# tc08-8-07.net
KiCad netlist of a schematic drawn in EAGLE
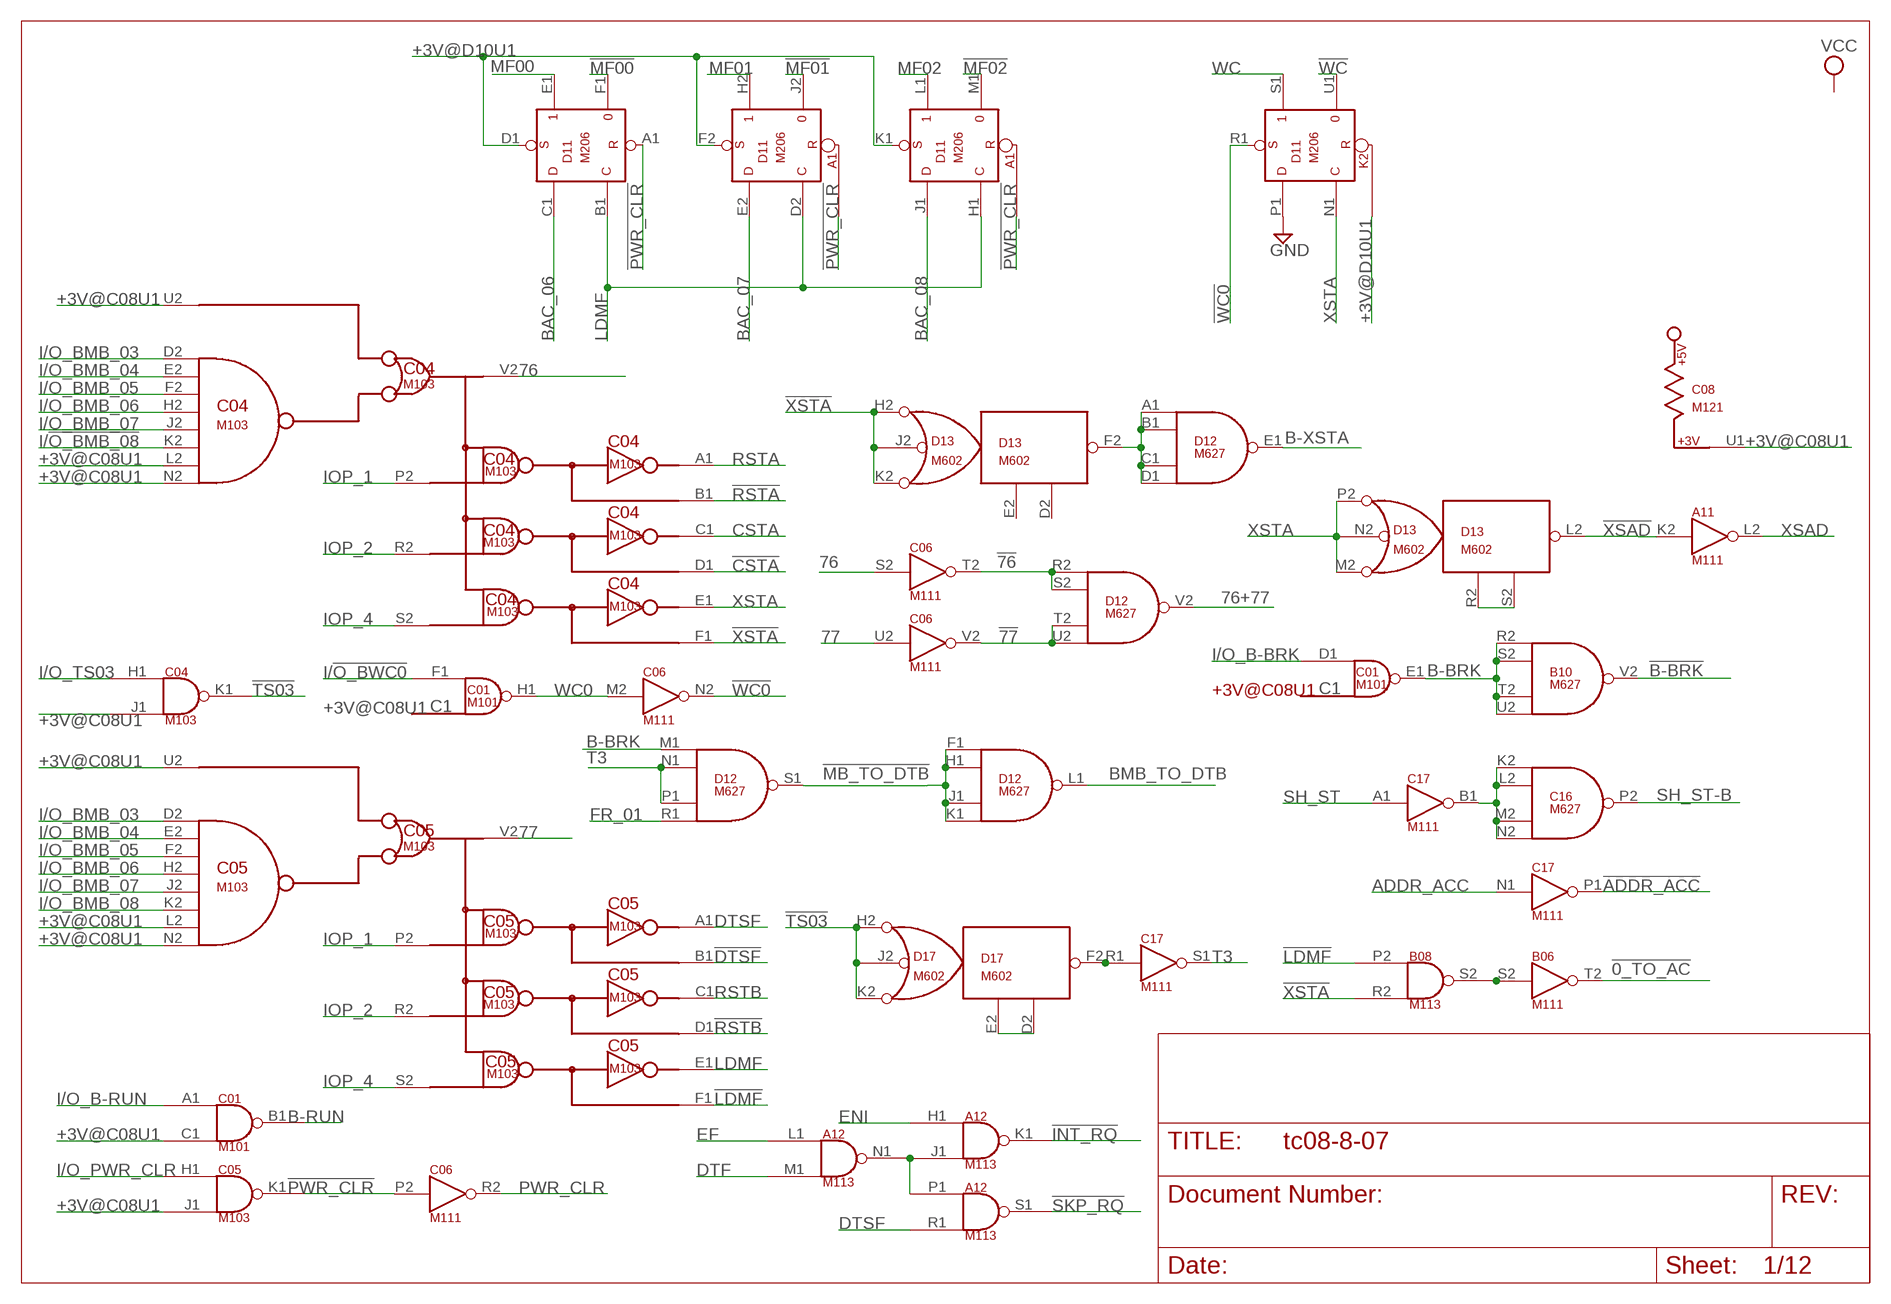
[diagram p0: schematic, sheet 1]
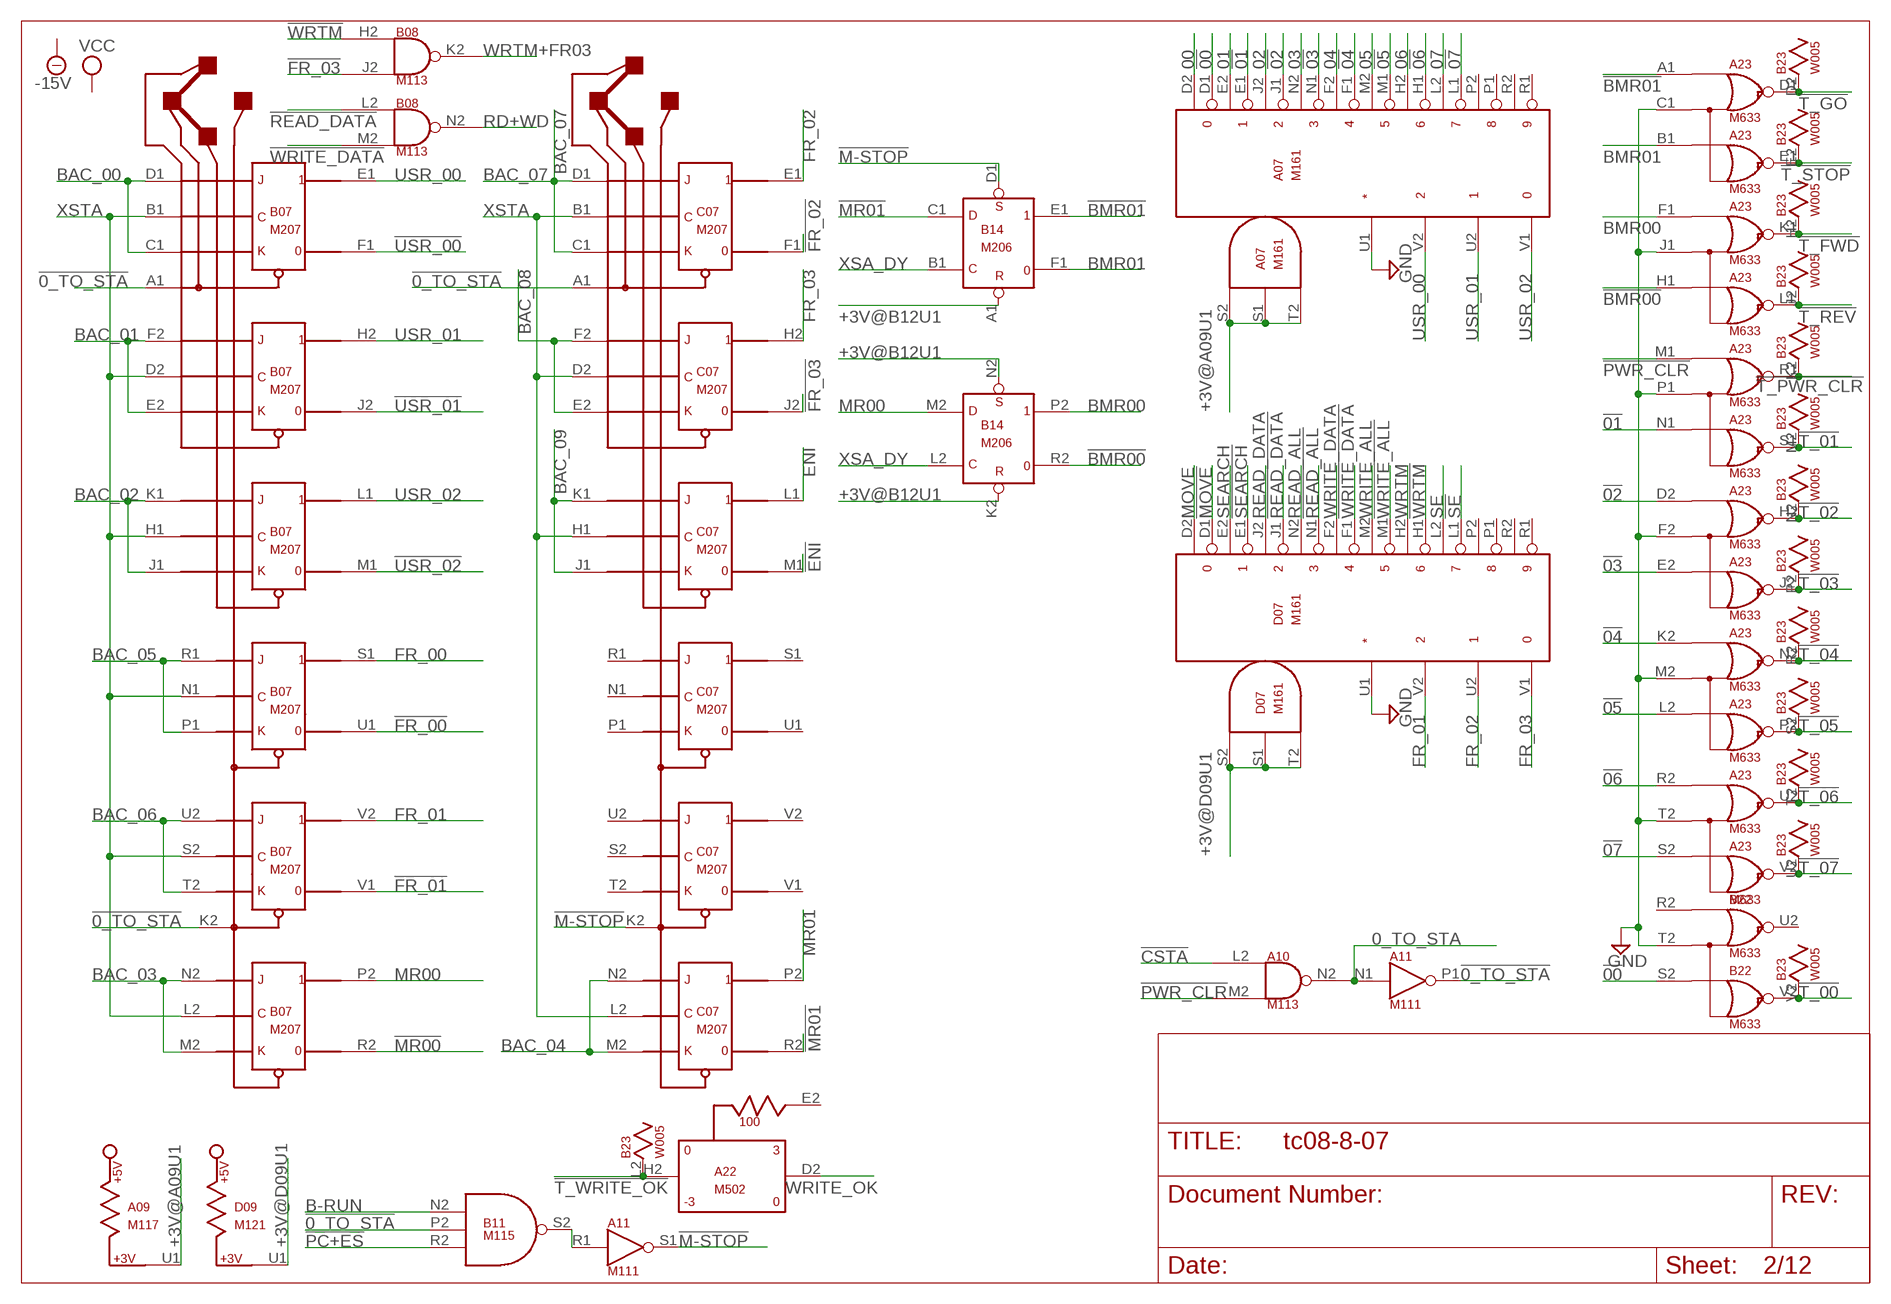
[diagram p1: schematic, sheet 2]
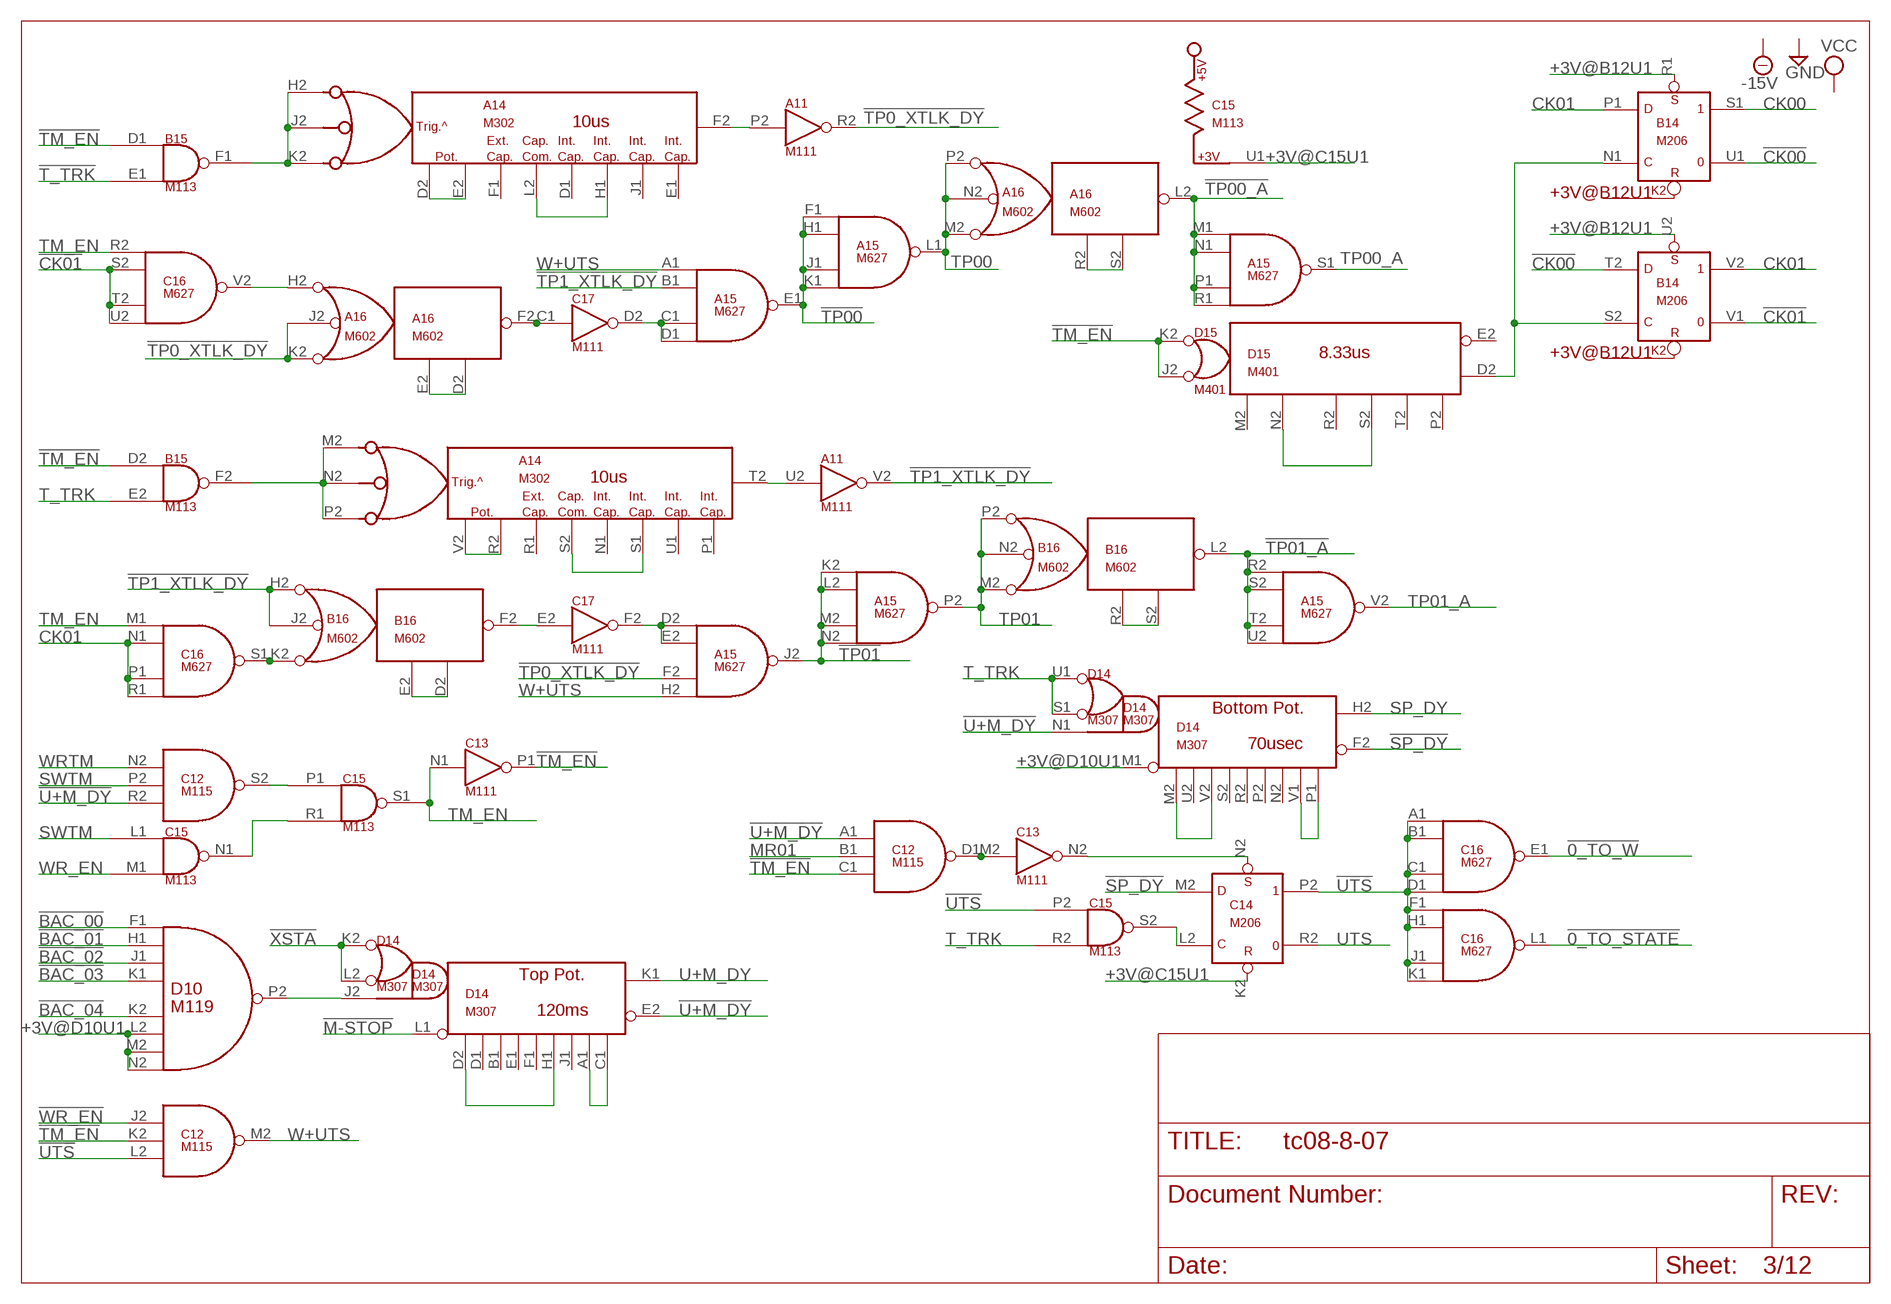
[diagram p2: schematic, sheet 3]
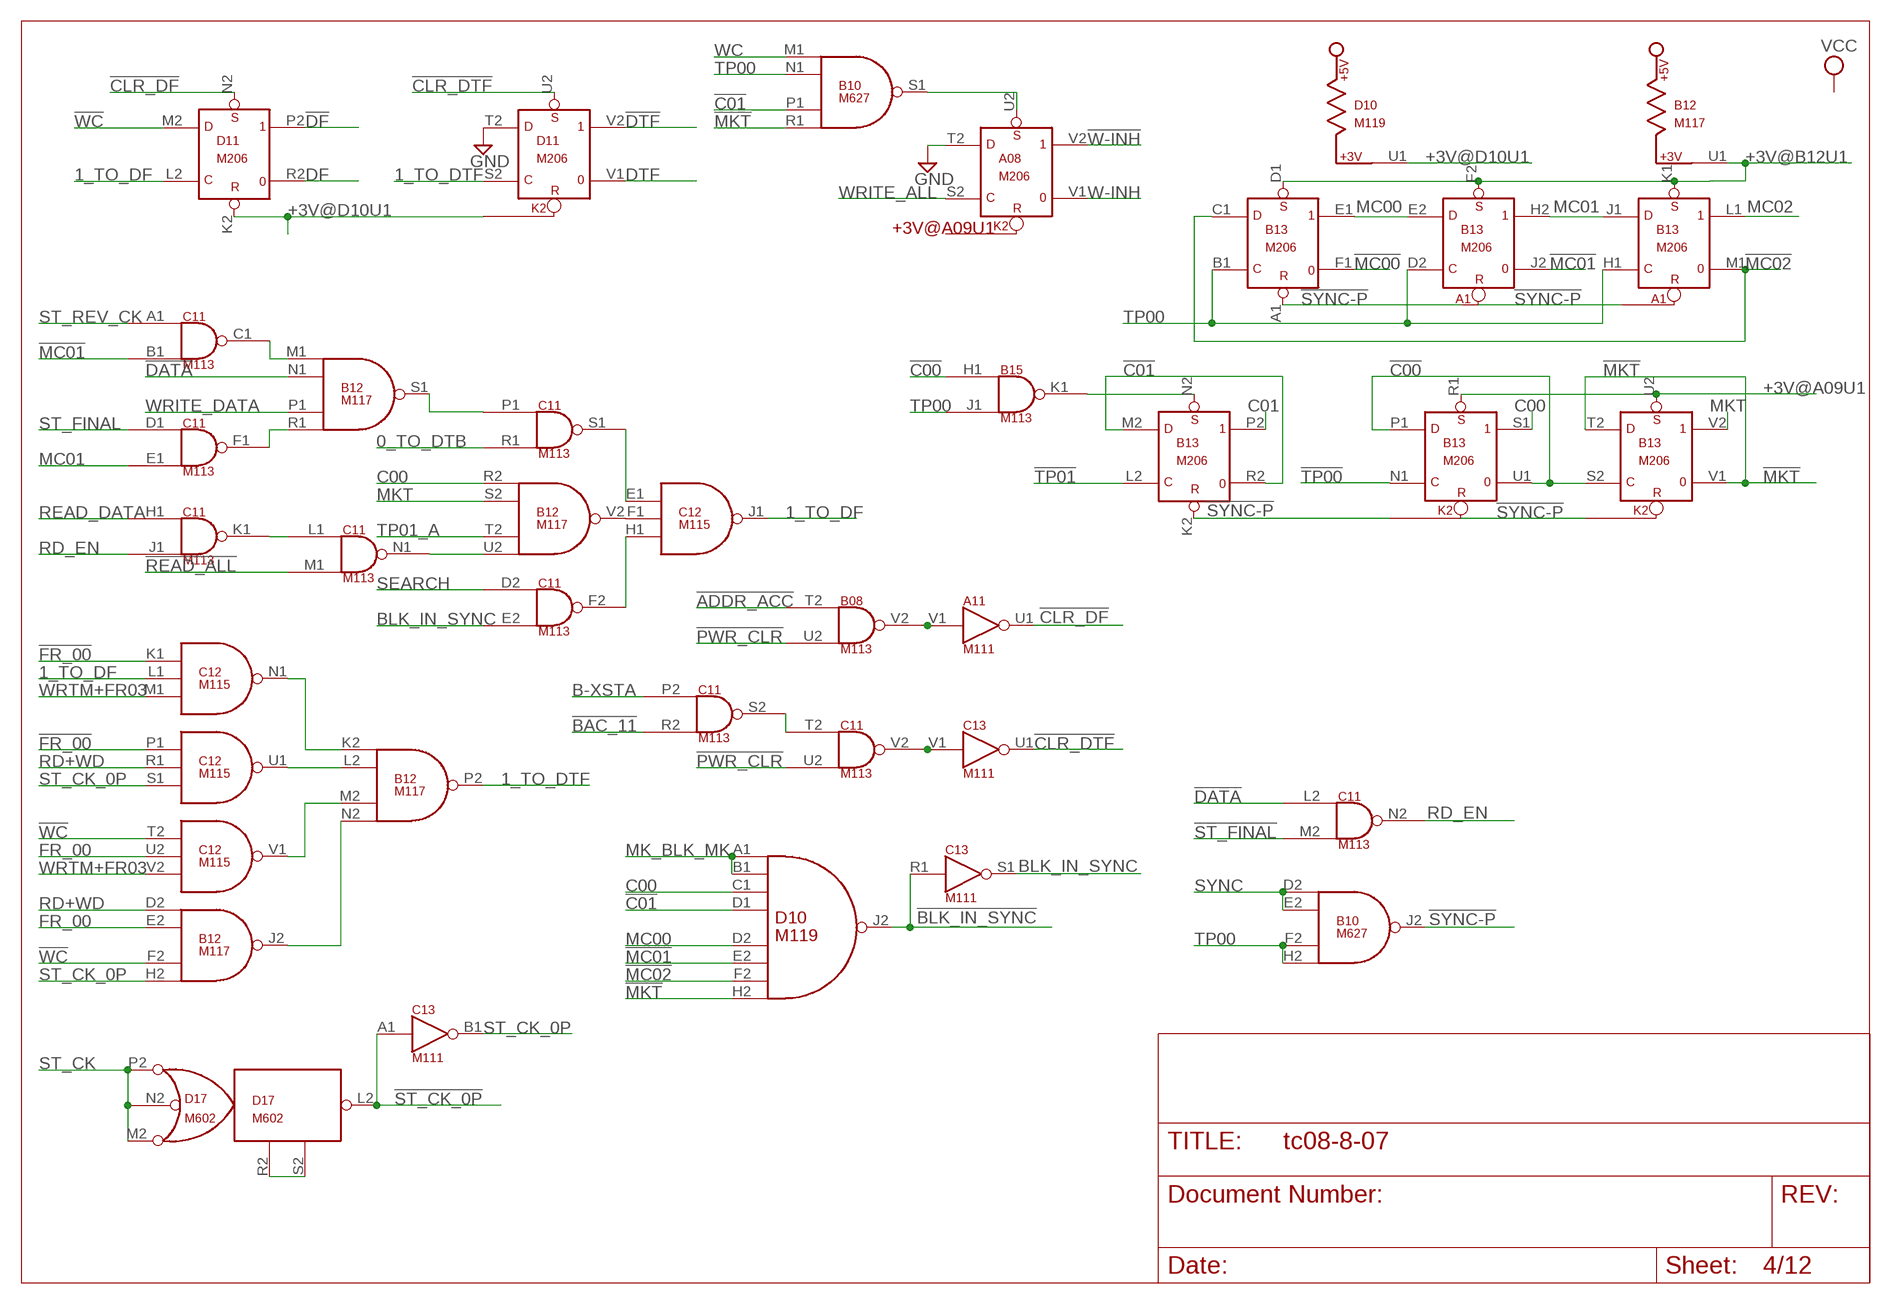
[diagram p3: schematic, sheet 4]
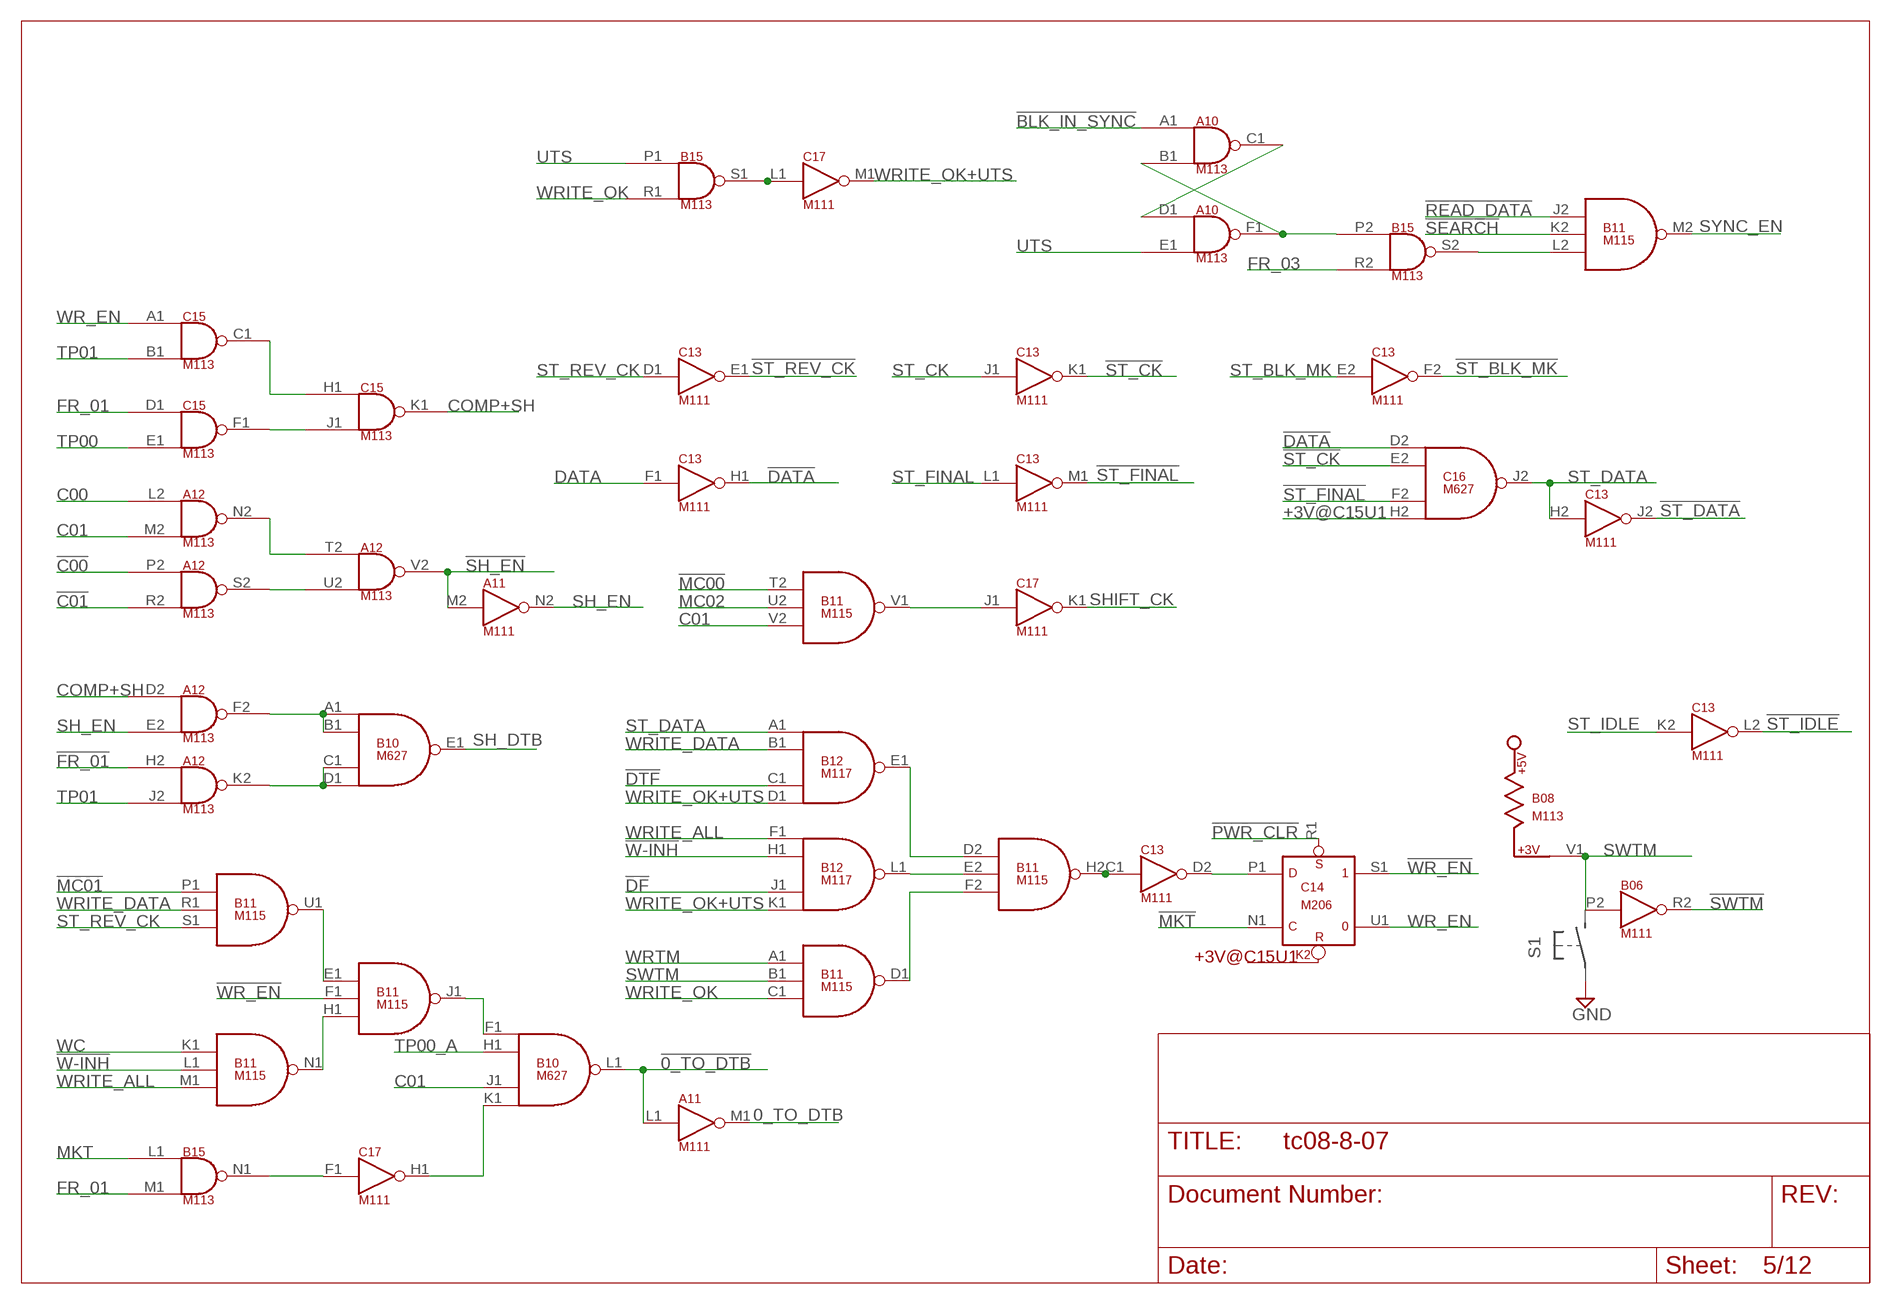
[diagram p4: schematic, sheet 5]
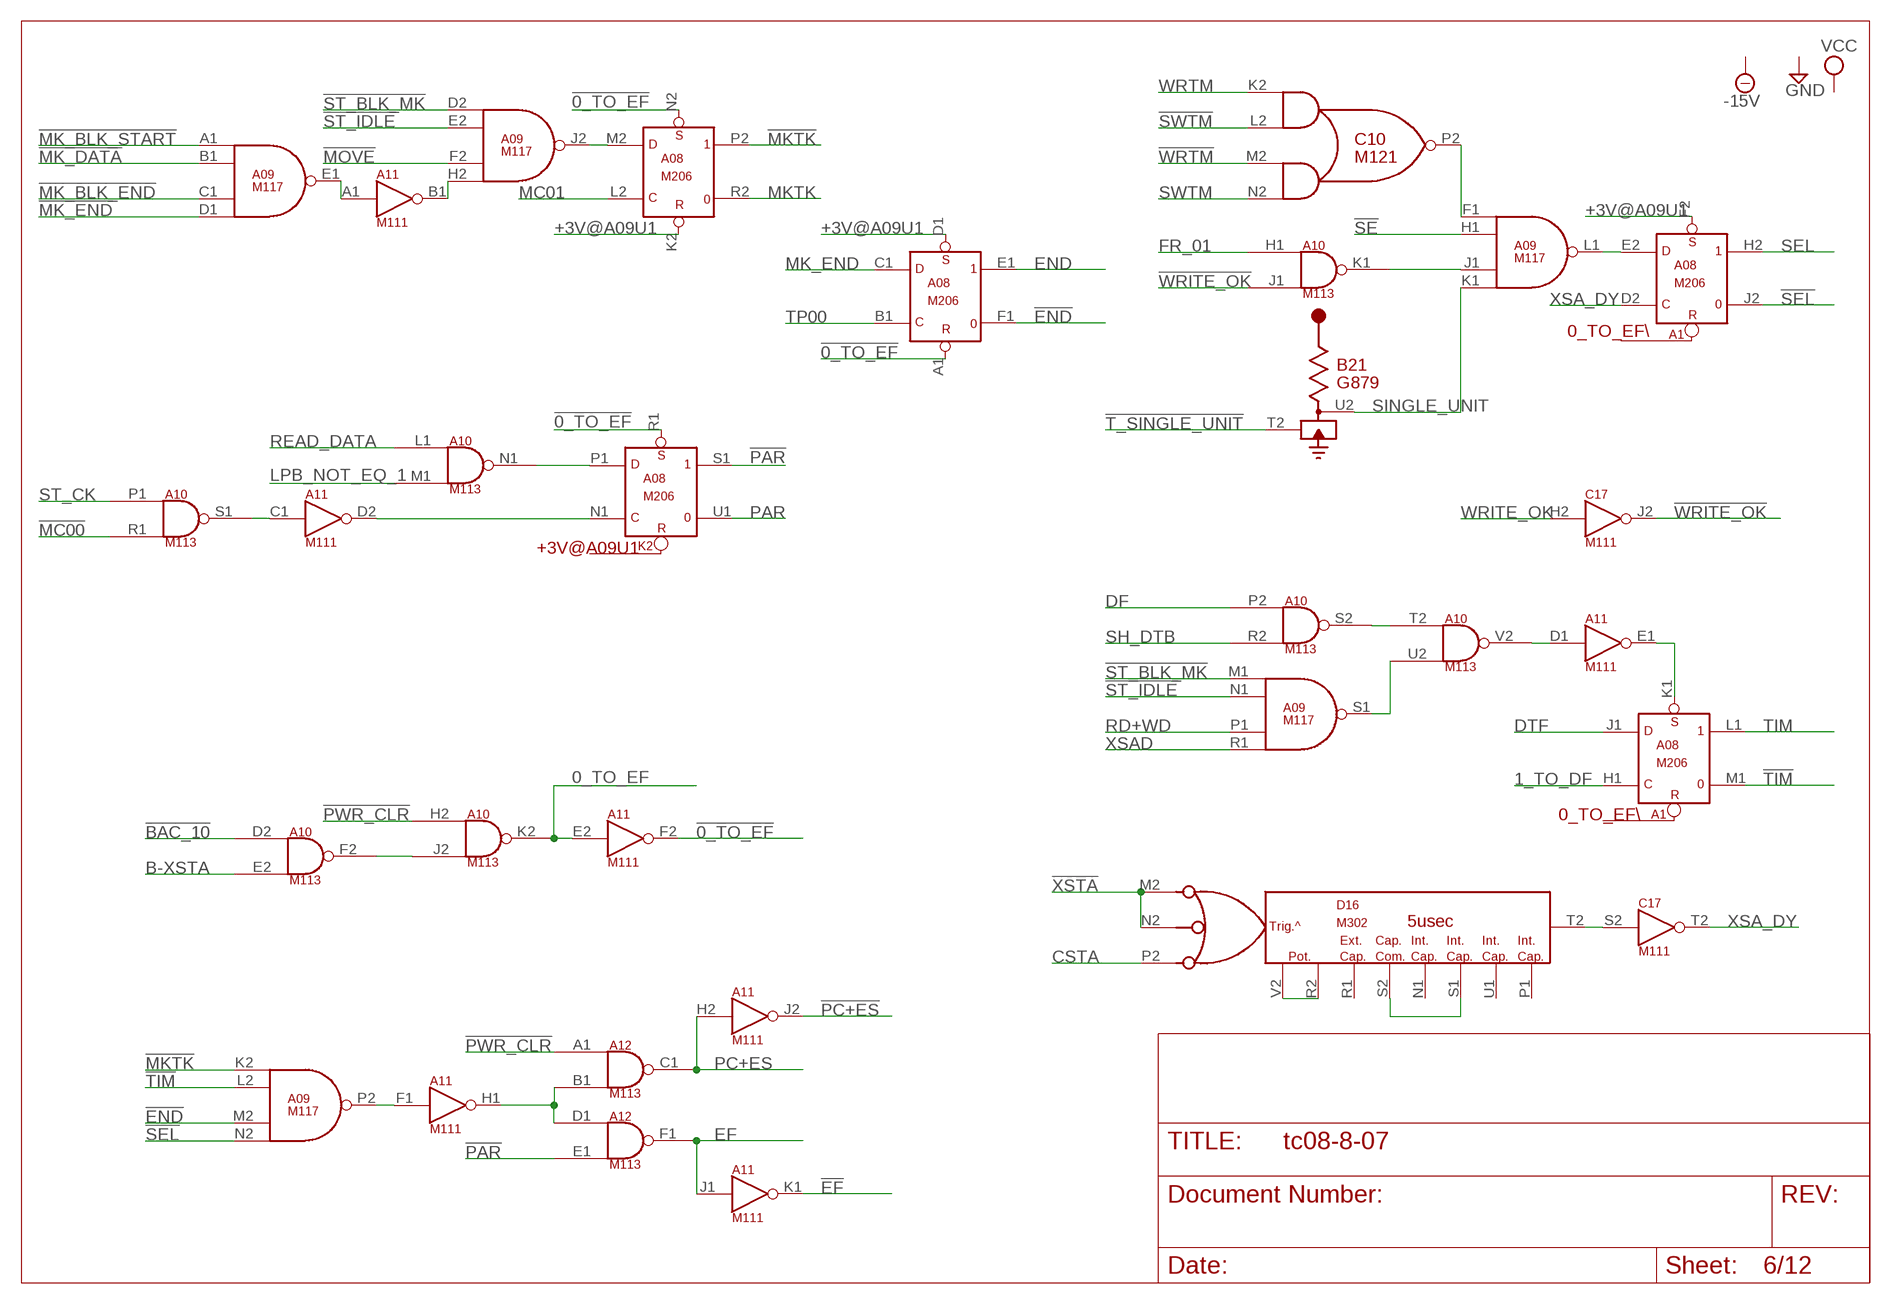
[diagram p5: schematic, sheet 6]
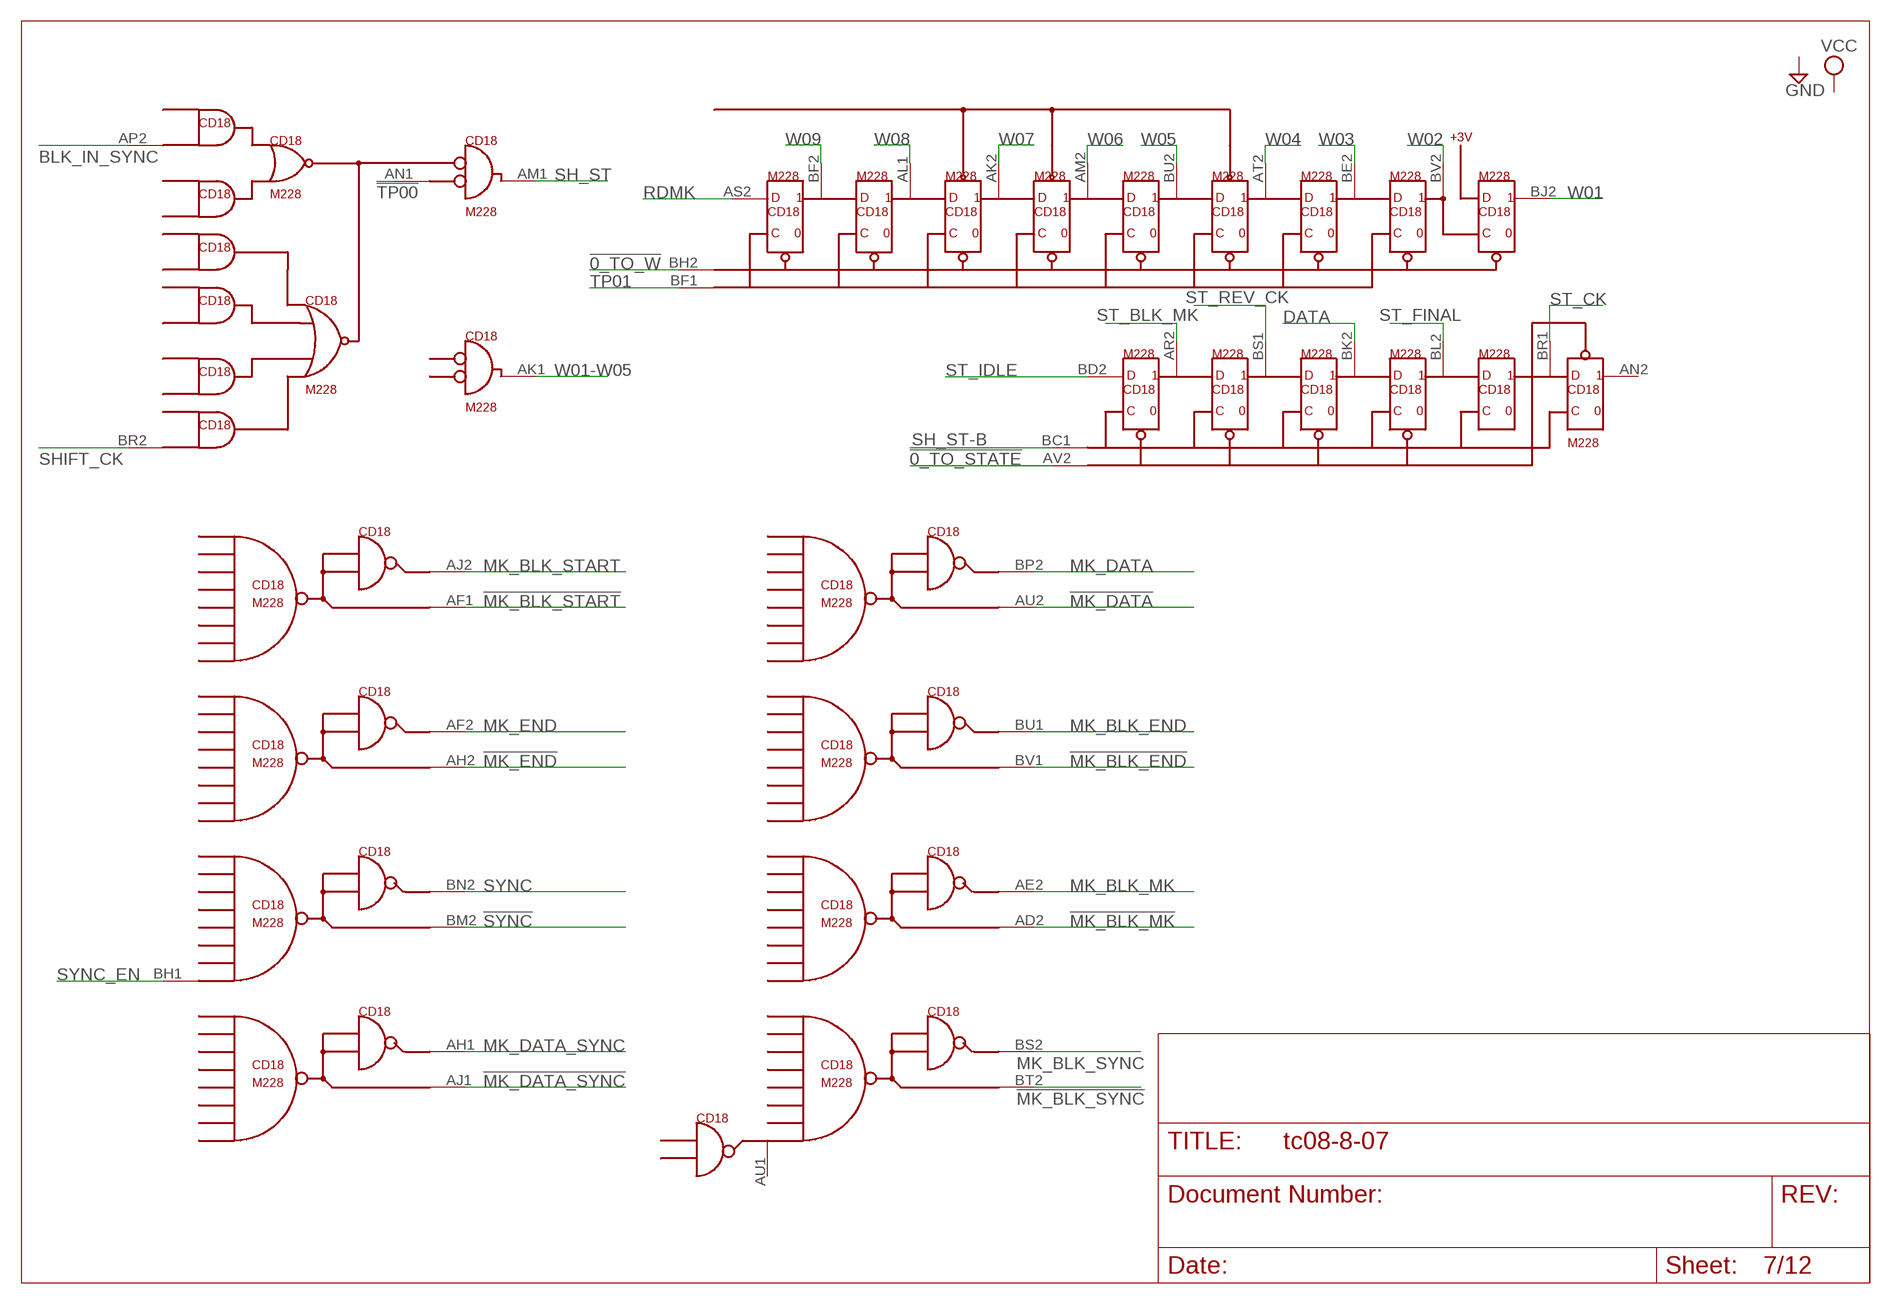
[diagram p6: schematic, sheet 7]
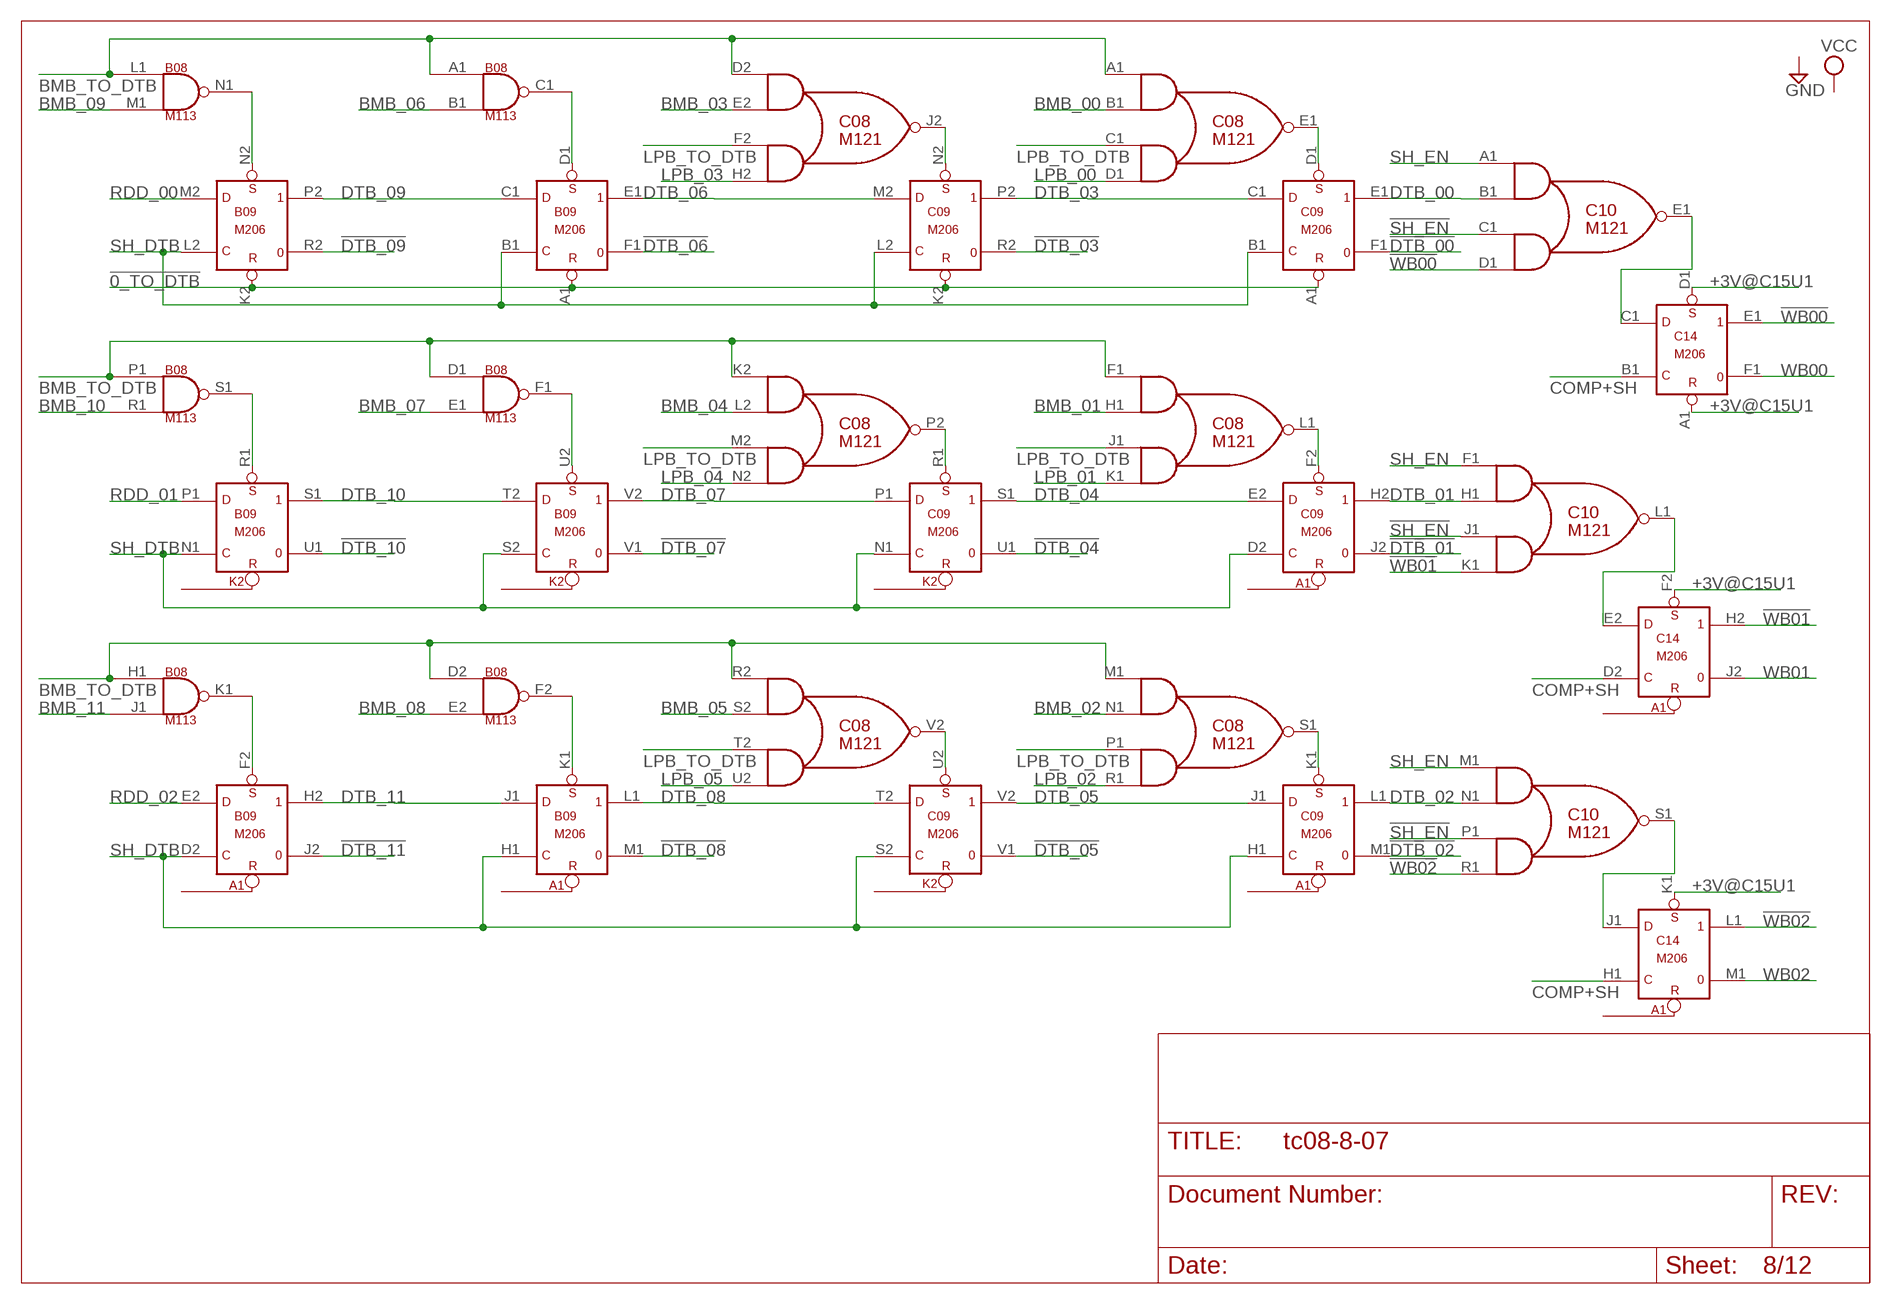
[diagram p7: schematic, sheet 8]
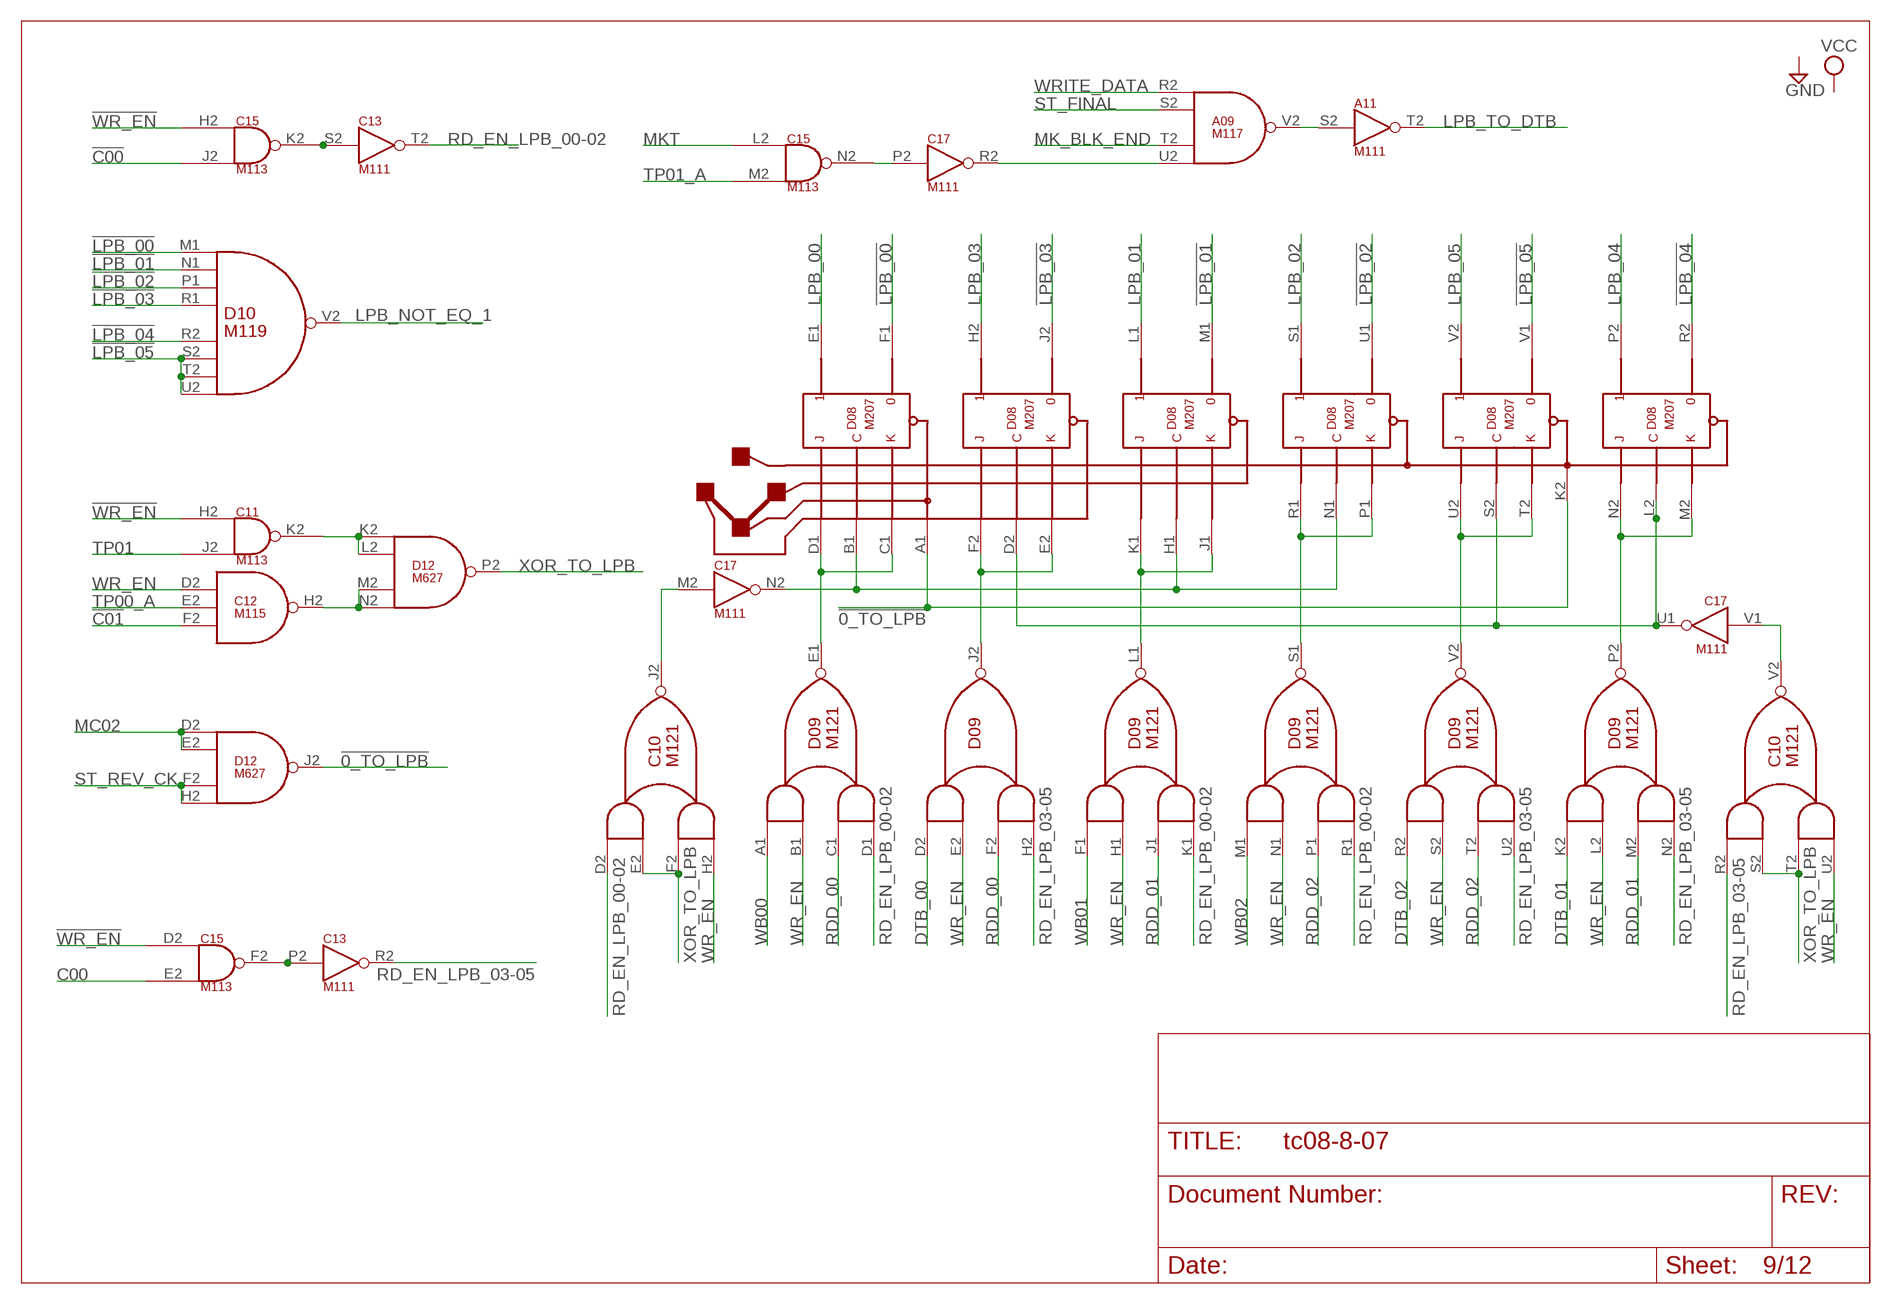
[diagram p8: schematic, sheet 9]
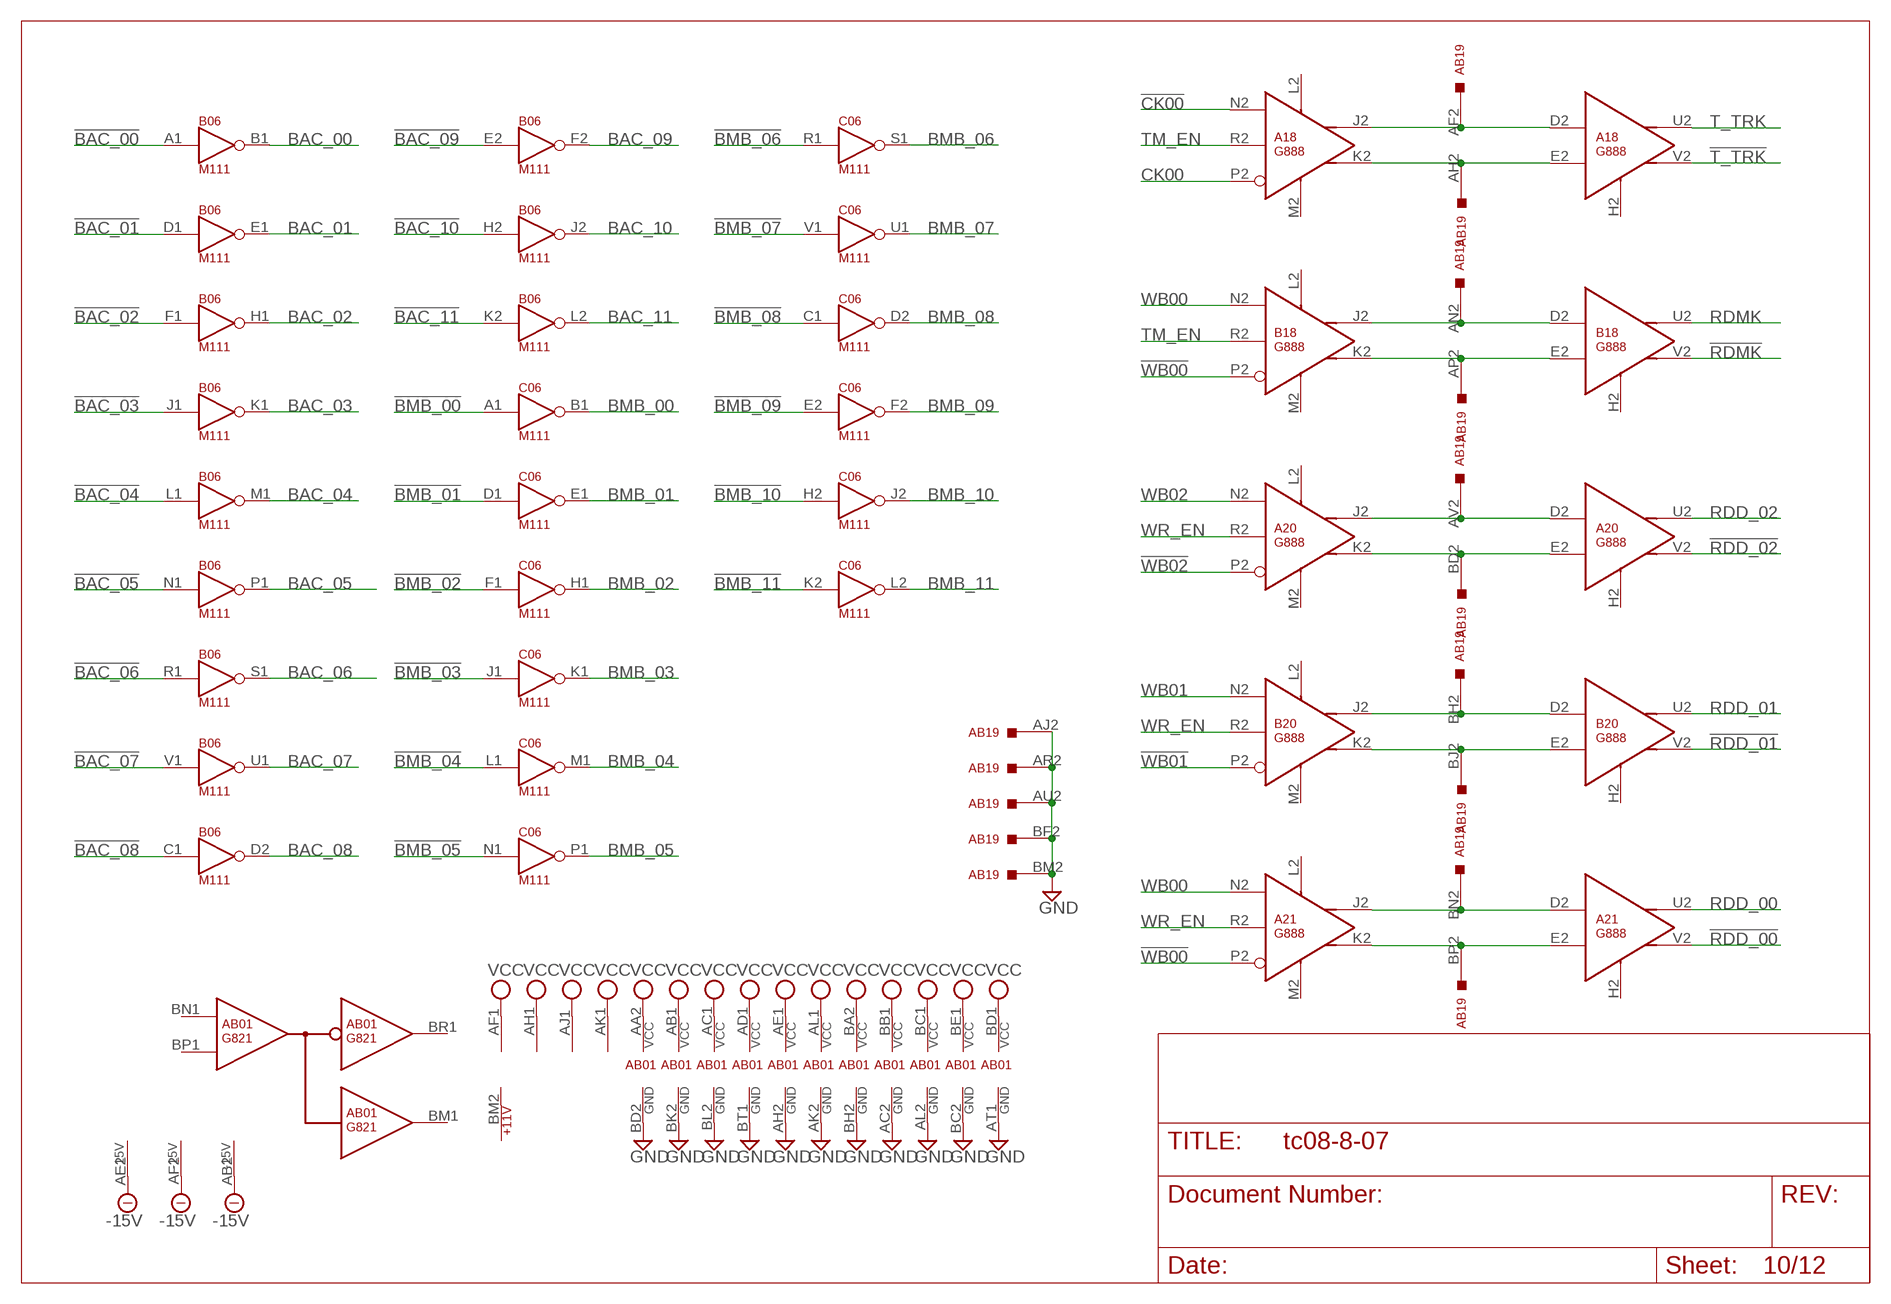
[diagram p9: schematic, sheet 10]
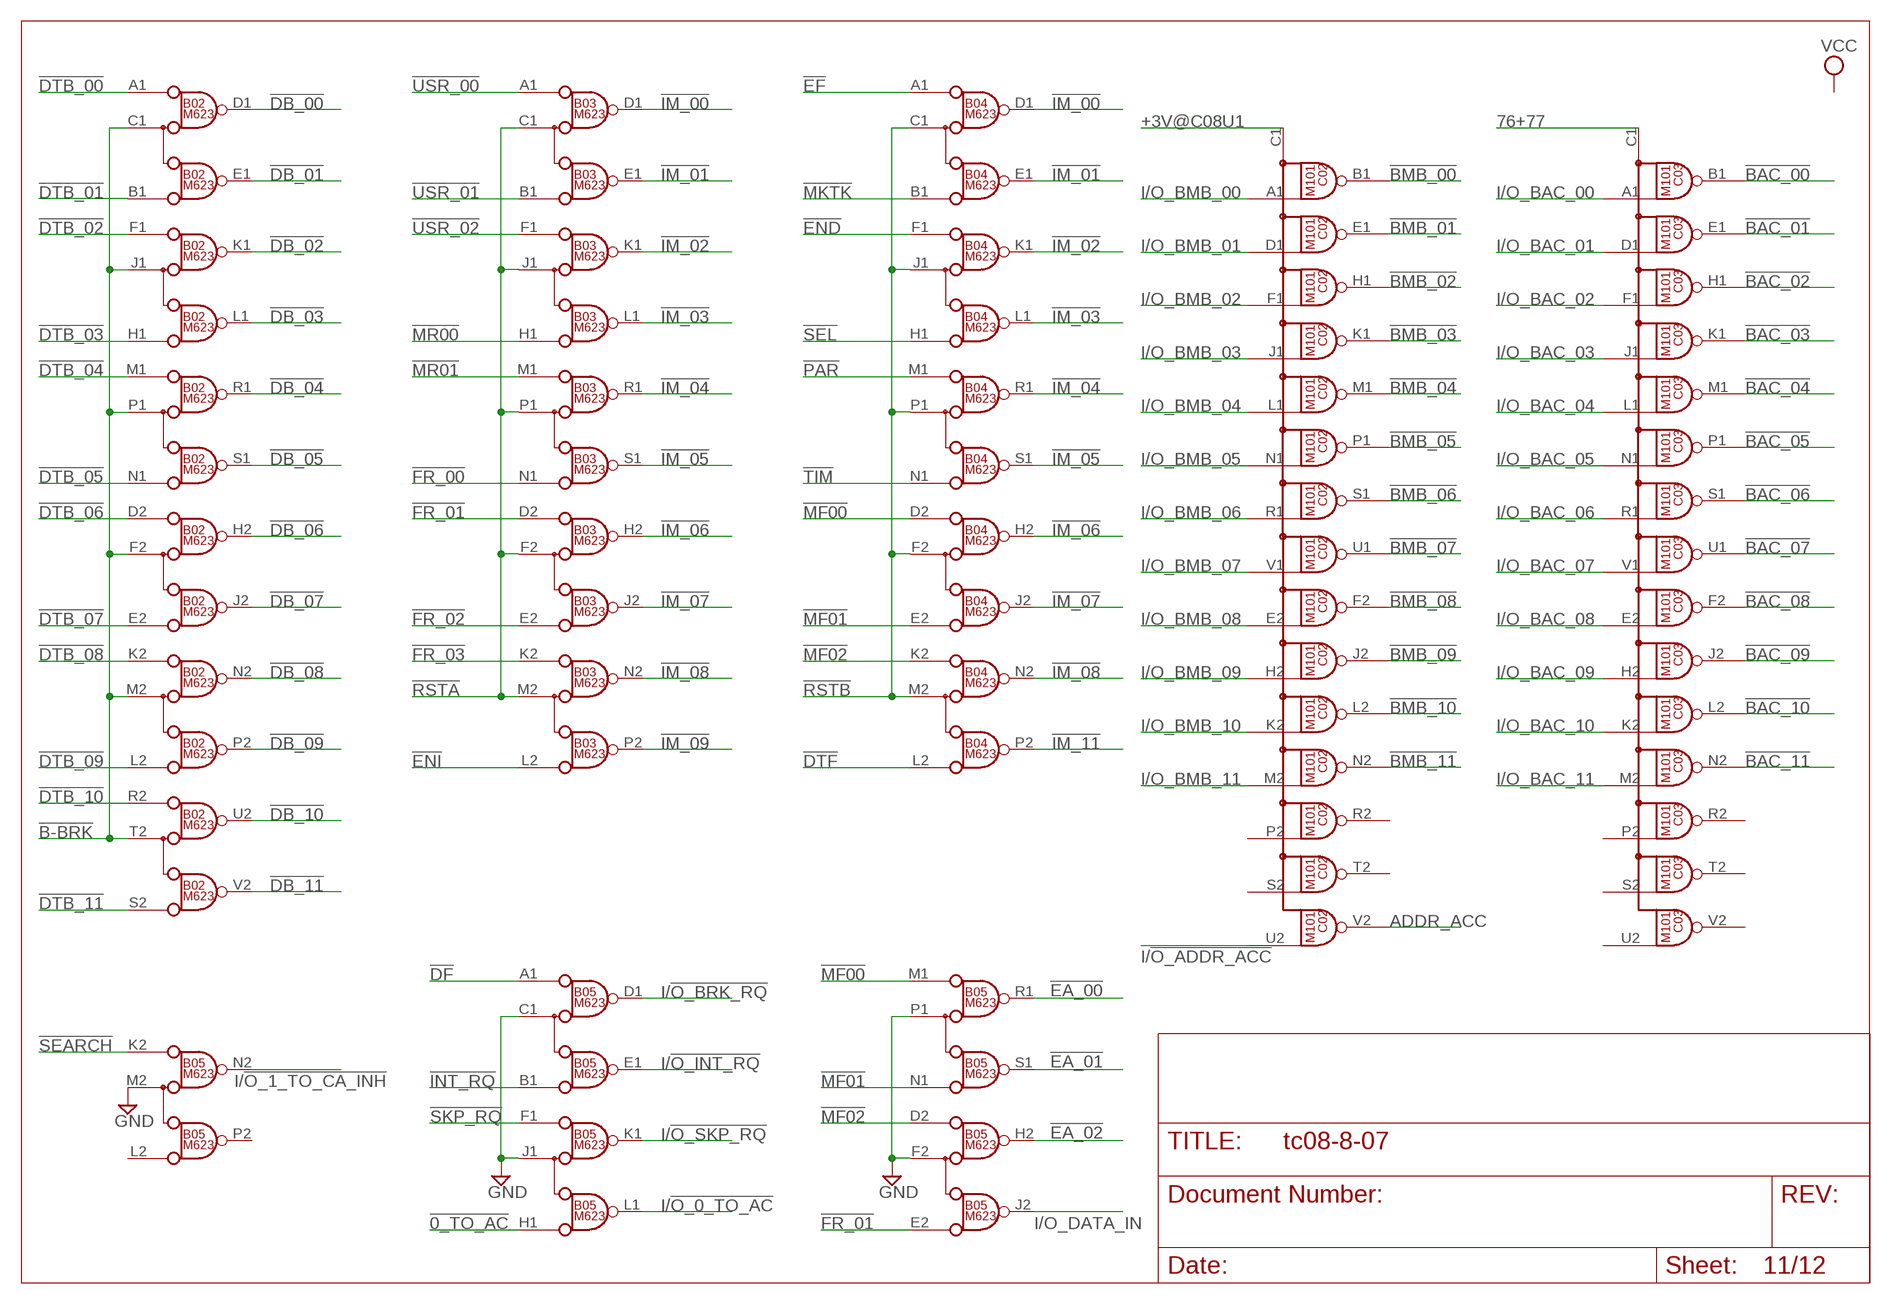
[diagram p10: schematic, sheet 11]
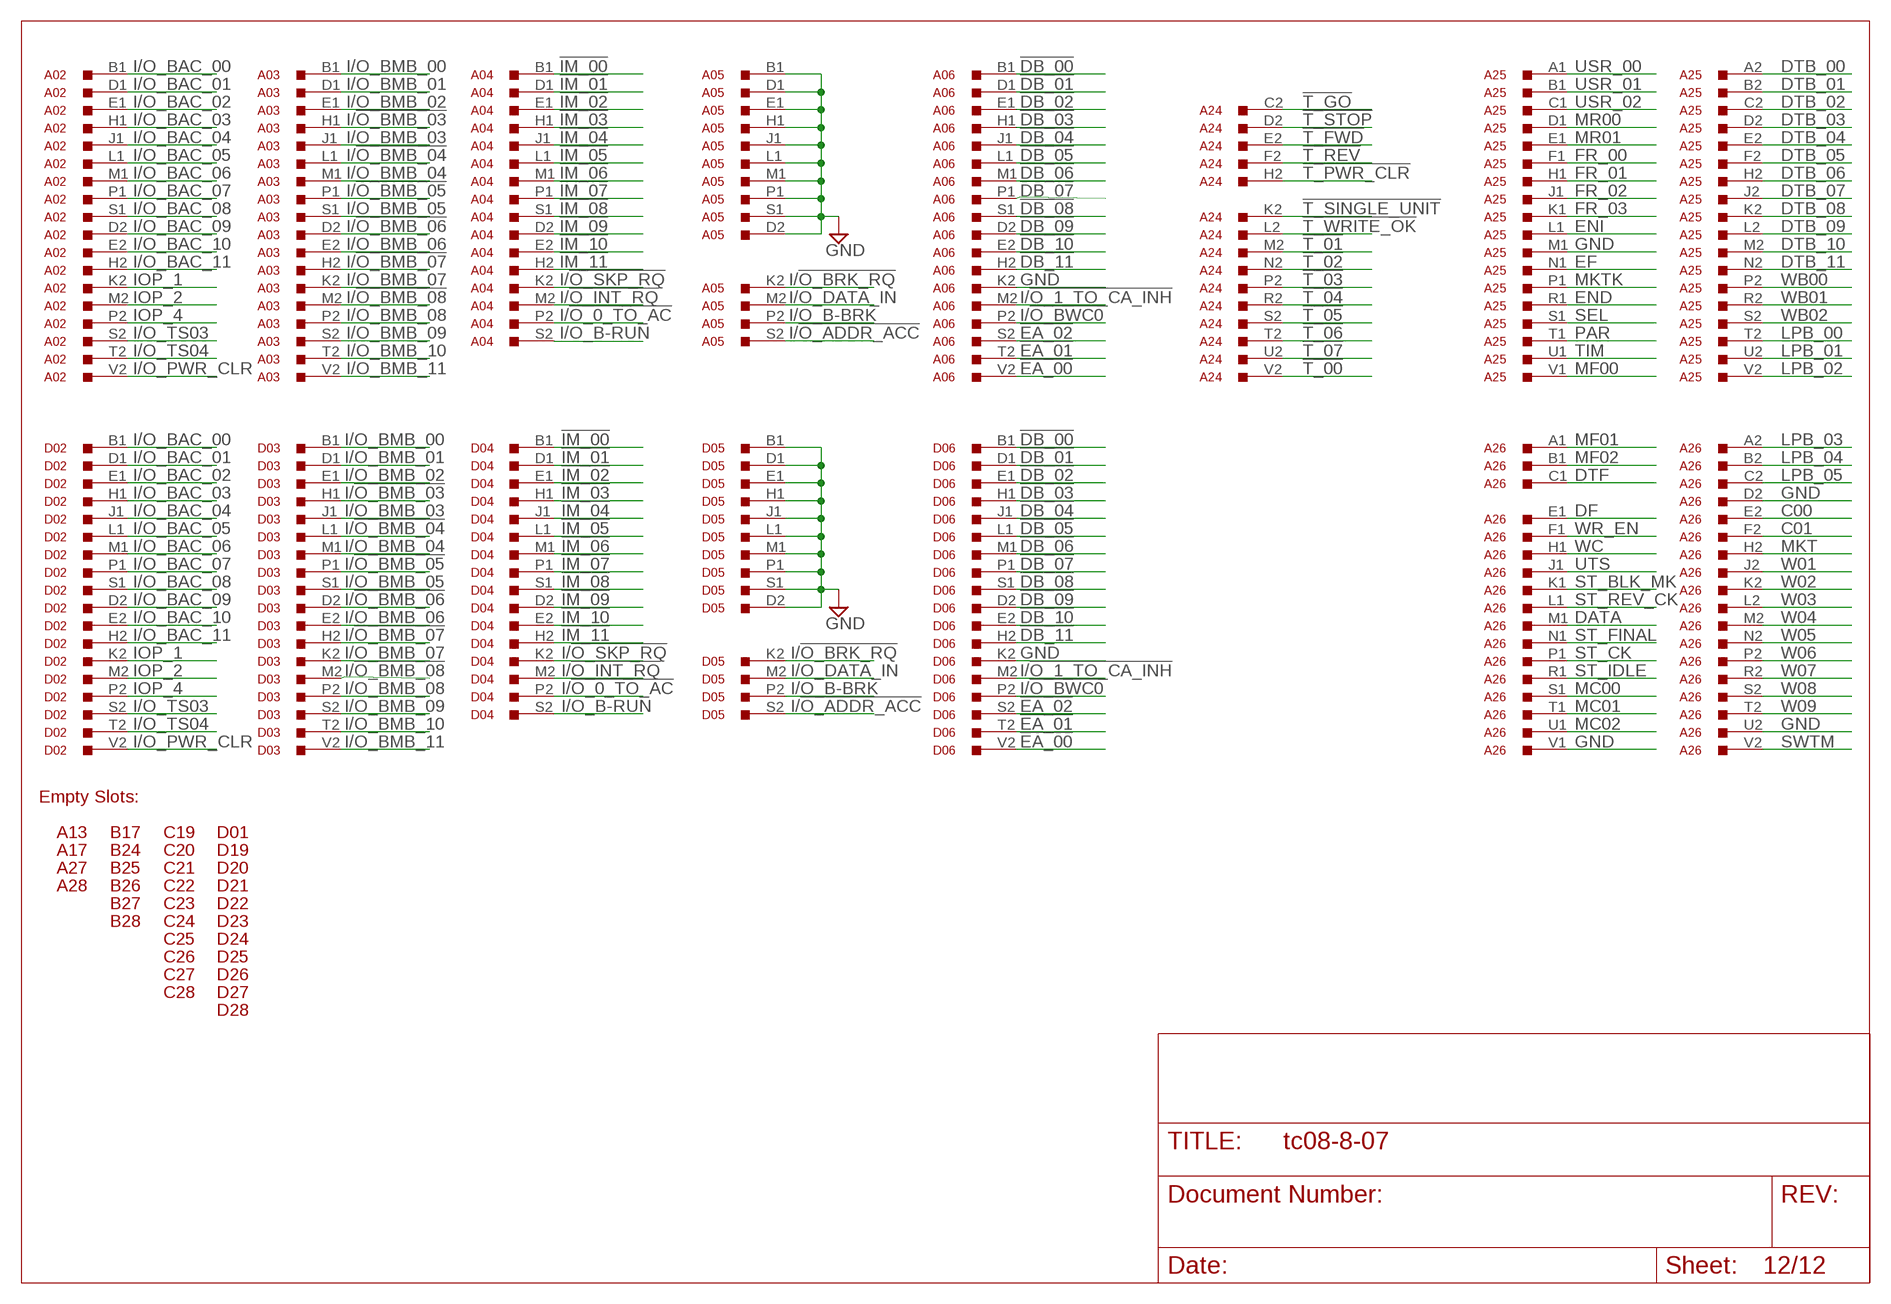
[diagram p11: schematic, sheet 12]

(export (version "E")
  (design (tool "Eeschema 10.0.6"))
  (components
    (comp (ref "A07")
      (value "M161")
      (footprint "eagle-import:H807")
      (libsource (lib "eagle-import") (part "M161"))
    )
    (comp (ref "A09")
      (value "M117")
      (footprint "eagle-import:H807")
      (libsource (lib "eagle-import") (part "M117"))
    )
    (comp (ref "A10")
      (value "M113")
      (footprint "eagle-import:H807")
      (libsource (lib "eagle-import") (part "M113"))
    )
    (comp (ref "A11")
      (value "M111")
      (footprint "eagle-import:H807")
      (libsource (lib "eagle-import") (part "M111"))
    )
    (comp (ref "A22")
      (value "M502")
      (footprint "eagle-import:H807")
      (libsource (lib "eagle-import") (part "M502"))
    )
    (comp (ref "A23")
      (value "M633")
      (footprint "eagle-import:H807")
      (libsource (lib "eagle-import") (part "M633"))
    )
    (comp (ref "B07")
      (value "M207")
      (footprint "eagle-import:H807")
      (libsource (lib "eagle-import") (part "M207"))
    )
    (comp (ref "B08")
      (value "M113")
      (footprint "eagle-import:H807")
      (libsource (lib "eagle-import") (part "M113"))
    )
    (comp (ref "B11")
      (value "M115")
      (footprint "eagle-import:H807")
      (libsource (lib "eagle-import") (part "M115"))
    )
    (comp (ref "B14")
      (value "M206")
      (footprint "eagle-import:H807")
      (libsource (lib "eagle-import") (part "M206X"))
    )
    (comp (ref "B22")
      (value "M633")
      (footprint "eagle-import:H807")
      (libsource (lib "eagle-import") (part "M633"))
    )
    (comp (ref "B23")
      (value "W005")
      (footprint "eagle-import:H807")
      (libsource (lib "eagle-import") (part "W005"))
    )
    (comp (ref "C07")
      (value "M207")
      (footprint "eagle-import:H807")
      (libsource (lib "eagle-import") (part "M207"))
    )
    (comp (ref "D07")
      (value "M161")
      (footprint "eagle-import:H807")
      (libsource (lib "eagle-import") (part "M161"))
    )
    (comp (ref "D09")
      (value "M121")
      (footprint "eagle-import:H807")
      (libsource (lib "eagle-import") (part "M121"))
    )
    (comp (ref "B09")
      (value "M206")
      (footprint "eagle-import:H807")
      (libsource (lib "eagle-import") (part "M206X"))
    )
    (comp (ref "C08")
      (value "M121")
      (footprint "eagle-import:H807")
      (libsource (lib "eagle-import") (part "M121"))
    )
    (comp (ref "C09")
      (value "M206")
      (footprint "eagle-import:H807")
      (libsource (lib "eagle-import") (part "M206X"))
    )
    (comp (ref "C10")
      (value "M121")
      (footprint "eagle-import:H807")
      (libsource (lib "eagle-import") (part "M121"))
    )
    (comp (ref "C14")
      (value "M206")
      (footprint "eagle-import:H807")
      (libsource (lib "eagle-import") (part "M206X"))
    )
    (comp (ref "A12")
      (value "M113")
      (footprint "eagle-import:H807")
      (libsource (lib "eagle-import") (part "M113"))
    )
    (comp (ref "B06")
      (value "M111")
      (footprint "eagle-import:H807")
      (libsource (lib "eagle-import") (part "M111"))
    )
    (comp (ref "B10")
      (value "M627")
      (footprint "eagle-import:H807")
      (libsource (lib "eagle-import") (part "M627"))
    )
    (comp (ref "C01")
      (value "M101")
      (footprint "eagle-import:H807")
      (libsource (lib "eagle-import") (part "M101"))
    )
    (comp (ref "C04")
      (value "M103")
      (footprint "eagle-import:H807")
      (libsource (lib "eagle-import") (part "M103"))
    )
    (comp (ref "C05")
      (value "M103")
      (footprint "eagle-import:H807")
      (libsource (lib "eagle-import") (part "M103"))
    )
    (comp (ref "C06")
      (value "M111")
      (footprint "eagle-import:H807")
      (libsource (lib "eagle-import") (part "M111"))
    )
    (comp (ref "C16")
      (value "M627")
      (footprint "eagle-import:H807")
      (libsource (lib "eagle-import") (part "M627"))
    )
    (comp (ref "C17")
      (value "M111")
      (footprint "eagle-import:H807")
      (libsource (lib "eagle-import") (part "M111"))
    )
    (comp (ref "D11")
      (value "M206")
      (footprint "eagle-import:H807")
      (libsource (lib "eagle-import") (part "M206X"))
    )
    (comp (ref "D12")
      (value "M627")
      (footprint "eagle-import:H807")
      (libsource (lib "eagle-import") (part "M627"))
    )
    (comp (ref "D13")
      (value "M602")
      (footprint "eagle-import:H807")
      (libsource (lib "eagle-import") (part "M602"))
    )
    (comp (ref "D17")
      (value "M602")
      (footprint "eagle-import:H807")
      (libsource (lib "eagle-import") (part "M602"))
    )
    (comp (ref "A18")
      (value "G888")
      (footprint "eagle-import:H807")
      (libsource (lib "eagle-import") (part "G888"))
    )
    (comp (ref "A20")
      (value "G888")
      (footprint "eagle-import:H807")
      (libsource (lib "eagle-import") (part "G888"))
    )
    (comp (ref "A21")
      (value "G888")
      (footprint "eagle-import:H807")
      (libsource (lib "eagle-import") (part "G888"))
    )
    (comp (ref "AB01")
      (value "G821")
      (footprint "eagle-import:H807-2")
      (libsource (lib "eagle-import") (part "G821"))
    )
    (comp (ref "AB19")
      (value "W032")
      (footprint "eagle-import:H807-2")
      (libsource (lib "eagle-import") (part "W032"))
    )
    (comp (ref "B18")
      (value "G888")
      (footprint "eagle-import:H807")
      (libsource (lib "eagle-import") (part "G888"))
    )
    (comp (ref "B20")
      (value "G888")
      (footprint "eagle-import:H807")
      (libsource (lib "eagle-import") (part "G888"))
    )
    (comp (ref "A14")
      (value "M302")
      (footprint "eagle-import:H807")
      (libsource (lib "eagle-import") (part "M302"))
    )
    (comp (ref "A15")
      (value "M627")
      (footprint "eagle-import:H807")
      (libsource (lib "eagle-import") (part "M627"))
    )
    (comp (ref "A16")
      (value "M602")
      (footprint "eagle-import:H807")
      (libsource (lib "eagle-import") (part "M602"))
    )
    (comp (ref "B15")
      (value "M113")
      (footprint "eagle-import:H807")
      (libsource (lib "eagle-import") (part "M113"))
    )
    (comp (ref "B16")
      (value "M602")
      (footprint "eagle-import:H807")
      (libsource (lib "eagle-import") (part "M602"))
    )
    (comp (ref "C12")
      (value "M115")
      (footprint "eagle-import:H807")
      (libsource (lib "eagle-import") (part "M115"))
    )
    (comp (ref "C13")
      (value "M111")
      (footprint "eagle-import:H807")
      (libsource (lib "eagle-import") (part "M111"))
    )
    (comp (ref "C15")
      (value "M113")
      (footprint "eagle-import:H807")
      (libsource (lib "eagle-import") (part "M113"))
    )
    (comp (ref "D10")
      (value "M119")
      (footprint "eagle-import:H807")
      (libsource (lib "eagle-import") (part "M119"))
    )
    (comp (ref "D14")
      (value "M307")
      (footprint "eagle-import:H807")
      (libsource (lib "eagle-import") (part "M307"))
    )
    (comp (ref "D15")
      (value "M401")
      (footprint "eagle-import:H807")
      (libsource (lib "eagle-import") (part "M401"))
    )
    (comp (ref "B12")
      (value "M117")
      (footprint "eagle-import:H807")
      (libsource (lib "eagle-import") (part "M117"))
    )
    (comp (ref "CD18")
      (value "M228")
      (footprint "eagle-import:H807-2")
      (libsource (lib "eagle-import") (part "M228"))
    )
    (comp (ref "A08")
      (value "M206")
      (footprint "eagle-import:H807")
      (libsource (lib "eagle-import") (part "M206X"))
    )
    (comp (ref "B13")
      (value "M206")
      (footprint "eagle-import:H807")
      (libsource (lib "eagle-import") (part "M206X"))
    )
    (comp (ref "C11")
      (value "M113")
      (footprint "eagle-import:H807")
      (libsource (lib "eagle-import") (part "M113"))
    )
    (comp (ref "B02")
      (value "M623")
      (footprint "eagle-import:H807")
      (libsource (lib "eagle-import") (part "M623"))
    )
    (comp (ref "B03")
      (value "M623")
      (footprint "eagle-import:H807")
      (libsource (lib "eagle-import") (part "M623"))
    )
    (comp (ref "B04")
      (value "M623")
      (footprint "eagle-import:H807")
      (libsource (lib "eagle-import") (part "M623"))
    )
    (comp (ref "B05")
      (value "M623")
      (footprint "eagle-import:H807")
      (libsource (lib "eagle-import") (part "M623"))
    )
    (comp (ref "C02")
      (value "M101")
      (footprint "eagle-import:H807")
      (libsource (lib "eagle-import") (part "M101-ARRAY"))
    )
    (comp (ref "C03")
      (value "M101")
      (footprint "eagle-import:H807")
      (libsource (lib "eagle-import") (part "M101-ARRAY"))
    )
    (comp (ref "A02")
      (value "M903")
      (footprint "eagle-import:H807")
      (libsource (lib "eagle-import") (part "M903"))
    )
    (comp (ref "A03")
      (value "M903")
      (footprint "eagle-import:H807")
      (libsource (lib "eagle-import") (part "M903"))
    )
    (comp (ref "A04")
      (value "M903")
      (footprint "eagle-import:H807")
      (libsource (lib "eagle-import") (part "M903"))
    )
    (comp (ref "A05")
      (value "M903")
      (footprint "eagle-import:H807")
      (libsource (lib "eagle-import") (part "M903"))
    )
    (comp (ref "A06")
      (value "M903")
      (footprint "eagle-import:H807")
      (libsource (lib "eagle-import") (part "M903"))
    )
    (comp (ref "A13")
      (value "H807")
      (footprint "eagle-import:H807")
      (libsource (lib "eagle-import") (part "H807"))
    )
    (comp (ref "A17")
      (value "H807")
      (footprint "eagle-import:H807")
      (libsource (lib "eagle-import") (part "H807"))
    )
    (comp (ref "A24")
      (value "W023")
      (footprint "eagle-import:H807")
      (libsource (lib "eagle-import") (part "W023"))
    )
    (comp (ref "A25")
      (value "M916")
      (footprint "eagle-import:H807")
      (libsource (lib "eagle-import") (part "M916"))
    )
    (comp (ref "A26")
      (value "M916")
      (footprint "eagle-import:H807")
      (libsource (lib "eagle-import") (part "M916"))
    )
    (comp (ref "A27")
      (value "H807")
      (footprint "eagle-import:H807")
      (libsource (lib "eagle-import") (part "H807"))
    )
    (comp (ref "A28")
      (value "H807")
      (footprint "eagle-import:H807")
      (libsource (lib "eagle-import") (part "H807"))
    )
    (comp (ref "B17")
      (value "H807")
      (footprint "eagle-import:H807")
      (libsource (lib "eagle-import") (part "H807"))
    )
    (comp (ref "B24")
      (value "H807")
      (footprint "eagle-import:H807")
      (libsource (lib "eagle-import") (part "H807"))
    )
    (comp (ref "B25")
      (value "H807")
      (footprint "eagle-import:H807")
      (libsource (lib "eagle-import") (part "H807"))
    )
    (comp (ref "B26")
      (value "H807")
      (footprint "eagle-import:H807")
      (libsource (lib "eagle-import") (part "H807"))
    )
    (comp (ref "B27")
      (value "H807")
      (footprint "eagle-import:H807")
      (libsource (lib "eagle-import") (part "H807"))
    )
    (comp (ref "B28")
      (value "H807")
      (footprint "eagle-import:H807")
      (libsource (lib "eagle-import") (part "H807"))
    )
    (comp (ref "C19")
      (value "H807")
      (footprint "eagle-import:H807")
      (libsource (lib "eagle-import") (part "H807"))
    )
    (comp (ref "C20")
      (value "H807")
      (footprint "eagle-import:H807")
      (libsource (lib "eagle-import") (part "H807"))
    )
    (comp (ref "C21")
      (value "H807")
      (footprint "eagle-import:H807")
      (libsource (lib "eagle-import") (part "H807"))
    )
    (comp (ref "C22")
      (value "H807")
      (footprint "eagle-import:H807")
      (libsource (lib "eagle-import") (part "H807"))
    )
    (comp (ref "C23")
      (value "H807")
      (footprint "eagle-import:H807")
      (libsource (lib "eagle-import") (part "H807"))
    )
    (comp (ref "C24")
      (value "H807")
      (footprint "eagle-import:H807")
      (libsource (lib "eagle-import") (part "H807"))
    )
    (comp (ref "C25")
      (value "H807")
      (footprint "eagle-import:H807")
      (libsource (lib "eagle-import") (part "H807"))
    )
    (comp (ref "C26")
      (value "H807")
      (footprint "eagle-import:H807")
      (libsource (lib "eagle-import") (part "H807"))
    )
    (comp (ref "C27")
      (value "H807")
      (footprint "eagle-import:H807")
      (libsource (lib "eagle-import") (part "H807"))
    )
    (comp (ref "C28")
      (value "H807")
      (footprint "eagle-import:H807")
      (libsource (lib "eagle-import") (part "H807"))
    )
    (comp (ref "D01")
      (value "H807")
      (footprint "eagle-import:H807")
      (libsource (lib "eagle-import") (part "H807"))
    )
    (comp (ref "D02")
      (value "M903")
      (footprint "eagle-import:H807")
      (libsource (lib "eagle-import") (part "M903"))
    )
    (comp (ref "D03")
      (value "M903")
      (footprint "eagle-import:H807")
      (libsource (lib "eagle-import") (part "M903"))
    )
    (comp (ref "D04")
      (value "M903")
      (footprint "eagle-import:H807")
      (libsource (lib "eagle-import") (part "M903"))
    )
    (comp (ref "D05")
      (value "M903")
      (footprint "eagle-import:H807")
      (libsource (lib "eagle-import") (part "M903"))
    )
    (comp (ref "D06")
      (value "M903")
      (footprint "eagle-import:H807")
      (libsource (lib "eagle-import") (part "M903"))
    )
    (comp (ref "D19")
      (value "H807")
      (footprint "eagle-import:H807")
      (libsource (lib "eagle-import") (part "H807"))
    )
    (comp (ref "D20")
      (value "H807")
      (footprint "eagle-import:H807")
      (libsource (lib "eagle-import") (part "H807"))
    )
    (comp (ref "D21")
      (value "H807")
      (footprint "eagle-import:H807")
      (libsource (lib "eagle-import") (part "H807"))
    )
    (comp (ref "D22")
      (value "H807")
      (footprint "eagle-import:H807")
      (libsource (lib "eagle-import") (part "H807"))
    )
    (comp (ref "D23")
      (value "H807")
      (footprint "eagle-import:H807")
      (libsource (lib "eagle-import") (part "H807"))
    )
    (comp (ref "D24")
      (value "H807")
      (footprint "eagle-import:H807")
      (libsource (lib "eagle-import") (part "H807"))
    )
    (comp (ref "D25")
      (value "H807")
      (footprint "eagle-import:H807")
      (libsource (lib "eagle-import") (part "H807"))
    )
    (comp (ref "D26")
      (value "H807")
      (footprint "eagle-import:H807")
      (libsource (lib "eagle-import") (part "H807"))
    )
    (comp (ref "D27")
      (value "H807")
      (footprint "eagle-import:H807")
      (libsource (lib "eagle-import") (part "H807"))
    )
    (comp (ref "D28")
      (value "H807")
      (footprint "eagle-import:H807")
      (libsource (lib "eagle-import") (part "H807"))
    )
    (comp (ref "B21")
      (value "G879")
      (footprint "eagle-import:H807")
      (libsource (lib "eagle-import") (part "G879"))
    )
    (comp (ref "D16")
      (value "M302")
      (footprint "eagle-import:H807")
      (libsource (lib "eagle-import") (part "M302"))
    )
    (comp (ref "D08")
      (value "M207")
      (footprint "eagle-import:H807")
      (libsource (lib "eagle-import") (part "M207"))
    )
  )
  (nets
    (net (code "1") (name "+3V@A09U1") (class "Default")
      (node (ref "A07") (pin "S1") (pinfunction "EN2_S1") (pintype "input"))
      (node (ref "A07") (pin "S2") (pinfunction "EN1_S2") (pintype "input"))
      (node (ref "A07") (pin "T2") (pinfunction "EN3_T2") (pintype "input"))
      (node (ref "A08") (pin "D1") (pinfunction "S_D1") (pintype "input"))
      (node (ref "A08") (pin "F2") (pinfunction "S_F2") (pintype "input"))
      (node (ref "A08") (pin "K2") (pinfunction "R_K2") (pintype "input"))
      (node (ref "A09") (pin "U1") (pinfunction "P$1_U1") (pintype "passive"))
      (node (ref "B13") (pin "R1") (pinfunction "S_R1") (pintype "input"))
      (node (ref "B13") (pin "U2") (pinfunction "S_U2") (pintype "input"))
    )
    (net (code "2") (name "+3V@B12U1") (class "Default")
      (node (ref "B12") (pin "U1") (pinfunction "P$1_U1") (pintype "passive"))
      (node (ref "B13") (pin "D1") (pinfunction "S_D1") (pintype "input"))
      (node (ref "B13") (pin "F2") (pinfunction "S_F2") (pintype "input"))
      (node (ref "B13") (pin "K1") (pinfunction "S_K1") (pintype "input"))
      (node (ref "B14") (pin "A1") (pinfunction "R_A1") (pintype "input"))
      (node (ref "B14") (pin "K2") (pinfunction "R_K2") (pintype "input"))
      (node (ref "B14") (pin "N2") (pinfunction "S_N2") (pintype "input"))
      (node (ref "B14") (pin "R1") (pinfunction "S_R1") (pintype "input"))
      (node (ref "B14") (pin "U2") (pinfunction "S_U2") (pintype "input"))
    )
    (net (code "3") (name "+3V@C08U1") (class "Default")
      (node (ref "C01") (pin "C1") (pinfunction "IN2_C1") (pintype "input"))
      (node (ref "C02") (pin "C1") (pinfunction "ENABLE_C1") (pintype "input"))
      (node (ref "C04") (pin "J1") (pinfunction "IN2_J1") (pintype "input"))
      (node (ref "C04") (pin "L2") (pinfunction "L2_L2") (pintype "input"))
      (node (ref "C04") (pin "N2") (pinfunction "N2_N2") (pintype "input"))
      (node (ref "C04") (pin "U2") (pinfunction "U2_U2") (pintype "input"))
      (node (ref "C05") (pin "J1") (pinfunction "IN2_J1") (pintype "input"))
      (node (ref "C05") (pin "L2") (pinfunction "L2_L2") (pintype "input"))
      (node (ref "C05") (pin "N2") (pinfunction "N2_N2") (pintype "input"))
      (node (ref "C05") (pin "U2") (pinfunction "U2_U2") (pintype "input"))
      (node (ref "C08") (pin "U1") (pinfunction "P$1_U1") (pintype "passive"))
    )
    (net (code "4") (name "+3V@C15U1") (class "Default")
      (node (ref "C14") (pin "A1") (pinfunction "R_A1") (pintype "input"))
      (node (ref "C14") (pin "D1") (pinfunction "S_D1") (pintype "input"))
      (node (ref "C14") (pin "F2") (pinfunction "S_F2") (pintype "input"))
      (node (ref "C14") (pin "K1") (pinfunction "S_K1") (pintype "input"))
      (node (ref "C14") (pin "K2") (pinfunction "R_K2") (pintype "input"))
      (node (ref "C15") (pin "U1") (pinfunction "P$1_U1") (pintype "passive"))
      (node (ref "C16") (pin "H2") (pinfunction "IN4_H2") (pintype "input"))
    )
    (net (code "5") (name "+3V@D09U1") (class "Default")
      (node (ref "D07") (pin "S1") (pinfunction "EN2_S1") (pintype "input"))
      (node (ref "D07") (pin "S2") (pinfunction "EN1_S2") (pintype "input"))
      (node (ref "D07") (pin "T2") (pinfunction "EN3_T2") (pintype "input"))
      (node (ref "D09") (pin "U1") (pinfunction "P$1_U1") (pintype "passive"))
    )
    (net (code "6") (name "+3V@D10U1") (class "Default")
      (node (ref "D10") (pin "L2") (pinfunction "IN6_L2") (pintype "input"))
      (node (ref "D10") (pin "M2") (pinfunction "IN7_M2") (pintype "input"))
      (node (ref "D10") (pin "N2") (pinfunction "IN8_N2") (pintype "input"))
      (node (ref "D10") (pin "U1") (pinfunction "P$1_U1") (pintype "passive"))
      (node (ref "D11") (pin "D1") (pinfunction "S_D1") (pintype "input"))
      (node (ref "D11") (pin "F2") (pinfunction "S_F2") (pintype "input"))
      (node (ref "D11") (pin "K1") (pinfunction "S_K1") (pintype "input"))
      (node (ref "D11") (pin "K2") (pinfunction "R_K2") (pintype "input"))
      (node (ref "D14") (pin "M1") (pinfunction "M1_M1") (pintype "input"))
    )
    (net (code "7") (name "+11V") (class "Default")
      (node (ref "AB01") (pin "BM2") (pinfunction "+11V_BM2") (pintype "power_in"))
    )
    (net (code "8") (name "-15V") (class "Default")
      (node (ref "AB01") (pin "AB2") (pinfunction "-15V_AB2") (pintype "power_in"))
      (node (ref "AB01") (pin "AE2") (pinfunction "-15V_AE2") (pintype "power_in"))
      (node (ref "AB01") (pin "AF2") (pinfunction "-15V_AF2") (pintype "power_in"))
    )
    (net (code "9") (name "00") (class "Default")
      (node (ref "A07") (pin "D2") (pinfunction "O0_D2") (pintype "output"))
    )
    (net (code "10") (name "0_TO_DTB") (class "Default")
      (node (ref "A11") (pin "M1") (pinfunction "OUT_M1") (pintype "output"))
      (node (ref "C11") (pin "R1") (pinfunction "IN2_R1") (pintype "input"))
    )
    (net (code "11") (name "0_TO_EF") (class "Default")
      (node (ref "A10") (pin "K2") (pinfunction "OUT_K2") (pintype "output"))
      (node (ref "A11") (pin "E2") (pinfunction "IN_E2") (pintype "input"))
    )
    (net (code "12") (name "0_TO_STA") (class "Default")
      (node (ref "A10") (pin "N2") (pinfunction "OUT_N2") (pintype "output"))
      (node (ref "A11") (pin "N1") (pinfunction "IN_N1") (pintype "input"))
    )
    (net (code "13") (name "01") (class "Default")
      (node (ref "A07") (pin "E2") (pinfunction "O1_E2") (pintype "output"))
    )
    (net (code "14") (name "1_TO_DF") (class "Default")
      (node (ref "A08") (pin "H1") (pinfunction "C_H1") (pintype "input"))
      (node (ref "C12") (pin "J1") (pinfunction "OUT_J1") (pintype "output"))
      (node (ref "C12") (pin "L1") (pinfunction "IN2_L1") (pintype "input"))
      (node (ref "D11") (pin "L2") (pinfunction "C_L2") (pintype "input"))
    )
    (net (code "15") (name "1_TO_DTF") (class "Default")
      (node (ref "B12") (pin "P2") (pinfunction "OUT_P2") (pintype "output"))
      (node (ref "D11") (pin "S2") (pinfunction "C_S2") (pintype "input"))
    )
    (net (code "16") (name "02") (class "Default")
      (node (ref "A07") (pin "J2") (pinfunction "O2_J2") (pintype "output"))
    )
    (net (code "17") (name "03") (class "Default")
      (node (ref "A07") (pin "N2") (pinfunction "O3_N2") (pintype "output"))
    )
    (net (code "18") (name "04") (class "Default")
      (node (ref "A07") (pin "F2") (pinfunction "O4_F2") (pintype "output"))
    )
    (net (code "19") (name "05") (class "Default")
      (node (ref "A07") (pin "M2") (pinfunction "O5_M2") (pintype "output"))
    )
    (net (code "20") (name "06") (class "Default")
      (node (ref "A07") (pin "H2") (pinfunction "O6_H2") (pintype "output"))
    )
    (net (code "21") (name "07") (class "Default")
      (node (ref "A07") (pin "L2") (pinfunction "O7_L2") (pintype "output"))
    )
    (net (code "22") (name "76") (class "Default")
      (node (ref "C04") (pin "V2") (pinfunction "V2_V2") (pintype "output"))
      (node (ref "C06") (pin "S2") (pinfunction "IN_S2") (pintype "input"))
    )
    (net (code "23") (name "76+77") (class "Default")
      (node (ref "C03") (pin "C1") (pinfunction "ENABLE_C1") (pintype "input"))
      (node (ref "D12") (pin "V2") (pinfunction "OUT_V2") (pintype "output"))
    )
    (net (code "24") (name "77") (class "Default")
      (node (ref "C05") (pin "V2") (pinfunction "V2_V2") (pintype "output"))
      (node (ref "C06") (pin "U2") (pinfunction "IN_U2") (pintype "input"))
    )
    (net (code "25") (name "ADDR_ACC") (class "Default")
      (node (ref "C02") (pin "V2") (pinfunction "O15_V2") (pintype "output"))
      (node (ref "C17") (pin "N1") (pinfunction "IN_N1") (pintype "input"))
    )
    (net (code "26") (name "B-BRK") (class "Default")
      (node (ref "B10") (pin "R2") (pinfunction "IN1_R2") (pintype "input"))
      (node (ref "B10") (pin "S2") (pinfunction "IN2_S2") (pintype "input"))
      (node (ref "B10") (pin "T2") (pinfunction "IN3_T2") (pintype "input"))
      (node (ref "B10") (pin "U2") (pinfunction "IN4_U2") (pintype "input"))
      (node (ref "C01") (pin "E1") (pinfunction "OUT_E1") (pintype "output"))
      (node (ref "D12") (pin "M1") (pinfunction "IN1_M1") (pintype "input"))
    )
    (net (code "27") (name "B-RUN") (class "Default")
      (node (ref "B11") (pin "N2") (pinfunction "IN1_N2") (pintype "input"))
      (node (ref "C01") (pin "B1") (pinfunction "OUT_B1") (pintype "output"))
    )
    (net (code "28") (name "B-XSTA") (class "Default")
      (node (ref "A10") (pin "E2") (pinfunction "IN2_E2") (pintype "input"))
      (node (ref "C11") (pin "P2") (pinfunction "IN1_P2") (pintype "input"))
      (node (ref "D12") (pin "E1") (pinfunction "OUT_E1") (pintype "output"))
    )
    (net (code "29") (name "BAC_00") (class "Default")
      (node (ref "B06") (pin "B1") (pinfunction "OUT_B1") (pintype "output"))
      (node (ref "B07") (pin "C1") (pinfunction "C1_C1") (pintype "input"))
      (node (ref "B07") (pin "D1") (pinfunction "D1_D1") (pintype "input"))
    )
    (net (code "30") (name "BAC_01") (class "Default")
      (node (ref "B06") (pin "E1") (pinfunction "OUT_E1") (pintype "output"))
      (node (ref "B07") (pin "E2") (pinfunction "E2_E2") (pintype "input"))
      (node (ref "B07") (pin "F2") (pinfunction "F2_F2") (pintype "input"))
    )
    (net (code "31") (name "BAC_02") (class "Default")
      (node (ref "B06") (pin "H1") (pinfunction "OUT_H1") (pintype "output"))
      (node (ref "B07") (pin "J1") (pinfunction "J1_J1") (pintype "input"))
      (node (ref "B07") (pin "K1") (pinfunction "K1_K1") (pintype "input"))
    )
    (net (code "32") (name "BAC_03") (class "Default")
      (node (ref "B06") (pin "K1") (pinfunction "OUT_K1") (pintype "output"))
      (node (ref "B07") (pin "M2") (pinfunction "M2_M2") (pintype "input"))
      (node (ref "B07") (pin "N2") (pinfunction "N2_N2") (pintype "input"))
    )
    (net (code "33") (name "BAC_04") (class "Default")
      (node (ref "B06") (pin "M1") (pinfunction "OUT_M1") (pintype "output"))
      (node (ref "C07") (pin "M2") (pinfunction "M2_M2") (pintype "input"))
      (node (ref "C07") (pin "N2") (pinfunction "N2_N2") (pintype "input"))
    )
    (net (code "34") (name "BAC_05") (class "Default")
      (node (ref "B06") (pin "P1") (pinfunction "OUT_P1") (pintype "output"))
      (node (ref "B07") (pin "P1") (pinfunction "P1_P1") (pintype "input"))
      (node (ref "B07") (pin "R1") (pinfunction "R1_R1") (pintype "input"))
    )
    (net (code "35") (name "BAC_06") (class "Default")
      (node (ref "B06") (pin "S1") (pinfunction "OUT_S1") (pintype "output"))
      (node (ref "B07") (pin "T2") (pinfunction "T2_T2") (pintype "input"))
      (node (ref "B07") (pin "U2") (pinfunction "U2_U2") (pintype "input"))
      (node (ref "D11") (pin "C1") (pinfunction "D_C1") (pintype "input"))
    )
    (net (code "36") (name "BAC_07") (class "Default")
      (node (ref "B06") (pin "U1") (pinfunction "OUT_U1") (pintype "output"))
      (node (ref "C07") (pin "C1") (pinfunction "C1_C1") (pintype "input"))
      (node (ref "C07") (pin "D1") (pinfunction "D1_D1") (pintype "input"))
      (node (ref "D11") (pin "E2") (pinfunction "D_E2") (pintype "input"))
    )
    (net (code "37") (name "BAC_08") (class "Default")
      (node (ref "B06") (pin "D2") (pinfunction "OUT_D2") (pintype "output"))
      (node (ref "C07") (pin "E2") (pinfunction "E2_E2") (pintype "input"))
      (node (ref "C07") (pin "F2") (pinfunction "F2_F2") (pintype "input"))
      (node (ref "D11") (pin "J1") (pinfunction "D_J1") (pintype "input"))
    )
    (net (code "38") (name "BAC_09") (class "Default")
      (node (ref "B06") (pin "F2") (pinfunction "OUT_F2") (pintype "output"))
      (node (ref "C07") (pin "J1") (pinfunction "J1_J1") (pintype "input"))
      (node (ref "C07") (pin "K1") (pinfunction "K1_K1") (pintype "input"))
    )
    (net (code "39") (name "BAC_10") (class "Default")
      (node (ref "B06") (pin "J2") (pinfunction "OUT_J2") (pintype "output"))
    )
    (net (code "40") (name "BAC_11") (class "Default")
      (node (ref "B06") (pin "L2") (pinfunction "OUT_L2") (pintype "output"))
    )
    (net (code "41") (name "BLK_IN_SYNC") (class "Default")
      (node (ref "C11") (pin "E2") (pinfunction "IN2_E2") (pintype "input"))
      (node (ref "C13") (pin "S1") (pinfunction "OUT_S1") (pintype "output"))
      (node (ref "CD18") (pin "AP2") (pinfunction "AP2_AP2") (pintype "input"))
    )
    (net (code "42") (name "BMB_00") (class "Default")
      (node (ref "C06") (pin "B1") (pinfunction "OUT_B1") (pintype "output"))
      (node (ref "C08") (pin "B1") (pinfunction "IN1B_B1") (pintype "input"))
    )
    (net (code "43") (name "BMB_01") (class "Default")
      (node (ref "C06") (pin "E1") (pinfunction "OUT_E1") (pintype "output"))
      (node (ref "C08") (pin "H1") (pinfunction "IN1B_H1") (pintype "input"))
    )
    (net (code "44") (name "BMB_02") (class "Default")
      (node (ref "C06") (pin "H1") (pinfunction "OUT_H1") (pintype "output"))
      (node (ref "C08") (pin "N1") (pinfunction "IN1B_N1") (pintype "input"))
    )
    (net (code "45") (name "BMB_03") (class "Default")
      (node (ref "C06") (pin "K1") (pinfunction "OUT_K1") (pintype "output"))
      (node (ref "C08") (pin "E2") (pinfunction "IN1B_E2") (pintype "input"))
    )
    (net (code "46") (name "BMB_04") (class "Default")
      (node (ref "C06") (pin "M1") (pinfunction "OUT_M1") (pintype "output"))
      (node (ref "C08") (pin "L2") (pinfunction "IN1B_L2") (pintype "input"))
    )
    (net (code "47") (name "BMB_05") (class "Default")
      (node (ref "C06") (pin "P1") (pinfunction "OUT_P1") (pintype "output"))
      (node (ref "C08") (pin "S2") (pinfunction "IN1B_S2") (pintype "input"))
    )
    (net (code "48") (name "BMB_06") (class "Default")
      (node (ref "B08") (pin "B1") (pinfunction "IN2_B1") (pintype "input"))
      (node (ref "C06") (pin "S1") (pinfunction "OUT_S1") (pintype "output"))
    )
    (net (code "49") (name "BMB_07") (class "Default")
      (node (ref "B08") (pin "E1") (pinfunction "IN2_E1") (pintype "input"))
      (node (ref "C06") (pin "U1") (pinfunction "OUT_U1") (pintype "output"))
    )
    (net (code "50") (name "BMB_08") (class "Default")
      (node (ref "B08") (pin "E2") (pinfunction "IN2_E2") (pintype "input"))
      (node (ref "C06") (pin "D2") (pinfunction "OUT_D2") (pintype "output"))
    )
    (net (code "51") (name "BMB_09") (class "Default")
      (node (ref "B08") (pin "M1") (pinfunction "IN2_M1") (pintype "input"))
      (node (ref "C06") (pin "F2") (pinfunction "OUT_F2") (pintype "output"))
    )
    (net (code "52") (name "BMB_10") (class "Default")
      (node (ref "B08") (pin "R1") (pinfunction "IN2_R1") (pintype "input"))
      (node (ref "C06") (pin "J2") (pinfunction "OUT_J2") (pintype "output"))
    )
    (net (code "53") (name "BMB_11") (class "Default")
      (node (ref "B08") (pin "J1") (pinfunction "IN2_J1") (pintype "input"))
      (node (ref "C06") (pin "L2") (pinfunction "OUT_L2") (pintype "output"))
    )
    (net (code "54") (name "BMB_TO_DTB") (class "Default")
      (node (ref "B08") (pin "A1") (pinfunction "IN1_A1") (pintype "input"))
      (node (ref "B08") (pin "D1") (pinfunction "IN1_D1") (pintype "input"))
      (node (ref "B08") (pin "D2") (pinfunction "IN1_D2") (pintype "input"))
      (node (ref "B08") (pin "H1") (pinfunction "IN1_H1") (pintype "input"))
      (node (ref "B08") (pin "L1") (pinfunction "IN1_L1") (pintype "input"))
      (node (ref "B08") (pin "P1") (pinfunction "IN1_P1") (pintype "input"))
      (node (ref "C08") (pin "A1") (pinfunction "IN1A_A1") (pintype "input"))
      (node (ref "C08") (pin "D2") (pinfunction "IN1A_D2") (pintype "input"))
      (node (ref "C08") (pin "F1") (pinfunction "IN1A_F1") (pintype "input"))
      (node (ref "C08") (pin "K2") (pinfunction "IN1A_K2") (pintype "input"))
      (node (ref "C08") (pin "M1") (pinfunction "IN1A_M1") (pintype "input"))
      (node (ref "C08") (pin "R2") (pinfunction "IN1A_R2") (pintype "input"))
      (node (ref "D12") (pin "L1") (pinfunction "OUT_L1") (pintype "output"))
    )
    (net (code "55") (name "BMR00") (class "Default")
      (node (ref "A23") (pin "F1") (pinfunction "A_F1") (pintype "input"))
      (node (ref "B14") (pin "P2") (pinfunction "1_P2") (pintype "output"))
    )
    (net (code "56") (name "BMR01") (class "Default")
      (node (ref "A23") (pin "B1") (pinfunction "B_B1") (pintype "input"))
      (node (ref "B14") (pin "F1") (pinfunction "0_F1") (pintype "output"))
    )
    (net (code "57") (name "C00") (class "Default")
      (node (ref "A12") (pin "L2") (pinfunction "IN1_L2") (pintype "input"))
      (node (ref "A26") (pin "E2") (pinfunction "P$2_E2") (pintype "bidirectional"))
      (node (ref "B12") (pin "R2") (pinfunction "IN1_R2") (pintype "input"))
      (node (ref "B13") (pin "S1") (pinfunction "1_S1") (pintype "output"))
      (node (ref "C15") (pin "E2") (pinfunction "IN2_E2") (pintype "input"))
      (node (ref "D10") (pin "C1") (pinfunction "IN3_C1") (pintype "input"))
    )
    (net (code "58") (name "C01") (class "Default")
      (node (ref "A12") (pin "M2") (pinfunction "IN2_M2") (pintype "input"))
      (node (ref "A26") (pin "F2") (pinfunction "P$2_F2") (pintype "bidirectional"))
      (node (ref "B10") (pin "J1") (pinfunction "IN3_J1") (pintype "input"))
      (node (ref "B11") (pin "V2") (pinfunction "IN3_V2") (pintype "input"))
      (node (ref "B13") (pin "P2") (pinfunction "1_P2") (pintype "output"))
    )
    (net (code "59") (name "CK00") (class "Default")
      (node (ref "A18") (pin "P2") (pinfunction "P2_P2") (pintype "input"))
      (node (ref "B14") (pin "S1") (pinfunction "1_S1") (pintype "output"))
    )
    (net (code "60") (name "CK01") (class "Default")
      (node (ref "B14") (pin "P1") (pinfunction "D_P1") (pintype "input"))
      (node (ref "B14") (pin "V2") (pinfunction "1_V2") (pintype "output"))
      (node (ref "C16") (pin "N1") (pinfunction "IN2_N1") (pintype "input"))
      (node (ref "C16") (pin "P1") (pinfunction "IN3_P1") (pintype "input"))
      (node (ref "C16") (pin "R1") (pinfunction "IN4_R1") (pintype "input"))
    )
    (net (code "61") (name "COMP+SH") (class "Default")
      (node (ref "A12") (pin "D2") (pinfunction "IN1_D2") (pintype "input"))
      (node (ref "C14") (pin "B1") (pinfunction "C_B1") (pintype "input"))
      (node (ref "C14") (pin "D2") (pinfunction "C_D2") (pintype "input"))
      (node (ref "C14") (pin "H1") (pinfunction "C_H1") (pintype "input"))
      (node (ref "C15") (pin "K1") (pinfunction "OUT_K1") (pintype "output"))
    )
    (net (code "62") (name "CSTA") (class "Default")
      (node (ref "C04") (pin "C1") (pinfunction "C1_C1") (pintype "output"))
      (node (ref "D16") (pin "P2") (pinfunction "K2_P2") (pintype "input"))
    )
    (net (code "63") (name "DATA") (class "Default")
      (node (ref "A26") (pin "M1") (pinfunction "P$2_M1") (pintype "bidirectional"))
      (node (ref "C13") (pin "F1") (pinfunction "IN_F1") (pintype "input"))
      (node (ref "CD18") (pin "BK2") (pinfunction "BK2_BK2") (pintype "output"))
    )
    (net (code "64") (name "DF") (class "Default")
      (node (ref "A10") (pin "P2") (pinfunction "IN1_P2") (pintype "input"))
      (node (ref "A26") (pin "E1") (pinfunction "P$2_E1") (pintype "bidirectional"))
      (node (ref "D11") (pin "R2") (pinfunction "0_R2") (pintype "output"))
    )
    (net (code "65") (name "DTB_00") (class "Default")
      (node (ref "A25") (pin "A2") (pinfunction "P$2_A2") (pintype "bidirectional"))
      (node (ref "C09") (pin "E1") (pinfunction "1_E1") (pintype "output"))
      (node (ref "C10") (pin "B1") (pinfunction "IN1B_B1") (pintype "input"))
      (node (ref "D09") (pin "D2") (pinfunction "IN1A_D2") (pintype "input"))
    )
    (net (code "66") (name "DTB_01") (class "Default")
      (node (ref "A25") (pin "B2") (pinfunction "P$2_B2") (pintype "bidirectional"))
      (node (ref "C09") (pin "H2") (pinfunction "1_H2") (pintype "output"))
      (node (ref "C10") (pin "H1") (pinfunction "IN1B_H1") (pintype "input"))
      (node (ref "D09") (pin "K2") (pinfunction "IN1A_K2") (pintype "input"))
    )
    (net (code "67") (name "DTB_02") (class "Default")
      (node (ref "A25") (pin "C2") (pinfunction "P$2_C2") (pintype "bidirectional"))
      (node (ref "C09") (pin "L1") (pinfunction "1_L1") (pintype "output"))
      (node (ref "C10") (pin "N1") (pinfunction "IN1B_N1") (pintype "input"))
      (node (ref "D09") (pin "R2") (pinfunction "IN1A_R2") (pintype "input"))
    )
    (net (code "68") (name "DTB_03") (class "Default")
      (node (ref "A25") (pin "D2") (pinfunction "P$2_D2") (pintype "bidirectional"))
      (node (ref "C09") (pin "C1") (pinfunction "D_C1") (pintype "input"))
      (node (ref "C09") (pin "P2") (pinfunction "1_P2") (pintype "output"))
    )
    (net (code "69") (name "DTB_04") (class "Default")
      (node (ref "A25") (pin "E2") (pinfunction "P$2_E2") (pintype "bidirectional"))
      (node (ref "C09") (pin "E2") (pinfunction "D_E2") (pintype "input"))
      (node (ref "C09") (pin "S1") (pinfunction "1_S1") (pintype "output"))
    )
    (net (code "70") (name "DTB_05") (class "Default")
      (node (ref "A25") (pin "F2") (pinfunction "P$2_F2") (pintype "bidirectional"))
      (node (ref "C09") (pin "J1") (pinfunction "D_J1") (pintype "input"))
      (node (ref "C09") (pin "V2") (pinfunction "1_V2") (pintype "output"))
    )
    (net (code "71") (name "DTB_06") (class "Default")
      (node (ref "A25") (pin "H2") (pinfunction "P$2_H2") (pintype "bidirectional"))
      (node (ref "B09") (pin "E1") (pinfunction "1_E1") (pintype "output"))
      (node (ref "C09") (pin "M2") (pinfunction "D_M2") (pintype "input"))
    )
    (net (code "72") (name "DTB_07") (class "Default")
      (node (ref "A25") (pin "J2") (pinfunction "P$2_J2") (pintype "bidirectional"))
      (node (ref "B09") (pin "V2") (pinfunction "1_V2") (pintype "output"))
      (node (ref "C09") (pin "P1") (pinfunction "D_P1") (pintype "input"))
    )
    (net (code "73") (name "DTB_08") (class "Default")
      (node (ref "A25") (pin "K2") (pinfunction "P$2_K2") (pintype "bidirectional"))
      (node (ref "B09") (pin "L1") (pinfunction "1_L1") (pintype "output"))
      (node (ref "C09") (pin "T2") (pinfunction "D_T2") (pintype "input"))
    )
    (net (code "74") (name "DTB_09") (class "Default")
      (node (ref "A25") (pin "L2") (pinfunction "P$2_L2") (pintype "bidirectional"))
      (node (ref "B09") (pin "C1") (pinfunction "D_C1") (pintype "input"))
      (node (ref "B09") (pin "P2") (pinfunction "1_P2") (pintype "output"))
    )
    (net (code "75") (name "DTB_10") (class "Default")
      (node (ref "A25") (pin "M2") (pinfunction "P$2_M2") (pintype "bidirectional"))
      (node (ref "B09") (pin "S1") (pinfunction "1_S1") (pintype "output"))
      (node (ref "B09") (pin "T2") (pinfunction "D_T2") (pintype "input"))
    )
    (net (code "76") (name "DTB_11") (class "Default")
      (node (ref "A25") (pin "N2") (pinfunction "P$2_N2") (pintype "bidirectional"))
      (node (ref "B09") (pin "H2") (pinfunction "1_H2") (pintype "output"))
      (node (ref "B09") (pin "J1") (pinfunction "D_J1") (pintype "input"))
    )
    (net (code "77") (name "DTF") (class "Default")
      (node (ref "A08") (pin "J1") (pinfunction "D_J1") (pintype "input"))
      (node (ref "A12") (pin "M1") (pinfunction "IN2_M1") (pintype "input"))
      (node (ref "A26") (pin "C1") (pinfunction "P$2_C1") (pintype "bidirectional"))
      (node (ref "D11") (pin "V1") (pinfunction "0_V1") (pintype "output"))
    )
    (net (code "78") (name "DTSF") (class "Default")
      (node (ref "A12") (pin "R1") (pinfunction "IN2_R1") (pintype "input"))
      (node (ref "C05") (pin "A1") (pinfunction "A1_A1") (pintype "output"))
    )
    (net (code "79") (name "EF") (class "Default")
      (node (ref "A11") (pin "J1") (pinfunction "IN_J1") (pintype "input"))
      (node (ref "A12") (pin "F1") (pinfunction "OUT_F1") (pintype "output"))
      (node (ref "A12") (pin "L1") (pinfunction "IN1_L1") (pintype "input"))
      (node (ref "A25") (pin "N1") (pinfunction "P$2_N1") (pintype "bidirectional"))
    )
    (net (code "80") (name "END") (class "Default")
      (node (ref "A08") (pin "E1") (pinfunction "1_E1") (pintype "output"))
      (node (ref "A25") (pin "R1") (pinfunction "P$2_R1") (pintype "bidirectional"))
    )
    (net (code "81") (name "ENI") (class "Default")
      (node (ref "A12") (pin "H1") (pinfunction "IN1_H1") (pintype "input"))
      (node (ref "A25") (pin "L1") (pinfunction "P$2_L1") (pintype "bidirectional"))
      (node (ref "C07") (pin "L1") (pinfunction "L1_L1") (pintype "output"))
    )
    (net (code "82") (name "FR_00") (class "Default")
      (node (ref "A25") (pin "F1") (pinfunction "P$2_F1") (pintype "bidirectional"))
      (node (ref "B07") (pin "S1") (pinfunction "S1_S1") (pintype "output"))
      (node (ref "B12") (pin "E2") (pinfunction "IN2_E2") (pintype "input"))
      (node (ref "C12") (pin "U2") (pinfunction "IN2_U2") (pintype "input"))
    )
    (net (code "83") (name "FR_01") (class "Default")
      (node (ref "A10") (pin "H1") (pinfunction "IN1_H1") (pintype "input"))
      (node (ref "A25") (pin "H1") (pinfunction "P$2_H1") (pintype "bidirectional"))
      (node (ref "B07") (pin "V2") (pinfunction "V2_V2") (pintype "output"))
      (node (ref "B15") (pin "M1") (pinfunction "IN2_M1") (pintype "input"))
      (node (ref "C15") (pin "D1") (pinfunction "IN1_D1") (pintype "input"))
      (node (ref "D07") (pin "V2") (pinfunction "IN2_V2") (pintype "input"))
      (node (ref "D12") (pin "R1") (pinfunction "IN4_R1") (pintype "input"))
    )
    (net (code "84") (name "FR_02") (class "Default")
      (node (ref "A25") (pin "J1") (pinfunction "P$2_J1") (pintype "bidirectional"))
      (node (ref "C07") (pin "E1") (pinfunction "E1_E1") (pintype "output"))
      (node (ref "D07") (pin "U2") (pinfunction "IN1_U2") (pintype "input"))
    )
    (net (code "85") (name "FR_03") (class "Default")
      (node (ref "A25") (pin "K1") (pinfunction "P$2_K1") (pintype "bidirectional"))
      (node (ref "B15") (pin "R2") (pinfunction "IN2_R2") (pintype "input"))
      (node (ref "C07") (pin "H2") (pinfunction "H2_H2") (pintype "output"))
      (node (ref "D07") (pin "V1") (pinfunction "IN0_V1") (pintype "input"))
    )
    (net (code "86") (name "GND") (class "Default")
      (node (ref "A05") (pin "B1") (pinfunction "P$2_B1") (pintype "bidirectional"))
      (node (ref "A05") (pin "D1") (pinfunction "P$2_D1") (pintype "bidirectional"))
      (node (ref "A05") (pin "D2") (pinfunction "P$2_D2") (pintype "bidirectional"))
      (node (ref "A05") (pin "E1") (pinfunction "P$2_E1") (pintype "bidirectional"))
      (node (ref "A05") (pin "H1") (pinfunction "P$2_H1") (pintype "bidirectional"))
      (node (ref "A05") (pin "J1") (pinfunction "P$2_J1") (pintype "bidirectional"))
      (node (ref "A05") (pin "L1") (pinfunction "P$2_L1") (pintype "bidirectional"))
      (node (ref "A05") (pin "M1") (pinfunction "P$2_M1") (pintype "bidirectional"))
      (node (ref "A05") (pin "P1") (pinfunction "P$2_P1") (pintype "bidirectional"))
      (node (ref "A05") (pin "S1") (pinfunction "P$2_S1") (pintype "bidirectional"))
      (node (ref "A06") (pin "K2") (pinfunction "P$2_K2") (pintype "bidirectional"))
      (node (ref "A07") (pin "U1") (pinfunction "IN*_U1") (pintype "input"))
      (node (ref "A08") (pin "T2") (pinfunction "D_T2") (pintype "input"))
      (node (ref "A23") (pin "C1") (pinfunction "C_C1") (pintype "input"))
      (node (ref "A23") (pin "F2") (pinfunction "C_F2") (pintype "input"))
      (node (ref "A23") (pin "J1") (pinfunction "C_J1") (pintype "input"))
      (node (ref "A23") (pin "M2") (pinfunction "C_M2") (pintype "input"))
      (node (ref "A23") (pin "P1") (pinfunction "C_P1") (pintype "input"))
      (node (ref "A23") (pin "T2") (pinfunction "C_T2") (pintype "input"))
      (node (ref "A25") (pin "M1") (pinfunction "P$2_M1") (pintype "bidirectional"))
      (node (ref "A26") (pin "D2") (pinfunction "P$2_D2") (pintype "bidirectional"))
      (node (ref "A26") (pin "U2") (pinfunction "P$2_U2") (pintype "bidirectional"))
      (node (ref "A26") (pin "V1") (pinfunction "P$2_V1") (pintype "bidirectional"))
      (node (ref "AB01") (pin "AC2") (pinfunction "GND_AC2") (pintype "power_in"))
      (node (ref "AB01") (pin "AH2") (pinfunction "GND_AH2") (pintype "power_in"))
      (node (ref "AB01") (pin "AK2") (pinfunction "GND_AK2") (pintype "power_in"))
      (node (ref "AB01") (pin "AL2") (pinfunction "GND_AL2") (pintype "power_in"))
      (node (ref "AB01") (pin "AT1") (pinfunction "GND_AT1") (pintype "power_in"))
      (node (ref "AB01") (pin "BC2") (pinfunction "GND_BC2") (pintype "power_in"))
      (node (ref "AB01") (pin "BD2") (pinfunction "GND_BD2") (pintype "power_in"))
      (node (ref "AB01") (pin "BH2") (pinfunction "GND_BH2") (pintype "power_in"))
      (node (ref "AB01") (pin "BK2") (pinfunction "GND_BK2") (pintype "power_in"))
      (node (ref "AB01") (pin "BL2") (pinfunction "GND_BL2") (pintype "power_in"))
      (node (ref "AB01") (pin "BT1") (pinfunction "GND_BT1") (pintype "power_in"))
      (node (ref "AB19") (pin "AJ2") (pinfunction "P$2_AJ2") (pintype "bidirectional"))
      (node (ref "AB19") (pin "AR2") (pinfunction "P$2_AR2") (pintype "bidirectional"))
      (node (ref "AB19") (pin "AU2") (pinfunction "P$2_AU2") (pintype "bidirectional"))
      (node (ref "AB19") (pin "BF2") (pinfunction "P$2_BF2") (pintype "bidirectional"))
      (node (ref "AB19") (pin "BM2") (pinfunction "P$2_BM2") (pintype "bidirectional"))
      (node (ref "B05") (pin "C1") (pinfunction "C_C1") (pintype "input"))
      (node (ref "B05") (pin "F2") (pinfunction "C_F2") (pintype "input"))
      (node (ref "B05") (pin "J1") (pinfunction "C_J1") (pintype "input"))
      (node (ref "B05") (pin "M2") (pinfunction "C_M2") (pintype "input"))
      (node (ref "B05") (pin "P1") (pinfunction "C_P1") (pintype "input"))
      (node (ref "B22") (pin "T2") (pinfunction "C_T2") (pintype "input"))
      (node (ref "D05") (pin "B1") (pinfunction "P$2_B1") (pintype "bidirectional"))
      (node (ref "D05") (pin "D1") (pinfunction "P$2_D1") (pintype "bidirectional"))
      (node (ref "D05") (pin "D2") (pinfunction "P$2_D2") (pintype "bidirectional"))
      (node (ref "D05") (pin "E1") (pinfunction "P$2_E1") (pintype "bidirectional"))
      (node (ref "D05") (pin "H1") (pinfunction "P$2_H1") (pintype "bidirectional"))
      (node (ref "D05") (pin "J1") (pinfunction "P$2_J1") (pintype "bidirectional"))
      (node (ref "D05") (pin "L1") (pinfunction "P$2_L1") (pintype "bidirectional"))
      (node (ref "D05") (pin "M1") (pinfunction "P$2_M1") (pintype "bidirectional"))
      (node (ref "D05") (pin "P1") (pinfunction "P$2_P1") (pintype "bidirectional"))
      (node (ref "D05") (pin "S1") (pinfunction "P$2_S1") (pintype "bidirectional"))
      (node (ref "D06") (pin "K2") (pinfunction "P$2_K2") (pintype "bidirectional"))
      (node (ref "D07") (pin "U1") (pinfunction "IN*_U1") (pintype "input"))
      (node (ref "D11") (pin "P1") (pinfunction "D_P1") (pintype "input"))
      (node (ref "D11") (pin "T2") (pinfunction "D_T2") (pintype "input"))
    )
    (net (code "87") (name "IOP_1") (class "Default")
      (node (ref "A02") (pin "K2") (pinfunction "P$2_K2") (pintype "bidirectional"))
      (node (ref "C04") (pin "P2") (pinfunction "P2_P2") (pintype "input"))
      (node (ref "C05") (pin "P2") (pinfunction "P2_P2") (pintype "input"))
      (node (ref "D02") (pin "K2") (pinfunction "P$2_K2") (pintype "bidirectional"))
    )
    (net (code "88") (name "IOP_2") (class "Default")
      (node (ref "A02") (pin "M2") (pinfunction "P$2_M2") (pintype "bidirectional"))
      (node (ref "C04") (pin "R2") (pinfunction "R2_R2") (pintype "input"))
      (node (ref "C05") (pin "R2") (pinfunction "R2_R2") (pintype "input"))
      (node (ref "D02") (pin "M2") (pinfunction "P$2_M2") (pintype "bidirectional"))
    )
    (net (code "89") (name "IOP_4") (class "Default")
      (node (ref "A02") (pin "P2") (pinfunction "P$2_P2") (pintype "bidirectional"))
      (node (ref "C04") (pin "S2") (pinfunction "S2_S2") (pintype "input"))
      (node (ref "C05") (pin "S2") (pinfunction "S2_S2") (pintype "input"))
      (node (ref "D02") (pin "P2") (pinfunction "P$2_P2") (pintype "bidirectional"))
    )
    (net (code "90") (name "I{slash}O_B-BRK") (class "Default")
      (node (ref "A05") (pin "P2") (pinfunction "P$2_P2") (pintype "bidirectional"))
      (node (ref "C01") (pin "D1") (pinfunction "IN_D1") (pintype "input"))
      (node (ref "D05") (pin "P2") (pinfunction "P$2_P2") (pintype "bidirectional"))
    )
    (net (code "91") (name "I{slash}O_B-RUN") (class "Default")
      (node (ref "A04") (pin "S2") (pinfunction "P$2_S2") (pintype "bidirectional"))
      (node (ref "C01") (pin "A1") (pinfunction "IN1_A1") (pintype "input"))
      (node (ref "D04") (pin "S2") (pinfunction "P$2_S2") (pintype "bidirectional"))
    )
    (net (code "92") (name "I{slash}O_BAC_00") (class "Default")
      (node (ref "A02") (pin "B1") (pinfunction "P$2_B1") (pintype "bidirectional"))
      (node (ref "C03") (pin "A1") (pinfunction "IN1_A1") (pintype "input"))
      (node (ref "D02") (pin "B1") (pinfunction "P$2_B1") (pintype "bidirectional"))
    )
    (net (code "93") (name "I{slash}O_BAC_01") (class "Default")
      (node (ref "A02") (pin "D1") (pinfunction "P$2_D1") (pintype "bidirectional"))
      (node (ref "C03") (pin "D1") (pinfunction "IN2_D1") (pintype "input"))
      (node (ref "D02") (pin "D1") (pinfunction "P$2_D1") (pintype "bidirectional"))
    )
    (net (code "94") (name "I{slash}O_BAC_02") (class "Default")
      (node (ref "A02") (pin "E1") (pinfunction "P$2_E1") (pintype "bidirectional"))
      (node (ref "C03") (pin "F1") (pinfunction "IN3_F1") (pintype "input"))
      (node (ref "D02") (pin "E1") (pinfunction "P$2_E1") (pintype "bidirectional"))
    )
    (net (code "95") (name "I{slash}O_BAC_03") (class "Default")
      (node (ref "A02") (pin "H1") (pinfunction "P$2_H1") (pintype "bidirectional"))
      (node (ref "C03") (pin "J1") (pinfunction "IN4_J1") (pintype "input"))
      (node (ref "D02") (pin "H1") (pinfunction "P$2_H1") (pintype "bidirectional"))
    )
    (net (code "96") (name "I{slash}O_BAC_04") (class "Default")
      (node (ref "A02") (pin "J1") (pinfunction "P$2_J1") (pintype "bidirectional"))
      (node (ref "C03") (pin "L1") (pinfunction "IN5_L1") (pintype "input"))
      (node (ref "D02") (pin "J1") (pinfunction "P$2_J1") (pintype "bidirectional"))
    )
    (net (code "97") (name "I{slash}O_BAC_05") (class "Default")
      (node (ref "A02") (pin "L1") (pinfunction "P$2_L1") (pintype "bidirectional"))
      (node (ref "C03") (pin "N1") (pinfunction "IN6_N1") (pintype "input"))
      (node (ref "D02") (pin "L1") (pinfunction "P$2_L1") (pintype "bidirectional"))
    )
    (net (code "98") (name "I{slash}O_BAC_06") (class "Default")
      (node (ref "A02") (pin "M1") (pinfunction "P$2_M1") (pintype "bidirectional"))
      (node (ref "C03") (pin "R1") (pinfunction "IN7_R1") (pintype "input"))
      (node (ref "D02") (pin "M1") (pinfunction "P$2_M1") (pintype "bidirectional"))
    )
    (net (code "99") (name "I{slash}O_BAC_07") (class "Default")
      (node (ref "A02") (pin "P1") (pinfunction "P$2_P1") (pintype "bidirectional"))
      (node (ref "C03") (pin "V1") (pinfunction "IN8_V1") (pintype "input"))
      (node (ref "D02") (pin "P1") (pinfunction "P$2_P1") (pintype "bidirectional"))
    )
    (net (code "100") (name "I{slash}O_BAC_08") (class "Default")
      (node (ref "A02") (pin "S1") (pinfunction "P$2_S1") (pintype "bidirectional"))
      (node (ref "C03") (pin "E2") (pinfunction "IN9_E2") (pintype "input"))
      (node (ref "D02") (pin "S1") (pinfunction "P$2_S1") (pintype "bidirectional"))
    )
    (net (code "101") (name "I{slash}O_BAC_09") (class "Default")
      (node (ref "A02") (pin "D2") (pinfunction "P$2_D2") (pintype "bidirectional"))
      (node (ref "C03") (pin "H2") (pinfunction "IN10_H2") (pintype "input"))
      (node (ref "D02") (pin "D2") (pinfunction "P$2_D2") (pintype "bidirectional"))
    )
    (net (code "102") (name "I{slash}O_BAC_10") (class "Default")
      (node (ref "A02") (pin "E2") (pinfunction "P$2_E2") (pintype "bidirectional"))
      (node (ref "C03") (pin "K2") (pinfunction "IN11_K2") (pintype "input"))
      (node (ref "D02") (pin "E2") (pinfunction "P$2_E2") (pintype "bidirectional"))
    )
    (net (code "103") (name "I{slash}O_BAC_11") (class "Default")
      (node (ref "A02") (pin "H2") (pinfunction "P$2_H2") (pintype "bidirectional"))
      (node (ref "C03") (pin "M2") (pinfunction "IN12_M2") (pintype "input"))
      (node (ref "D02") (pin "H2") (pinfunction "P$2_H2") (pintype "bidirectional"))
    )
    (net (code "104") (name "I{slash}O_BMB_00") (class "Default")
      (node (ref "A03") (pin "B1") (pinfunction "P$2_B1") (pintype "bidirectional"))
      (node (ref "C02") (pin "A1") (pinfunction "IN1_A1") (pintype "input"))
      (node (ref "D03") (pin "B1") (pinfunction "P$2_B1") (pintype "bidirectional"))
    )
    (net (code "105") (name "I{slash}O_BMB_01") (class "Default")
      (node (ref "A03") (pin "D1") (pinfunction "P$2_D1") (pintype "bidirectional"))
      (node (ref "C02") (pin "D1") (pinfunction "IN2_D1") (pintype "input"))
      (node (ref "D03") (pin "D1") (pinfunction "P$2_D1") (pintype "bidirectional"))
    )
    (net (code "106") (name "I{slash}O_BMB_02") (class "Default")
      (node (ref "A03") (pin "E1") (pinfunction "P$2_E1") (pintype "bidirectional"))
      (node (ref "C02") (pin "F1") (pinfunction "IN3_F1") (pintype "input"))
      (node (ref "D03") (pin "E1") (pinfunction "P$2_E1") (pintype "bidirectional"))
    )
    (net (code "107") (name "I{slash}O_BMB_03") (class "Default")
      (node (ref "A03") (pin "J1") (pinfunction "P$2_J1") (pintype "bidirectional"))
      (node (ref "C02") (pin "J1") (pinfunction "IN4_J1") (pintype "input"))
      (node (ref "C04") (pin "D2") (pinfunction "D2_D2") (pintype "input"))
      (node (ref "C05") (pin "D2") (pinfunction "D2_D2") (pintype "input"))
      (node (ref "D03") (pin "J1") (pinfunction "P$2_J1") (pintype "bidirectional"))
    )
    (net (code "108") (name "I{slash}O_BMB_04") (class "Default")
      (node (ref "A03") (pin "M1") (pinfunction "P$2_M1") (pintype "bidirectional"))
      (node (ref "C02") (pin "L1") (pinfunction "IN5_L1") (pintype "input"))
      (node (ref "C04") (pin "E2") (pinfunction "E2_E2") (pintype "input"))
      (node (ref "C05") (pin "E2") (pinfunction "E2_E2") (pintype "input"))
      (node (ref "D03") (pin "M1") (pinfunction "P$2_M1") (pintype "bidirectional"))
    )
    (net (code "109") (name "I{slash}O_BMB_05") (class "Default")
      (node (ref "A03") (pin "S1") (pinfunction "P$2_S1") (pintype "bidirectional"))
      (node (ref "C02") (pin "N1") (pinfunction "IN6_N1") (pintype "input"))
      (node (ref "C04") (pin "F2") (pinfunction "F2_F2") (pintype "input"))
      (node (ref "C05") (pin "F2") (pinfunction "F2_F2") (pintype "input"))
      (node (ref "D03") (pin "S1") (pinfunction "P$2_S1") (pintype "bidirectional"))
    )
    (net (code "110") (name "I{slash}O_BMB_06") (class "Default")
      (node (ref "A03") (pin "E2") (pinfunction "P$2_E2") (pintype "bidirectional"))
      (node (ref "C02") (pin "R1") (pinfunction "IN7_R1") (pintype "input"))
      (node (ref "C04") (pin "H2") (pinfunction "H2_H2") (pintype "input"))
      (node (ref "C05") (pin "H2") (pinfunction "H2_H2") (pintype "input"))
      (node (ref "D03") (pin "E2") (pinfunction "P$2_E2") (pintype "bidirectional"))
    )
    (net (code "111") (name "I{slash}O_BMB_07") (class "Default")
      (node (ref "A03") (pin "K2") (pinfunction "P$2_K2") (pintype "bidirectional"))
      (node (ref "C02") (pin "V1") (pinfunction "IN8_V1") (pintype "input"))
      (node (ref "C04") (pin "J2") (pinfunction "J2_J2") (pintype "input"))
      (node (ref "C05") (pin "J2") (pinfunction "J2_J2") (pintype "input"))
      (node (ref "D03") (pin "K2") (pinfunction "P$2_K2") (pintype "bidirectional"))
    )
    (net (code "112") (name "I{slash}O_BMB_08") (class "Default")
      (node (ref "A03") (pin "P2") (pinfunction "P$2_P2") (pintype "bidirectional"))
      (node (ref "C02") (pin "E2") (pinfunction "IN9_E2") (pintype "input"))
      (node (ref "C05") (pin "K2") (pinfunction "K2_K2") (pintype "input"))
      (node (ref "D03") (pin "P2") (pinfunction "P$2_P2") (pintype "bidirectional"))
    )
    (net (code "113") (name "I{slash}O_BMB_09") (class "Default")
      (node (ref "A03") (pin "S2") (pinfunction "P$2_S2") (pintype "bidirectional"))
      (node (ref "C02") (pin "H2") (pinfunction "IN10_H2") (pintype "input"))
      (node (ref "D03") (pin "S2") (pinfunction "P$2_S2") (pintype "bidirectional"))
    )
    (net (code "114") (name "I{slash}O_BMB_10") (class "Default")
      (node (ref "A03") (pin "T2") (pinfunction "P$2_T2") (pintype "bidirectional"))
      (node (ref "C02") (pin "K2") (pinfunction "IN11_K2") (pintype "input"))
      (node (ref "D03") (pin "T2") (pinfunction "P$2_T2") (pintype "bidirectional"))
    )
    (net (code "115") (name "I{slash}O_BMB_11") (class "Default")
      (node (ref "A03") (pin "V2") (pinfunction "P$2_V2") (pintype "bidirectional"))
      (node (ref "C02") (pin "M2") (pinfunction "IN12_M2") (pintype "input"))
      (node (ref "D03") (pin "V2") (pinfunction "P$2_V2") (pintype "bidirectional"))
    )
    (net (code "116") (name "I{slash}O_DATA_IN") (class "Default")
      (node (ref "A05") (pin "M2") (pinfunction "P$2_M2") (pintype "bidirectional"))
      (node (ref "B05") (pin "J2") (pinfunction "E_J2") (pintype "open_collector"))
      (node (ref "D05") (pin "M2") (pinfunction "P$2_M2") (pintype "bidirectional"))
    )
    (net (code "117") (name "I{slash}O_PWR_CLR") (class "Default")
      (node (ref "A02") (pin "V2") (pinfunction "P$2_V2") (pintype "bidirectional"))
      (node (ref "C05") (pin "H1") (pinfunction "IN1_H1") (pintype "input"))
      (node (ref "D02") (pin "V2") (pinfunction "P$2_V2") (pintype "bidirectional"))
    )
    (net (code "118") (name "I{slash}O_TS03") (class "Default")
      (node (ref "A02") (pin "S2") (pinfunction "P$2_S2") (pintype "bidirectional"))
      (node (ref "C04") (pin "H1") (pinfunction "IN1_H1") (pintype "input"))
      (node (ref "D02") (pin "S2") (pinfunction "P$2_S2") (pintype "bidirectional"))
    )
    (net (code "119") (name "I{slash}O_TS04") (class "Default")
      (node (ref "A02") (pin "T2") (pinfunction "P$2_T2") (pintype "bidirectional"))
      (node (ref "D02") (pin "T2") (pinfunction "P$2_T2") (pintype "bidirectional"))
    )
    (net (code "120") (name "I{slash}~{O_0_TO_AC}") (class "Default")
      (node (ref "A04") (pin "P2") (pinfunction "P$2_P2") (pintype "bidirectional"))
      (node (ref "B05") (pin "L1") (pinfunction "E_L1") (pintype "open_collector"))
      (node (ref "D04") (pin "P2") (pinfunction "P$2_P2") (pintype "bidirectional"))
    )
    (net (code "121") (name "I{slash}~{O_1_TO_CA_INH}") (class "Default")
      (node (ref "A06") (pin "M2") (pinfunction "P$2_M2") (pintype "bidirectional"))
      (node (ref "B05") (pin "N2") (pinfunction "D_N2") (pintype "open_collector"))
      (node (ref "D06") (pin "M2") (pinfunction "P$2_M2") (pintype "bidirectional"))
    )
    (net (code "122") (name "I{slash}~{O_ADDR_ACC}") (class "Default")
      (node (ref "A05") (pin "S2") (pinfunction "P$2_S2") (pintype "bidirectional"))
      (node (ref "C02") (pin "U2") (pinfunction "IN15_U2") (pintype "input"))
      (node (ref "D05") (pin "S2") (pinfunction "P$2_S2") (pintype "bidirectional"))
    )
    (net (code "123") (name "I{slash}~{O_BMB_03}") (class "Default")
      (node (ref "A03") (pin "H1") (pinfunction "P$2_H1") (pintype "bidirectional"))
      (node (ref "D03") (pin "H1") (pinfunction "P$2_H1") (pintype "bidirectional"))
    )
    (net (code "124") (name "I{slash}~{O_BMB_04}") (class "Default")
      (node (ref "A03") (pin "L1") (pinfunction "P$2_L1") (pintype "bidirectional"))
      (node (ref "D03") (pin "L1") (pinfunction "P$2_L1") (pintype "bidirectional"))
    )
    (net (code "125") (name "I{slash}~{O_BMB_05}") (class "Default")
      (node (ref "A03") (pin "P1") (pinfunction "P$2_P1") (pintype "bidirectional"))
      (node (ref "D03") (pin "P1") (pinfunction "P$2_P1") (pintype "bidirectional"))
    )
    (net (code "126") (name "I{slash}~{O_BMB_06}") (class "Default")
      (node (ref "A03") (pin "D2") (pinfunction "P$2_D2") (pintype "bidirectional"))
      (node (ref "D03") (pin "D2") (pinfunction "P$2_D2") (pintype "bidirectional"))
    )
    (net (code "127") (name "I{slash}~{O_BMB_07}") (class "Default")
      (node (ref "A03") (pin "H2") (pinfunction "P$2_H2") (pintype "bidirectional"))
      (node (ref "D03") (pin "H2") (pinfunction "P$2_H2") (pintype "bidirectional"))
    )
    (net (code "128") (name "I{slash}~{O_BMB_08}") (class "Default")
      (node (ref "A03") (pin "M2") (pinfunction "P$2_M2") (pintype "bidirectional"))
      (node (ref "C04") (pin "K2") (pinfunction "K2_K2") (pintype "input"))
      (node (ref "D03") (pin "M2") (pinfunction "P$2_M2") (pintype "bidirectional"))
    )
    (net (code "129") (name "I{slash}~{O_BRK_RQ}") (class "Default")
      (node (ref "A05") (pin "K2") (pinfunction "P$2_K2") (pintype "bidirectional"))
      (node (ref "B05") (pin "D1") (pinfunction "D_D1") (pintype "open_collector"))
      (node (ref "D05") (pin "K2") (pinfunction "P$2_K2") (pintype "bidirectional"))
    )
    (net (code "130") (name "I{slash}~{O_BWC0}") (class "Default")
      (node (ref "A06") (pin "P2") (pinfunction "P$2_P2") (pintype "bidirectional"))
      (node (ref "C01") (pin "F1") (pinfunction "IN_F1") (pintype "input"))
      (node (ref "D06") (pin "P2") (pinfunction "P$2_P2") (pintype "bidirectional"))
    )
    (net (code "131") (name "I{slash}~{O_INT_RQ}") (class "Default")
      (node (ref "A04") (pin "M2") (pinfunction "P$2_M2") (pintype "bidirectional"))
      (node (ref "B05") (pin "E1") (pinfunction "E_E1") (pintype "open_collector"))
      (node (ref "D04") (pin "M2") (pinfunction "P$2_M2") (pintype "bidirectional"))
    )
    (net (code "132") (name "I{slash}~{O_SKP_RQ}") (class "Default")
      (node (ref "A04") (pin "K2") (pinfunction "P$2_K2") (pintype "bidirectional"))
      (node (ref "B05") (pin "K1") (pinfunction "D_K1") (pintype "open_collector"))
      (node (ref "D04") (pin "K2") (pinfunction "P$2_K2") (pintype "bidirectional"))
    )
    (net (code "133") (name "LDMF") (class "Default")
      (node (ref "C05") (pin "E1") (pinfunction "E1_E1") (pintype "output"))
      (node (ref "D11") (pin "B1") (pinfunction "C_B1") (pintype "input"))
      (node (ref "D11") (pin "D2") (pinfunction "C_D2") (pintype "input"))
      (node (ref "D11") (pin "H1") (pinfunction "C_H1") (pintype "input"))
    )
    (net (code "134") (name "LPB_00") (class "Default")
      (node (ref "A25") (pin "T2") (pinfunction "P$2_T2") (pintype "bidirectional"))
      (node (ref "C08") (pin "D1") (pinfunction "IN2B_D1") (pintype "input"))
      (node (ref "D08") (pin "E1") (pinfunction "E1_E1") (pintype "output"))
    )
    (net (code "135") (name "LPB_01") (class "Default")
      (node (ref "A25") (pin "U2") (pinfunction "P$2_U2") (pintype "bidirectional"))
      (node (ref "C08") (pin "K1") (pinfunction "IN2B_K1") (pintype "input"))
      (node (ref "D08") (pin "L1") (pinfunction "L1_L1") (pintype "output"))
    )
    (net (code "136") (name "LPB_02") (class "Default")
      (node (ref "A25") (pin "V2") (pinfunction "P$2_V2") (pintype "bidirectional"))
      (node (ref "C08") (pin "R1") (pinfunction "IN2B_R1") (pintype "input"))
      (node (ref "D08") (pin "S1") (pinfunction "S1_S1") (pintype "output"))
    )
    (net (code "137") (name "LPB_03") (class "Default")
      (node (ref "A26") (pin "A2") (pinfunction "P$2_A2") (pintype "bidirectional"))
      (node (ref "C08") (pin "H2") (pinfunction "IN2B_H2") (pintype "input"))
      (node (ref "D08") (pin "H2") (pinfunction "H2_H2") (pintype "output"))
    )
    (net (code "138") (name "LPB_04") (class "Default")
      (node (ref "A26") (pin "B2") (pinfunction "P$2_B2") (pintype "bidirectional"))
      (node (ref "C08") (pin "N2") (pinfunction "IN2B_N2") (pintype "input"))
      (node (ref "D08") (pin "P2") (pinfunction "P2_P2") (pintype "output"))
    )
    (net (code "139") (name "LPB_05") (class "Default")
      (node (ref "A26") (pin "C2") (pinfunction "P$2_C2") (pintype "bidirectional"))
      (node (ref "C08") (pin "U2") (pinfunction "IN2B_U2") (pintype "input"))
      (node (ref "D08") (pin "V2") (pinfunction "V2_V2") (pintype "output"))
    )
    (net (code "140") (name "LPB_NOT_EQ_1") (class "Default")
      (node (ref "A10") (pin "M1") (pinfunction "IN2_M1") (pintype "input"))
      (node (ref "D10") (pin "V2") (pinfunction "OUT_V2") (pintype "output"))
    )
    (net (code "141") (name "LPB_TO_DTB") (class "Default")
      (node (ref "A11") (pin "T2") (pinfunction "OUT_T2") (pintype "output"))
      (node (ref "C08") (pin "C1") (pinfunction "IN2A_C1") (pintype "input"))
      (node (ref "C08") (pin "F2") (pinfunction "IN2A_F2") (pintype "input"))
      (node (ref "C08") (pin "J1") (pinfunction "IN2A_J1") (pintype "input"))
      (node (ref "C08") (pin "M2") (pinfunction "IN2A_M2") (pintype "input"))
      (node (ref "C08") (pin "P1") (pinfunction "IN2A_P1") (pintype "input"))
      (node (ref "C08") (pin "T2") (pinfunction "IN2A_T2") (pintype "input"))
    )
    (net (code "142") (name "MC00") (class "Default")
      (node (ref "A26") (pin "S1") (pinfunction "P$2_S1") (pintype "bidirectional"))
      (node (ref "B13") (pin "E1") (pinfunction "1_E1") (pintype "output"))
      (node (ref "B13") (pin "E2") (pinfunction "D_E2") (pintype "input"))
      (node (ref "D10") (pin "D2") (pinfunction "IN5_D2") (pintype "input"))
    )
    (net (code "143") (name "MC01") (class "Default")
      (node (ref "A08") (pin "L2") (pinfunction "C_L2") (pintype "input"))
      (node (ref "A26") (pin "T1") (pinfunction "P$2_T1") (pintype "bidirectional"))
      (node (ref "B13") (pin "H2") (pinfunction "1_H2") (pintype "output"))
      (node (ref "B13") (pin "J1") (pinfunction "D_J1") (pintype "input"))
      (node (ref "C11") (pin "E1") (pinfunction "IN2_E1") (pintype "input"))
    )
    (net (code "144") (name "MC02") (class "Default")
      (node (ref "A26") (pin "U1") (pinfunction "P$2_U1") (pintype "bidirectional"))
      (node (ref "B11") (pin "U2") (pinfunction "IN2_U2") (pintype "input"))
      (node (ref "B13") (pin "L1") (pinfunction "1_L1") (pintype "output"))
      (node (ref "D12") (pin "D2") (pinfunction "IN1_D2") (pintype "input"))
      (node (ref "D12") (pin "E2") (pinfunction "IN2_E2") (pintype "input"))
    )
    (net (code "145") (name "MF00") (class "Default")
      (node (ref "A25") (pin "V1") (pinfunction "P$2_V1") (pintype "bidirectional"))
      (node (ref "D11") (pin "E1") (pinfunction "1_E1") (pintype "output"))
    )
    (net (code "146") (name "MF01") (class "Default")
      (node (ref "A26") (pin "A1") (pinfunction "P$2_A1") (pintype "bidirectional"))
      (node (ref "D11") (pin "H2") (pinfunction "1_H2") (pintype "output"))
    )
    (net (code "147") (name "MF02") (class "Default")
      (node (ref "A26") (pin "B1") (pinfunction "P$2_B1") (pintype "bidirectional"))
      (node (ref "D11") (pin "L1") (pinfunction "1_L1") (pintype "output"))
    )
    (net (code "148") (name "MKT") (class "Default")
      (node (ref "A26") (pin "H2") (pinfunction "P$2_H2") (pintype "bidirectional"))
      (node (ref "B12") (pin "S2") (pinfunction "IN2_S2") (pintype "input"))
      (node (ref "B13") (pin "V2") (pinfunction "1_V2") (pintype "output"))
      (node (ref "B15") (pin "L1") (pinfunction "IN1_L1") (pintype "input"))
      (node (ref "C15") (pin "L2") (pinfunction "IN1_L2") (pintype "input"))
    )
    (net (code "149") (name "MKTK") (class "Default")
      (node (ref "A08") (pin "R2") (pinfunction "0_R2") (pintype "output"))
      (node (ref "A25") (pin "P1") (pinfunction "P$2_P1") (pintype "bidirectional"))
    )
    (net (code "150") (name "MK_BLK_END") (class "Default")
      (node (ref "A09") (pin "T2") (pinfunction "IN3_T2") (pintype "input"))
      (node (ref "CD18") (pin "BU1") (pinfunction "BU1_BU1") (pintype "output"))
    )
    (net (code "151") (name "MK_BLK_MK") (class "Default")
      (node (ref "CD18") (pin "AE2") (pinfunction "AE2_AE2") (pintype "output"))
      (node (ref "D10") (pin "A1") (pinfunction "IN1_A1") (pintype "input"))
      (node (ref "D10") (pin "B1") (pinfunction "IN2_B1") (pintype "input"))
    )
    (net (code "152") (name "MK_BLK_START") (class "Default")
      (node (ref "CD18") (pin "AJ2") (pinfunction "AJ2_AJ2") (pintype "output"))
    )
    (net (code "153") (name "MK_BLK_SYNC") (class "Default")
      (node (ref "CD18") (pin "BS2") (pinfunction "BS2_BS2") (pintype "output"))
    )
    (net (code "154") (name "MK_DATA") (class "Default")
      (node (ref "CD18") (pin "BP2") (pinfunction "BP2_BP2") (pintype "output"))
    )
    (net (code "155") (name "MK_DATA_SYNC") (class "Default")
      (node (ref "CD18") (pin "AH1") (pinfunction "AH1_AH1") (pintype "output"))
    )
    (net (code "156") (name "MK_END") (class "Default")
      (node (ref "A08") (pin "C1") (pinfunction "D_C1") (pintype "input"))
      (node (ref "CD18") (pin "AF2") (pinfunction "AF2_AF2") (pintype "output"))
    )
    (net (code "157") (name "MOVE") (class "Default")
      (node (ref "D07") (pin "D2") (pinfunction "O0_D2") (pintype "output"))
    )
    (net (code "158") (name "MR00") (class "Default")
      (node (ref "A25") (pin "D1") (pinfunction "P$2_D1") (pintype "bidirectional"))
      (node (ref "B07") (pin "P2") (pinfunction "P2_P2") (pintype "output"))
      (node (ref "B14") (pin "M2") (pinfunction "D_M2") (pintype "input"))
    )
    (net (code "159") (name "MR01") (class "Default")
      (node (ref "A25") (pin "E1") (pinfunction "P$2_E1") (pintype "bidirectional"))
      (node (ref "C07") (pin "P2") (pinfunction "P2_P2") (pintype "output"))
      (node (ref "C12") (pin "B1") (pinfunction "IN2_B1") (pintype "input"))
    )
    (net (code "160") (name "Net-(A08D-D)") (class "Default")
      (node (ref "A08") (pin "E2") (pinfunction "D_E2") (pintype "input"))
      (node (ref "A09") (pin "L1") (pinfunction "OUT_L1") (pintype "output"))
    )
    (net (code "161") (name "Net-(A08E-S)") (class "Default")
      (node (ref "A08") (pin "K1") (pinfunction "S_K1") (pintype "input"))
      (node (ref "A11") (pin "E1") (pinfunction "OUT_E1") (pintype "output"))
    )
    (net (code "162") (name "Net-(A08F-D)") (class "Default")
      (node (ref "A08") (pin "M2") (pinfunction "D_M2") (pintype "input"))
      (node (ref "A09") (pin "J2") (pinfunction "OUT_J2") (pintype "output"))
    )
    (net (code "163") (name "Net-(A08G-C)") (class "Default")
      (node (ref "A08") (pin "N1") (pinfunction "C_N1") (pintype "input"))
      (node (ref "A11") (pin "D2") (pinfunction "OUT_D2") (pintype "output"))
    )
    (net (code "164") (name "Net-(A08G-D)") (class "Default")
      (node (ref "A08") (pin "P1") (pinfunction "D_P1") (pintype "input"))
      (node (ref "A10") (pin "N1") (pinfunction "OUT_N1") (pintype "output"))
    )
    (net (code "165") (name "Net-(A08H-S)") (class "Default")
      (node (ref "A08") (pin "U2") (pinfunction "S_U2") (pintype "input"))
      (node (ref "B10") (pin "S1") (pinfunction "OUT_S1") (pintype "output"))
    )
    (net (code "166") (name "Net-(A09A-OUT)") (class "Default")
      (node (ref "A09") (pin "E1") (pinfunction "OUT_E1") (pintype "output"))
      (node (ref "A11") (pin "A1") (pinfunction "IN_A1") (pintype "input"))
    )
    (net (code "167") (name "Net-(A09D-IN4)") (class "Default")
      (node (ref "A09") (pin "H2") (pinfunction "IN4_H2") (pintype "input"))
      (node (ref "A11") (pin "B1") (pinfunction "OUT_B1") (pintype "output"))
    )
    (net (code "168") (name "Net-(A09E-IN1)") (class "Default")
      (node (ref "A09") (pin "F1") (pinfunction "IN1_F1") (pintype "input"))
      (node (ref "C10") (pin "P2") (pinfunction "OUT_P2") (pintype "output"))
    )
    (net (code "169") (name "Net-(A09E-IN3)") (class "Default")
      (node (ref "A09") (pin "J1") (pinfunction "IN3_J1") (pintype "input"))
      (node (ref "A10") (pin "K1") (pinfunction "OUT_K1") (pintype "output"))
    )
    (net (code "170") (name "Net-(A09F-OUT)") (class "Default")
      (node (ref "A09") (pin "P2") (pinfunction "OUT_P2") (pintype "output"))
      (node (ref "A11") (pin "F1") (pinfunction "IN_F1") (pintype "input"))
    )
    (net (code "171") (name "Net-(A09G-OUT)") (class "Default")
      (node (ref "A09") (pin "S1") (pinfunction "OUT_S1") (pintype "output"))
      (node (ref "A10") (pin "U2") (pinfunction "IN2_U2") (pintype "input"))
    )
    (net (code "172") (name "Net-(A09J-IN4)") (class "Default")
      (node (ref "A09") (pin "U2") (pinfunction "IN4_U2") (pintype "input"))
      (node (ref "C17") (pin "R2") (pinfunction "OUT_R2") (pintype "output"))
    )
    (net (code "173") (name "Net-(A09J-OUT)") (class "Default")
      (node (ref "A09") (pin "V2") (pinfunction "OUT_V2") (pintype "output"))
      (node (ref "A11") (pin "S2") (pinfunction "IN_S2") (pintype "input"))
    )
    (net (code "174") (name "Net-(A10A-IN2)") (class "Default")
      (node (ref "A10") (pin "B1") (pinfunction "IN2_B1") (pintype "input"))
      (node (ref "A10") (pin "F1") (pinfunction "OUT_F1") (pintype "output"))
      (node (ref "B15") (pin "P2") (pinfunction "IN1_P2") (pintype "input"))
    )
    (net (code "175") (name "Net-(A10A-OUT)") (class "Default")
      (node (ref "A10") (pin "C1") (pinfunction "OUT_C1") (pintype "output"))
      (node (ref "A10") (pin "D1") (pinfunction "IN1_D1") (pintype "input"))
    )
    (net (code "176") (name "Net-(A10C-OUT)") (class "Default")
      (node (ref "A10") (pin "F2") (pinfunction "OUT_F2") (pintype "output"))
      (node (ref "A10") (pin "J2") (pinfunction "IN2_J2") (pintype "input"))
    )
    (net (code "177") (name "Net-(A10J-OUT)") (class "Default")
      (node (ref "A10") (pin "S1") (pinfunction "OUT_S1") (pintype "output"))
      (node (ref "A11") (pin "C1") (pinfunction "IN_C1") (pintype "input"))
    )
    (net (code "178") (name "Net-(A10K-OUT)") (class "Default")
      (node (ref "A10") (pin "S2") (pinfunction "OUT_S2") (pintype "output"))
      (node (ref "A10") (pin "T2") (pinfunction "IN1_T2") (pintype "input"))
    )
    (net (code "179") (name "Net-(A10N-OUT)") (class "Default")
      (node (ref "A10") (pin "V2") (pinfunction "OUT_V2") (pintype "output"))
      (node (ref "A11") (pin "D1") (pinfunction "IN_D1") (pintype "input"))
    )
    (net (code "180") (name "Net-(A11G-OUT)") (class "Default")
      (node (ref "A11") (pin "H1") (pinfunction "OUT_H1") (pintype "output"))
      (node (ref "A12") (pin "B1") (pinfunction "IN2_B1") (pintype "input"))
      (node (ref "A12") (pin "D1") (pinfunction "IN1_D1") (pintype "input"))
    )
    (net (code "181") (name "Net-(A11N-IN)") (class "Default")
      (node (ref "A11") (pin "P2") (pinfunction "IN_P2") (pintype "input"))
      (node (ref "A14") (pin "F2") (pinfunction "F2_F2") (pintype "output"))
    )
    (net (code "182") (name "Net-(A11O-IN)") (class "Default")
      (node (ref "A11") (pin "R1") (pinfunction "IN_R1") (pintype "input"))
      (node (ref "B11") (pin "S2") (pinfunction "OUT_S2") (pintype "output"))
    )
    (net (code "183") (name "Net-(A11Q-IN)") (class "Default")
      (node (ref "A11") (pin "V1") (pinfunction "IN_V1") (pintype "input"))
      (node (ref "B08") (pin "V2") (pinfunction "OUT_V2") (pintype "output"))
    )
    (net (code "184") (name "Net-(A11R-IN)") (class "Default")
      (node (ref "A11") (pin "U2") (pinfunction "IN_U2") (pintype "input"))
      (node (ref "A14") (pin "T2") (pinfunction "F2_T2") (pintype "output"))
    )
    (net (code "185") (name "Net-(A12C-OUT)") (class "Default")
      (node (ref "A12") (pin "F2") (pinfunction "OUT_F2") (pintype "output"))
      (node (ref "B10") (pin "A1") (pinfunction "IN1_A1") (pintype "input"))
      (node (ref "B10") (pin "B1") (pinfunction "IN2_B1") (pintype "input"))
    )
    (net (code "186") (name "Net-(A12F-IN2)") (class "Default")
      (node (ref "A12") (pin "J1") (pinfunction "IN2_J1") (pintype "input"))
      (node (ref "A12") (pin "N1") (pinfunction "OUT_N1") (pintype "output"))
      (node (ref "A12") (pin "P1") (pinfunction "IN1_P1") (pintype "input"))
    )
    (net (code "187") (name "Net-(A12G-OUT)") (class "Default")
      (node (ref "A12") (pin "K2") (pinfunction "OUT_K2") (pintype "output"))
      (node (ref "B10") (pin "C1") (pinfunction "IN3_C1") (pintype "input"))
      (node (ref "B10") (pin "D1") (pinfunction "IN4_D1") (pintype "input"))
    )
    (net (code "188") (name "Net-(A12I-OUT)") (class "Default")
      (node (ref "A12") (pin "N2") (pinfunction "OUT_N2") (pintype "output"))
      (node (ref "A12") (pin "T2") (pinfunction "IN1_T2") (pintype "input"))
    )
    (net (code "189") (name "Net-(A12K-OUT)") (class "Default")
      (node (ref "A12") (pin "S2") (pinfunction "OUT_S2") (pintype "output"))
      (node (ref "A12") (pin "U2") (pinfunction "IN2_U2") (pintype "input"))
    )
    (net (code "190") (name "Net-(A14-PadD2)") (class "Default")
      (node (ref "A14") (pin "D2") (pinfunction "D2_D2") (pintype "passive"))
      (node (ref "A14") (pin "E2") (pinfunction "E2_E2") (pintype "passive"))
    )
    (net (code "191") (name "Net-(A14-PadH1)") (class "Default")
      (node (ref "A14") (pin "H1") (pinfunction "H1_H1") (pintype "passive"))
      (node (ref "A14") (pin "L2") (pinfunction "L2_L2") (pintype "passive"))
    )
    (net (code "192") (name "Net-(A14D-D2)") (class "Default")
      (node (ref "A14") (pin "R2") (pinfunction "E2_R2") (pintype "passive"))
      (node (ref "A14") (pin "V2") (pinfunction "D2_V2") (pintype "passive"))
    )
    (net (code "193") (name "Net-(A14D-H1)") (class "Default")
      (node (ref "A14") (pin "S1") (pinfunction "H1_S1") (pintype "passive"))
      (node (ref "A14") (pin "S2") (pinfunction "L2_S2") (pintype "passive"))
    )
    (net (code "194") (name "Net-(A14D-H2)") (class "Default")
      (node (ref "A14") (pin "M2") (pinfunction "H2_M2") (pintype "input"))
      (node (ref "A14") (pin "N2") (pinfunction "J2_N2") (pintype "input"))
      (node (ref "A14") (pin "P2") (pinfunction "K2_P2") (pintype "input"))
      (node (ref "B15") (pin "F2") (pinfunction "OUT_F2") (pintype "output"))
    )
    (net (code "195") (name "Net-(A15A-IN3)") (class "Default")
      (node (ref "A15") (pin "C1") (pinfunction "IN3_C1") (pintype "input"))
      (node (ref "A15") (pin "D1") (pinfunction "IN4_D1") (pintype "input"))
      (node (ref "C17") (pin "D2") (pinfunction "OUT_D2") (pintype "output"))
    )
    (net (code "196") (name "Net-(A15D-IN1)") (class "Default")
      (node (ref "A15") (pin "D2") (pinfunction "IN1_D2") (pintype "input"))
      (node (ref "A15") (pin "E2") (pinfunction "IN2_E2") (pintype "input"))
      (node (ref "C17") (pin "F2") (pinfunction "OUT_F2") (pintype "output"))
    )
    (net (code "197") (name "Net-(A16-PadD2)") (class "Default")
      (node (ref "A16") (pin "D2") (pinfunction "D2_D2") (pintype "passive"))
      (node (ref "A16") (pin "E2") (pinfunction "E2_E2") (pintype "passive"))
    )
    (net (code "198") (name "Net-(A16C-D2)") (class "Default")
      (node (ref "A16") (pin "R2") (pinfunction "E2_R2") (pintype "passive"))
      (node (ref "A16") (pin "S2") (pinfunction "D2_S2") (pintype "passive"))
    )
    (net (code "199") (name "Net-(AB19A-P$2)") (class "Default")
      (node (ref "A18") (pin "D2") (pinfunction "D2_D2") (pintype "input"))
      (node (ref "A18") (pin "J2") (pinfunction "J2_J2") (pintype "output"))
      (node (ref "AB19") (pin "AF2") (pinfunction "P$2_AF2") (pintype "bidirectional"))
    )
    (net (code "200") (name "Net-(AB19B-P$2)") (class "Default")
      (node (ref "A18") (pin "E2") (pinfunction "E2_E2") (pintype "input"))
      (node (ref "A18") (pin "K2") (pinfunction "K2_K2") (pintype "output"))
      (node (ref "AB19") (pin "AH2") (pinfunction "P$2_AH2") (pintype "bidirectional"))
    )
    (net (code "201") (name "Net-(AB19D-P$2)") (class "Default")
      (node (ref "AB19") (pin "AN2") (pinfunction "P$2_AN2") (pintype "bidirectional"))
      (node (ref "B18") (pin "D2") (pinfunction "D2_D2") (pintype "input"))
      (node (ref "B18") (pin "J2") (pinfunction "J2_J2") (pintype "output"))
    )
    (net (code "202") (name "Net-(AB19E-P$2)") (class "Default")
      (node (ref "AB19") (pin "AP2") (pinfunction "P$2_AP2") (pintype "bidirectional"))
      (node (ref "B18") (pin "E2") (pinfunction "E2_E2") (pintype "input"))
      (node (ref "B18") (pin "K2") (pinfunction "K2_K2") (pintype "output"))
    )
    (net (code "203") (name "Net-(AB19H-P$2)") (class "Default")
      (node (ref "A20") (pin "D2") (pinfunction "D2_D2") (pintype "input"))
      (node (ref "A20") (pin "J2") (pinfunction "J2_J2") (pintype "output"))
      (node (ref "AB19") (pin "AV2") (pinfunction "P$2_AV2") (pintype "bidirectional"))
    )
    (net (code "204") (name "Net-(AB19I-P$2)") (class "Default")
      (node (ref "A20") (pin "E2") (pinfunction "E2_E2") (pintype "input"))
      (node (ref "A20") (pin "K2") (pinfunction "K2_K2") (pintype "output"))
      (node (ref "AB19") (pin "BD2") (pinfunction "P$2_BD2") (pintype "bidirectional"))
    )
    (net (code "205") (name "Net-(AB19K-P$2)") (class "Default")
      (node (ref "AB19") (pin "BH2") (pinfunction "P$2_BH2") (pintype "bidirectional"))
      (node (ref "B20") (pin "D2") (pinfunction "D2_D2") (pintype "input"))
      (node (ref "B20") (pin "J2") (pinfunction "J2_J2") (pintype "output"))
    )
    (net (code "206") (name "Net-(AB19L-P$2)") (class "Default")
      (node (ref "AB19") (pin "BJ2") (pinfunction "P$2_BJ2") (pintype "bidirectional"))
      (node (ref "B20") (pin "E2") (pinfunction "E2_E2") (pintype "input"))
      (node (ref "B20") (pin "K2") (pinfunction "K2_K2") (pintype "output"))
    )
    (net (code "207") (name "Net-(AB19N-P$2)") (class "Default")
      (node (ref "A21") (pin "D2") (pinfunction "D2_D2") (pintype "input"))
      (node (ref "A21") (pin "J2") (pinfunction "J2_J2") (pintype "output"))
      (node (ref "AB19") (pin "BN2") (pinfunction "P$2_BN2") (pintype "bidirectional"))
    )
    (net (code "208") (name "Net-(AB19O-P$2)") (class "Default")
      (node (ref "A21") (pin "E2") (pinfunction "E2_E2") (pintype "input"))
      (node (ref "A21") (pin "K2") (pinfunction "K2_K2") (pintype "output"))
      (node (ref "AB19") (pin "BP2") (pinfunction "P$2_BP2") (pintype "bidirectional"))
    )
    (net (code "209") (name "Net-(B06P-IN)") (class "Default")
      (node (ref "B06") (pin "S2") (pinfunction "IN_S2") (pintype "input"))
      (node (ref "B08") (pin "S2") (pinfunction "OUT_S2") (pintype "output"))
    )
    (net (code "210") (name "Net-(B08A-OUT)") (class "Default")
      (node (ref "B08") (pin "C1") (pinfunction "OUT_C1") (pintype "output"))
      (node (ref "B09") (pin "D1") (pinfunction "S_D1") (pintype "input"))
    )
    (net (code "211") (name "Net-(B08B-OUT)") (class "Default")
      (node (ref "B08") (pin "F1") (pinfunction "OUT_F1") (pintype "output"))
      (node (ref "B09") (pin "U2") (pinfunction "S_U2") (pintype "input"))
    )
    (net (code "212") (name "Net-(B08C-OUT)") (class "Default")
      (node (ref "B08") (pin "F2") (pinfunction "OUT_F2") (pintype "output"))
      (node (ref "B09") (pin "K1") (pinfunction "S_K1") (pintype "input"))
    )
    (net (code "213") (name "Net-(B08F-OUT)") (class "Default")
      (node (ref "B08") (pin "K1") (pinfunction "OUT_K1") (pintype "output"))
      (node (ref "B09") (pin "F2") (pinfunction "S_F2") (pintype "input"))
    )
    (net (code "214") (name "Net-(B08H-OUT)") (class "Default")
      (node (ref "B08") (pin "N1") (pinfunction "OUT_N1") (pintype "output"))
      (node (ref "B09") (pin "N2") (pinfunction "S_N2") (pintype "input"))
    )
    (net (code "215") (name "Net-(B08J-OUT)") (class "Default")
      (node (ref "B08") (pin "S1") (pinfunction "OUT_S1") (pintype "output"))
      (node (ref "B09") (pin "R1") (pinfunction "S_R1") (pintype "input"))
    )
    (net (code "216") (name "Net-(B10E-IN1)") (class "Default")
      (node (ref "B10") (pin "F1") (pinfunction "IN1_F1") (pintype "input"))
      (node (ref "B11") (pin "J1") (pinfunction "OUT_J1") (pintype "output"))
    )
    (net (code "217") (name "Net-(B10E-IN4)") (class "Default")
      (node (ref "B10") (pin "K1") (pinfunction "IN4_K1") (pintype "input"))
      (node (ref "C17") (pin "H1") (pinfunction "OUT_H1") (pintype "output"))
    )
    (net (code "218") (name "Net-(B11A-OUT)") (class "Default")
      (node (ref "B11") (pin "D1") (pinfunction "OUT_D1") (pintype "output"))
      (node (ref "B11") (pin "F2") (pinfunction "IN3_F2") (pintype "input"))
    )
    (net (code "219") (name "Net-(B11D-IN1)") (class "Default")
      (node (ref "B11") (pin "D2") (pinfunction "IN1_D2") (pintype "input"))
      (node (ref "B12") (pin "E1") (pinfunction "OUT_E1") (pintype "output"))
    )
    (net (code "220") (name "Net-(B11D-IN2)") (class "Default")
      (node (ref "B11") (pin "E2") (pinfunction "IN2_E2") (pintype "input"))
      (node (ref "B12") (pin "L1") (pinfunction "OUT_L1") (pintype "output"))
    )
    (net (code "221") (name "Net-(B11D-OUT)") (class "Default")
      (node (ref "B11") (pin "H2") (pinfunction "OUT_H2") (pintype "output"))
      (node (ref "C13") (pin "C1") (pinfunction "IN_C1") (pintype "input"))
    )
    (net (code "222") (name "Net-(B11E-IN1)") (class "Default")
      (node (ref "B11") (pin "E1") (pinfunction "IN1_E1") (pintype "input"))
      (node (ref "B11") (pin "U1") (pinfunction "OUT_U1") (pintype "output"))
    )
    (net (code "223") (name "Net-(B11E-IN3)") (class "Default")
      (node (ref "B11") (pin "H1") (pinfunction "IN3_H1") (pintype "input"))
      (node (ref "B11") (pin "N1") (pinfunction "OUT_N1") (pintype "output"))
    )
    (net (code "224") (name "Net-(B11F-IN3)") (class "Default")
      (node (ref "B11") (pin "L2") (pinfunction "IN3_L2") (pintype "input"))
      (node (ref "B15") (pin "S2") (pinfunction "OUT_S2") (pintype "output"))
    )
    (net (code "225") (name "Net-(B11J-OUT)") (class "Default")
      (node (ref "B11") (pin "V1") (pinfunction "OUT_V1") (pintype "output"))
      (node (ref "C17") (pin "J1") (pinfunction "IN_J1") (pintype "input"))
    )
    (net (code "226") (name "Net-(B12D-OUT)") (class "Default")
      (node (ref "B12") (pin "J2") (pinfunction "OUT_J2") (pintype "output"))
      (node (ref "B12") (pin "N2") (pinfunction "IN4_N2") (pintype "input"))
    )
    (net (code "227") (name "Net-(B12F-IN1)") (class "Default")
      (node (ref "B12") (pin "K2") (pinfunction "IN1_K2") (pintype "input"))
      (node (ref "C12") (pin "N1") (pinfunction "OUT_N1") (pintype "output"))
    )
    (net (code "228") (name "Net-(B12F-IN2)") (class "Default")
      (node (ref "B12") (pin "L2") (pinfunction "IN2_L2") (pintype "input"))
      (node (ref "C12") (pin "U1") (pinfunction "OUT_U1") (pintype "output"))
    )
    (net (code "229") (name "Net-(B12F-IN3)") (class "Default")
      (node (ref "B12") (pin "M2") (pinfunction "IN3_M2") (pintype "input"))
      (node (ref "C12") (pin "V1") (pinfunction "OUT_V1") (pintype "output"))
    )
    (net (code "230") (name "Net-(B12G-IN1)") (class "Default")
      (node (ref "B12") (pin "M1") (pinfunction "IN1_M1") (pintype "input"))
      (node (ref "C11") (pin "C1") (pinfunction "OUT_C1") (pintype "output"))
    )
    (net (code "231") (name "Net-(B12G-IN4)") (class "Default")
      (node (ref "B12") (pin "R1") (pinfunction "IN4_R1") (pintype "input"))
      (node (ref "C11") (pin "F1") (pinfunction "OUT_F1") (pintype "output"))
    )
    (net (code "232") (name "Net-(B12G-OUT)") (class "Default")
      (node (ref "B12") (pin "S1") (pinfunction "OUT_S1") (pintype "output"))
      (node (ref "C11") (pin "P1") (pinfunction "IN1_P1") (pintype "input"))
    )
    (net (code "233") (name "Net-(B12J-IN4)") (class "Default")
      (node (ref "B12") (pin "U2") (pinfunction "IN4_U2") (pintype "input"))
      (node (ref "C11") (pin "N1") (pinfunction "OUT_N1") (pintype "output"))
    )
    (net (code "234") (name "Net-(B12J-OUT)") (class "Default")
      (node (ref "B12") (pin "V2") (pinfunction "OUT_V2") (pintype "output"))
      (node (ref "C12") (pin "F1") (pinfunction "IN2_F1") (pintype "input"))
    )
    (net (code "235") (name "Net-(B13F-S)") (class "Default")
      (node (ref "B13") (pin "N2") (pinfunction "S_N2") (pintype "input"))
      (node (ref "B15") (pin "K1") (pinfunction "OUT_K1") (pintype "output"))
    )
    (net (code "236") (name "Net-(B14G-C)") (class "Default")
      (node (ref "B14") (pin "N1") (pinfunction "C_N1") (pintype "input"))
      (node (ref "B14") (pin "S2") (pinfunction "C_S2") (pintype "input"))
      (node (ref "D15") (pin "D2") (pinfunction "D2_D2") (pintype "output"))
    )
    (net (code "237") (name "Net-(B15B-OUT)") (class "Default")
      (node (ref "A14") (pin "H2") (pinfunction "H2_H2") (pintype "input"))
      (node (ref "A14") (pin "J2") (pinfunction "J2_J2") (pintype "input"))
      (node (ref "A14") (pin "K2") (pinfunction "K2_K2") (pintype "input"))
      (node (ref "B15") (pin "F1") (pinfunction "OUT_F1") (pintype "output"))
    )
    (net (code "238") (name "Net-(B15H-OUT)") (class "Default")
      (node (ref "B15") (pin "N1") (pinfunction "OUT_N1") (pintype "output"))
      (node (ref "C17") (pin "F1") (pinfunction "IN_F1") (pintype "input"))
    )
    (net (code "239") (name "Net-(B15J-OUT)") (class "Default")
      (node (ref "B15") (pin "S1") (pinfunction "OUT_S1") (pintype "output"))
      (node (ref "C17") (pin "L1") (pinfunction "IN_L1") (pintype "input"))
    )
    (net (code "240") (name "Net-(B16-PadD2)") (class "Default")
      (node (ref "B16") (pin "D2") (pinfunction "D2_D2") (pintype "passive"))
      (node (ref "B16") (pin "E2") (pinfunction "E2_E2") (pintype "passive"))
    )
    (net (code "241") (name "Net-(B16C-D2)") (class "Default")
      (node (ref "B16") (pin "R2") (pinfunction "E2_R2") (pintype "passive"))
      (node (ref "B16") (pin "S2") (pinfunction "D2_S2") (pintype "passive"))
    )
    (net (code "242") (name "Net-(C08A-OUT)") (class "Default")
      (node (ref "C08") (pin "E1") (pinfunction "OUT_E1") (pintype "output"))
      (node (ref "C09") (pin "D1") (pinfunction "S_D1") (pintype "input"))
    )
    (net (code "243") (name "Net-(C08D-OUT)") (class "Default")
      (node (ref "C08") (pin "J2") (pinfunction "OUT_J2") (pintype "output"))
      (node (ref "C09") (pin "N2") (pinfunction "S_N2") (pintype "input"))
    )
    (net (code "244") (name "Net-(C08E-OUT)") (class "Default")
      (node (ref "C08") (pin "L1") (pinfunction "OUT_L1") (pintype "output"))
      (node (ref "C09") (pin "F2") (pinfunction "S_F2") (pintype "input"))
    )
    (net (code "245") (name "Net-(C08F-OUT)") (class "Default")
      (node (ref "C08") (pin "P2") (pinfunction "OUT_P2") (pintype "output"))
      (node (ref "C09") (pin "R1") (pinfunction "S_R1") (pintype "input"))
    )
    (net (code "246") (name "Net-(C08G-OUT)") (class "Default")
      (node (ref "C08") (pin "S1") (pinfunction "OUT_S1") (pintype "output"))
      (node (ref "C09") (pin "K1") (pinfunction "S_K1") (pintype "input"))
    )
    (net (code "247") (name "Net-(C08J-OUT)") (class "Default")
      (node (ref "C08") (pin "V2") (pinfunction "OUT_V2") (pintype "output"))
      (node (ref "C09") (pin "U2") (pinfunction "S_U2") (pintype "input"))
    )
    (net (code "248") (name "Net-(C10A-OUT)") (class "Default")
      (node (ref "C10") (pin "E1") (pinfunction "OUT_E1") (pintype "output"))
      (node (ref "C14") (pin "C1") (pinfunction "D_C1") (pintype "input"))
    )
    (net (code "249") (name "Net-(C10D-OUT)") (class "Default")
      (node (ref "C10") (pin "J2") (pinfunction "OUT_J2") (pintype "output"))
      (node (ref "C17") (pin "M2") (pinfunction "IN_M2") (pintype "input"))
    )
    (net (code "250") (name "Net-(C10E-OUT)") (class "Default")
      (node (ref "C10") (pin "L1") (pinfunction "OUT_L1") (pintype "output"))
      (node (ref "C14") (pin "E2") (pinfunction "D_E2") (pintype "input"))
    )
    (net (code "251") (name "Net-(C10G-OUT)") (class "Default")
      (node (ref "C10") (pin "S1") (pinfunction "OUT_S1") (pintype "output"))
      (node (ref "C14") (pin "J1") (pinfunction "D_J1") (pintype "input"))
    )
    (net (code "252") (name "Net-(C10J-OUT)") (class "Default")
      (node (ref "C10") (pin "V2") (pinfunction "OUT_V2") (pintype "output"))
      (node (ref "C17") (pin "V1") (pinfunction "IN_V1") (pintype "input"))
    )
    (net (code "253") (name "Net-(C11C-OUT)") (class "Default")
      (node (ref "C11") (pin "F2") (pinfunction "OUT_F2") (pintype "output"))
      (node (ref "C12") (pin "H1") (pinfunction "IN3_H1") (pintype "input"))
    )
    (net (code "254") (name "Net-(C11F-OUT)") (class "Default")
      (node (ref "C11") (pin "K1") (pinfunction "OUT_K1") (pintype "output"))
      (node (ref "C11") (pin "L1") (pinfunction "IN1_L1") (pintype "input"))
    )
    (net (code "255") (name "Net-(C11G-OUT)") (class "Default")
      (node (ref "C11") (pin "K2") (pinfunction "OUT_K2") (pintype "output"))
      (node (ref "D12") (pin "K2") (pinfunction "IN1_K2") (pintype "input"))
      (node (ref "D12") (pin "L2") (pinfunction "IN2_L2") (pintype "input"))
    )
    (net (code "256") (name "Net-(C11J-OUT)") (class "Default")
      (node (ref "C11") (pin "S1") (pinfunction "OUT_S1") (pintype "output"))
      (node (ref "C12") (pin "E1") (pinfunction "IN1_E1") (pintype "input"))
    )
    (net (code "257") (name "Net-(C11K-OUT)") (class "Default")
      (node (ref "C11") (pin "S2") (pinfunction "OUT_S2") (pintype "output"))
      (node (ref "C11") (pin "T2") (pinfunction "IN1_T2") (pintype "input"))
    )
    (net (code "258") (name "Net-(C11N-OUT)") (class "Default")
      (node (ref "C11") (pin "V2") (pinfunction "OUT_V2") (pintype "output"))
      (node (ref "C13") (pin "V1") (pinfunction "IN_V1") (pintype "input"))
    )
    (net (code "259") (name "Net-(C12A-OUT)") (class "Default")
      (node (ref "C12") (pin "D1") (pinfunction "OUT_D1") (pintype "output"))
      (node (ref "C13") (pin "M2") (pinfunction "IN_M2") (pintype "input"))
    )
    (net (code "260") (name "Net-(C12D-OUT)") (class "Default")
      (node (ref "C12") (pin "H2") (pinfunction "OUT_H2") (pintype "output"))
      (node (ref "D12") (pin "M2") (pinfunction "IN3_M2") (pintype "input"))
      (node (ref "D12") (pin "N2") (pinfunction "IN4_N2") (pintype "input"))
    )
    (net (code "261") (name "Net-(C12H-OUT)") (class "Default")
      (node (ref "C12") (pin "S2") (pinfunction "OUT_S2") (pintype "output"))
      (node (ref "C15") (pin "P1") (pinfunction "IN1_P1") (pintype "input"))
    )
    (net (code "262") (name "Net-(C13B-OUT)") (class "Default")
      (node (ref "C13") (pin "D2") (pinfunction "OUT_D2") (pintype "output"))
      (node (ref "C14") (pin "P1") (pinfunction "D_P1") (pintype "input"))
    )
    (net (code "263") (name "Net-(C13L-OUT)") (class "Default")
      (node (ref "C13") (pin "N2") (pinfunction "OUT_N2") (pintype "output"))
      (node (ref "C14") (pin "N2") (pinfunction "S_N2") (pintype "input"))
    )
    (net (code "264") (name "Net-(C13N-IN)") (class "Default")
      (node (ref "C13") (pin "P2") (pinfunction "IN_P2") (pintype "input"))
      (node (ref "C15") (pin "F2") (pinfunction "OUT_F2") (pintype "output"))
    )
    (net (code "265") (name "Net-(C13P-IN)") (class "Default")
      (node (ref "C13") (pin "S2") (pinfunction "IN_S2") (pintype "input"))
      (node (ref "C15") (pin "K2") (pinfunction "OUT_K2") (pintype "output"))
    )
    (net (code "266") (name "Net-(C14F-C)") (class "Default")
      (node (ref "C14") (pin "L2") (pinfunction "C_L2") (pintype "input"))
      (node (ref "C15") (pin "S2") (pinfunction "OUT_S2") (pintype "output"))
    )
    (net (code "267") (name "Net-(C15A-OUT)") (class "Default")
      (node (ref "C15") (pin "C1") (pinfunction "OUT_C1") (pintype "output"))
      (node (ref "C15") (pin "H1") (pinfunction "IN1_H1") (pintype "input"))
    )
    (net (code "268") (name "Net-(C15B-OUT)") (class "Default")
      (node (ref "C15") (pin "F1") (pinfunction "OUT_F1") (pintype "output"))
      (node (ref "C15") (pin "J1") (pinfunction "IN2_J1") (pintype "input"))
    )
    (net (code "269") (name "Net-(C15H-OUT)") (class "Default")
      (node (ref "C15") (pin "N1") (pinfunction "OUT_N1") (pintype "output"))
      (node (ref "C15") (pin "R1") (pinfunction "IN2_R1") (pintype "input"))
    )
    (net (code "270") (name "Net-(C15I-OUT)") (class "Default")
      (node (ref "C15") (pin "N2") (pinfunction "OUT_N2") (pintype "output"))
      (node (ref "C17") (pin "P2") (pinfunction "IN_P2") (pintype "input"))
    )
    (net (code "271") (name "Net-(C16F-IN1)") (class "Default")
      (node (ref "C16") (pin "K2") (pinfunction "IN1_K2") (pintype "input"))
      (node (ref "C16") (pin "L2") (pinfunction "IN2_L2") (pintype "input"))
      (node (ref "C16") (pin "M2") (pinfunction "IN3_M2") (pintype "input"))
      (node (ref "C16") (pin "N2") (pinfunction "IN4_N2") (pintype "input"))
      (node (ref "C17") (pin "B1") (pinfunction "OUT_B1") (pintype "output"))
    )
    (net (code "272") (name "Net-(C16G-OUT)") (class "Default")
      (node (ref "B16") (pin "K2") (pinfunction "K2_K2") (pintype "input"))
      (node (ref "C16") (pin "S1") (pinfunction "OUT_S1") (pintype "output"))
    )
    (net (code "273") (name "Net-(C16J-OUT)") (class "Default")
      (node (ref "A16") (pin "H2") (pinfunction "H2_H2") (pintype "input"))
      (node (ref "C16") (pin "V2") (pinfunction "OUT_V2") (pintype "output"))
    )
    (net (code "274") (name "Net-(C17B-IN)") (class "Default")
      (node (ref "A16") (pin "F2") (pinfunction "F2_F2") (pintype "output"))
      (node (ref "C17") (pin "C1") (pinfunction "IN_C1") (pintype "input"))
    )
    (net (code "275") (name "Net-(C17D-IN)") (class "Default")
      (node (ref "B16") (pin "F2") (pinfunction "F2_F2") (pintype "output"))
      (node (ref "C17") (pin "E2") (pinfunction "IN_E2") (pintype "input"))
    )
    (net (code "276") (name "Net-(C17L-OUT)") (class "Default")
      (node (ref "C17") (pin "N2") (pinfunction "OUT_N2") (pintype "output"))
      (node (ref "D08") (pin "B1") (pinfunction "B1_B1") (pintype "input"))
      (node (ref "D08") (pin "H1") (pinfunction "H1_H1") (pintype "input"))
      (node (ref "D08") (pin "N1") (pinfunction "N1_N1") (pintype "input"))
    )
    (net (code "277") (name "Net-(C17O-IN)") (class "Default")
      (node (ref "C17") (pin "R1") (pinfunction "IN_R1") (pintype "input"))
      (node (ref "D17") (pin "F2") (pinfunction "F2_F2") (pintype "output"))
    )
    (net (code "278") (name "Net-(C17P-IN)") (class "Default")
      (node (ref "C17") (pin "S2") (pinfunction "IN_S2") (pintype "input"))
      (node (ref "D16") (pin "T2") (pinfunction "F2_T2") (pintype "output"))
    )
    (net (code "279") (name "Net-(C17Q-OUT)") (class "Default")
      (node (ref "C17") (pin "U1") (pinfunction "OUT_U1") (pintype "output"))
      (node (ref "D08") (pin "D2") (pinfunction "D2_D2") (pintype "input"))
      (node (ref "D08") (pin "L2") (pinfunction "L2_L2") (pintype "input"))
      (node (ref "D08") (pin "S2") (pinfunction "S2_S2") (pintype "input"))
    )
    (net (code "280") (name "Net-(D09A-OUT)") (class "Default")
      (node (ref "D08") (pin "C1") (pinfunction "C1_C1") (pintype "input"))
      (node (ref "D08") (pin "D1") (pinfunction "D1_D1") (pintype "input"))
      (node (ref "D09") (pin "E1") (pinfunction "OUT_E1") (pintype "output"))
    )
    (net (code "281") (name "Net-(D09D-OUT)") (class "Default")
      (node (ref "D08") (pin "E2") (pinfunction "E2_E2") (pintype "input"))
      (node (ref "D08") (pin "F2") (pinfunction "F2_F2") (pintype "input"))
      (node (ref "D09") (pin "J2") (pinfunction "OUT_J2") (pintype "output"))
    )
    (net (code "282") (name "Net-(D09E-OUT)") (class "Default")
      (node (ref "D08") (pin "J1") (pinfunction "J1_J1") (pintype "input"))
      (node (ref "D08") (pin "K1") (pinfunction "K1_K1") (pintype "input"))
      (node (ref "D09") (pin "L1") (pinfunction "OUT_L1") (pintype "output"))
    )
    (net (code "283") (name "Net-(D09F-OUT)") (class "Default")
      (node (ref "D08") (pin "M2") (pinfunction "M2_M2") (pintype "input"))
      (node (ref "D08") (pin "N2") (pinfunction "N2_N2") (pintype "input"))
      (node (ref "D09") (pin "P2") (pinfunction "OUT_P2") (pintype "output"))
    )
    (net (code "284") (name "Net-(D09G-OUT)") (class "Default")
      (node (ref "D08") (pin "P1") (pinfunction "P1_P1") (pintype "input"))
      (node (ref "D08") (pin "R1") (pinfunction "R1_R1") (pintype "input"))
      (node (ref "D09") (pin "S1") (pinfunction "OUT_S1") (pintype "output"))
    )
    (net (code "285") (name "Net-(D09J-OUT)") (class "Default")
      (node (ref "D08") (pin "T2") (pinfunction "T2_T2") (pintype "input"))
      (node (ref "D08") (pin "U2") (pinfunction "U2_U2") (pintype "input"))
      (node (ref "D09") (pin "V2") (pinfunction "OUT_V2") (pintype "output"))
    )
    (net (code "286") (name "Net-(D10D-OUT)") (class "Default")
      (node (ref "D10") (pin "P2") (pinfunction "OUT_P2") (pintype "output"))
      (node (ref "D14") (pin "J2") (pinfunction "N1_J2") (pintype "input"))
    )
    (net (code "287") (name "Net-(D12A-IN1)") (class "Default")
      (node (ref "D12") (pin "A1") (pinfunction "IN1_A1") (pintype "input"))
      (node (ref "D12") (pin "B1") (pinfunction "IN2_B1") (pintype "input"))
      (node (ref "D12") (pin "C1") (pinfunction "IN3_C1") (pintype "input"))
      (node (ref "D12") (pin "D1") (pinfunction "IN4_D1") (pintype "input"))
      (node (ref "D13") (pin "F2") (pinfunction "F2_F2") (pintype "output"))
    )
    (net (code "288") (name "Net-(D13C-D2)") (class "Default")
      (node (ref "D13") (pin "R2") (pinfunction "E2_R2") (pintype "passive"))
      (node (ref "D13") (pin "S2") (pinfunction "D2_S2") (pintype "passive"))
    )
    (net (code "289") (name "Net-(D14-PadM2)") (class "Default")
      (node (ref "D14") (pin "M2") (pinfunction "M2_M2") (pintype "passive"))
      (node (ref "D14") (pin "V2") (pinfunction "V2_V2") (pintype "passive"))
    )
    (net (code "290") (name "Net-(D14-PadP1)") (class "Default")
      (node (ref "D14") (pin "P1") (pinfunction "P1_P1") (pintype "passive"))
      (node (ref "D14") (pin "V1") (pinfunction "V1_V1") (pintype "passive"))
    )
    (net (code "291") (name "Net-(D14E-M2)") (class "Default")
      (node (ref "D14") (pin "D2") (pinfunction "M2_D2") (pintype "passive"))
      (node (ref "D14") (pin "H1") (pinfunction "P2_H1") (pintype "passive"))
    )
    (net (code "292") (name "Net-(D14E-P1)") (class "Default")
      (node (ref "D14") (pin "A1") (pinfunction "V1_A1") (pintype "passive"))
      (node (ref "D14") (pin "C1") (pinfunction "P1_C1") (pintype "passive"))
    )
    (net (code "293") (name "Net-(D15-PadN2)") (class "Default")
      (node (ref "D15") (pin "N2") (pinfunction "N2_N2") (pintype "passive"))
      (node (ref "D15") (pin "S2") (pinfunction "S2_S2") (pintype "passive"))
    )
    (net (code "294") (name "Net-(D16D-D2)") (class "Default")
      (node (ref "D16") (pin "R2") (pinfunction "E2_R2") (pintype "passive"))
      (node (ref "D16") (pin "V2") (pinfunction "D2_V2") (pintype "passive"))
    )
    (net (code "295") (name "Net-(D16D-H1)") (class "Default")
      (node (ref "D16") (pin "S1") (pinfunction "H1_S1") (pintype "passive"))
      (node (ref "D16") (pin "S2") (pinfunction "L2_S2") (pintype "passive"))
    )
    (net (code "296") (name "Net-(D17-PadD2)") (class "Default")
      (node (ref "D17") (pin "D2") (pinfunction "D2_D2") (pintype "passive"))
      (node (ref "D17") (pin "E2") (pinfunction "E2_E2") (pintype "passive"))
    )
    (net (code "297") (name "Net-(D17C-D2)") (class "Default")
      (node (ref "D17") (pin "R2") (pinfunction "E2_R2") (pintype "passive"))
      (node (ref "D17") (pin "S2") (pinfunction "D2_S2") (pintype "passive"))
    )
    (net (code "298") (name "PAR") (class "Default")
      (node (ref "A08") (pin "U1") (pinfunction "0_U1") (pintype "output"))
      (node (ref "A25") (pin "T1") (pinfunction "P$2_T1") (pintype "bidirectional"))
    )
    (net (code "299") (name "PC+ES") (class "Default")
      (node (ref "A11") (pin "H2") (pinfunction "IN_H2") (pintype "input"))
      (node (ref "A12") (pin "C1") (pinfunction "OUT_C1") (pintype "output"))
    )
    (net (code "300") (name "PWR_CLR") (class "Default")
      (node (ref "C06") (pin "R2") (pinfunction "OUT_R2") (pintype "output"))
    )
    (net (code "301") (name "RD+WD") (class "Default")
      (node (ref "A09") (pin "P1") (pinfunction "IN3_P1") (pintype "input"))
      (node (ref "B08") (pin "N2") (pinfunction "OUT_N2") (pintype "output"))
      (node (ref "B12") (pin "D2") (pinfunction "IN1_D2") (pintype "input"))
      (node (ref "C12") (pin "R1") (pinfunction "IN2_R1") (pintype "input"))
    )
    (net (code "302") (name "RDD_00") (class "Default")
      (node (ref "A21") (pin "U2") (pinfunction "U2_U2") (pintype "output"))
      (node (ref "B09") (pin "M2") (pinfunction "D_M2") (pintype "input"))
      (node (ref "D09") (pin "C1") (pinfunction "IN2A_C1") (pintype "input"))
      (node (ref "D09") (pin "F2") (pinfunction "IN2A_F2") (pintype "input"))
    )
    (net (code "303") (name "RDD_01") (class "Default")
      (node (ref "B09") (pin "P1") (pinfunction "D_P1") (pintype "input"))
      (node (ref "B20") (pin "U2") (pinfunction "U2_U2") (pintype "output"))
      (node (ref "D09") (pin "J1") (pinfunction "IN2A_J1") (pintype "input"))
      (node (ref "D09") (pin "M2") (pinfunction "IN2A_M2") (pintype "input"))
    )
    (net (code "304") (name "RDD_02") (class "Default")
      (node (ref "A20") (pin "U2") (pinfunction "U2_U2") (pintype "output"))
      (node (ref "B09") (pin "E2") (pinfunction "D_E2") (pintype "input"))
      (node (ref "D09") (pin "P1") (pinfunction "IN2A_P1") (pintype "input"))
      (node (ref "D09") (pin "T2") (pinfunction "IN2A_T2") (pintype "input"))
    )
    (net (code "305") (name "RDMK") (class "Default")
      (node (ref "B18") (pin "U2") (pinfunction "U2_U2") (pintype "output"))
      (node (ref "CD18") (pin "AS2") (pinfunction "AS2_AS2") (pintype "input"))
    )
    (net (code "306") (name "RD_EN") (class "Default")
      (node (ref "C11") (pin "J1") (pinfunction "IN2_J1") (pintype "input"))
      (node (ref "C11") (pin "N2") (pinfunction "OUT_N2") (pintype "output"))
    )
    (net (code "307") (name "RD_EN_LPB_00-02") (class "Default")
      (node (ref "C10") (pin "D2") (pinfunction "IN1A_D2") (pintype "input"))
      (node (ref "C13") (pin "T2") (pinfunction "OUT_T2") (pintype "output"))
      (node (ref "D09") (pin "D1") (pinfunction "IN2B_D1") (pintype "input"))
      (node (ref "D09") (pin "K1") (pinfunction "IN2B_K1") (pintype "input"))
      (node (ref "D09") (pin "R1") (pinfunction "IN2B_R1") (pintype "input"))
    )
    (net (code "308") (name "RD_EN_LPB_03-05") (class "Default")
      (node (ref "C10") (pin "R2") (pinfunction "IN1A_R2") (pintype "input"))
      (node (ref "C13") (pin "R2") (pinfunction "OUT_R2") (pintype "output"))
      (node (ref "D09") (pin "H2") (pinfunction "IN2B_H2") (pintype "input"))
      (node (ref "D09") (pin "N2") (pinfunction "IN2B_N2") (pintype "input"))
      (node (ref "D09") (pin "U2") (pinfunction "IN2B_U2") (pintype "input"))
    )
    (net (code "309") (name "READ_ALL") (class "Default")
      (node (ref "D07") (pin "N2") (pinfunction "O3_N2") (pintype "output"))
    )
    (net (code "310") (name "READ_DATA") (class "Default")
      (node (ref "A10") (pin "L1") (pinfunction "IN1_L1") (pintype "input"))
      (node (ref "C11") (pin "H1") (pinfunction "IN1_H1") (pintype "input"))
      (node (ref "D07") (pin "J2") (pinfunction "O2_J2") (pintype "output"))
    )
    (net (code "311") (name "RSTA") (class "Default")
      (node (ref "C04") (pin "A1") (pinfunction "A1_A1") (pintype "output"))
    )
    (net (code "312") (name "RSTB") (class "Default")
      (node (ref "C05") (pin "C1") (pinfunction "C1_C1") (pintype "output"))
    )
    (net (code "313") (name "SE") (class "Default")
      (node (ref "D07") (pin "L2") (pinfunction "O7_L2") (pintype "output"))
    )
    (net (code "314") (name "SEARCH") (class "Default")
      (node (ref "C11") (pin "D2") (pinfunction "IN1_D2") (pintype "input"))
      (node (ref "D07") (pin "E2") (pinfunction "O1_E2") (pintype "output"))
    )
    (net (code "315") (name "SEL") (class "Default")
      (node (ref "A08") (pin "H2") (pinfunction "1_H2") (pintype "output"))
      (node (ref "A25") (pin "S1") (pinfunction "P$2_S1") (pintype "bidirectional"))
    )
    (net (code "316") (name "SHIFT_CK") (class "Default")
      (node (ref "C17") (pin "K1") (pinfunction "OUT_K1") (pintype "output"))
      (node (ref "CD18") (pin "BR2") (pinfunction "BR2_BR2") (pintype "input"))
    )
    (net (code "317") (name "SH_DTB") (class "Default")
      (node (ref "A10") (pin "R2") (pinfunction "IN2_R2") (pintype "input"))
      (node (ref "B09") (pin "B1") (pinfunction "C_B1") (pintype "input"))
      (node (ref "B09") (pin "D2") (pinfunction "C_D2") (pintype "input"))
      (node (ref "B09") (pin "H1") (pinfunction "C_H1") (pintype "input"))
      (node (ref "B09") (pin "L2") (pinfunction "C_L2") (pintype "input"))
      (node (ref "B09") (pin "N1") (pinfunction "C_N1") (pintype "input"))
      (node (ref "B09") (pin "S2") (pinfunction "C_S2") (pintype "input"))
      (node (ref "B10") (pin "E1") (pinfunction "OUT_E1") (pintype "output"))
      (node (ref "C09") (pin "B1") (pinfunction "C_B1") (pintype "input"))
      (node (ref "C09") (pin "D2") (pinfunction "C_D2") (pintype "input"))
      (node (ref "C09") (pin "H1") (pinfunction "C_H1") (pintype "input"))
      (node (ref "C09") (pin "L2") (pinfunction "C_L2") (pintype "input"))
      (node (ref "C09") (pin "N1") (pinfunction "C_N1") (pintype "input"))
      (node (ref "C09") (pin "S2") (pinfunction "C_S2") (pintype "input"))
    )
    (net (code "318") (name "SH_EN") (class "Default")
      (node (ref "A11") (pin "N2") (pinfunction "OUT_N2") (pintype "output"))
      (node (ref "A12") (pin "E2") (pinfunction "IN2_E2") (pintype "input"))
      (node (ref "C10") (pin "A1") (pinfunction "IN1A_A1") (pintype "input"))
      (node (ref "C10") (pin "F1") (pinfunction "IN1A_F1") (pintype "input"))
      (node (ref "C10") (pin "M1") (pinfunction "IN1A_M1") (pintype "input"))
    )
    (net (code "319") (name "SH_ST") (class "Default")
      (node (ref "C17") (pin "A1") (pinfunction "IN_A1") (pintype "input"))
      (node (ref "CD18") (pin "AM1") (pinfunction "AM1_AM1") (pintype "output"))
    )
    (net (code "320") (name "SH_ST-B") (class "Default")
      (node (ref "C16") (pin "P2") (pinfunction "OUT_P2") (pintype "output"))
      (node (ref "CD18") (pin "BC1") (pinfunction "BC1_BC1") (pintype "input"))
    )
    (net (code "321") (name "SINGLE_UNIT") (class "Default")
      (node (ref "A09") (pin "K1") (pinfunction "IN4_K1") (pintype "input"))
      (node (ref "B21") (pin "U2") (pinfunction "OUT_U2") (pintype "output"))
    )
    (net (code "322") (name "SP_DY") (class "Default")
      (node (ref "D14") (pin "H2") (pinfunction "H2_H2") (pintype "output"))
    )
    (net (code "323") (name "ST_BLK_MK") (class "Default")
      (node (ref "A26") (pin "K1") (pinfunction "P$2_K1") (pintype "bidirectional"))
      (node (ref "C13") (pin "E2") (pinfunction "IN_E2") (pintype "input"))
      (node (ref "CD18") (pin "AR2") (pinfunction "AR2_AR2") (pintype "output"))
    )
    (net (code "324") (name "ST_CK") (class "Default")
      (node (ref "A10") (pin "P1") (pinfunction "IN1_P1") (pintype "input"))
      (node (ref "A26") (pin "P1") (pinfunction "P$2_P1") (pintype "bidirectional"))
      (node (ref "C13") (pin "J1") (pinfunction "IN_J1") (pintype "input"))
      (node (ref "CD18") (pin "BR1") (pinfunction "BR1_BR1") (pintype "output"))
      (node (ref "D17") (pin "M2") (pinfunction "K2_M2") (pintype "input"))
      (node (ref "D17") (pin "N2") (pinfunction "J2_N2") (pintype "input"))
      (node (ref "D17") (pin "P2") (pinfunction "H2_P2") (pintype "input"))
    )
    (net (code "325") (name "ST_CK_0P") (class "Default")
      (node (ref "B12") (pin "H2") (pinfunction "IN4_H2") (pintype "input"))
      (node (ref "C12") (pin "S1") (pinfunction "IN3_S1") (pintype "input"))
      (node (ref "C13") (pin "B1") (pinfunction "OUT_B1") (pintype "output"))
    )
    (net (code "326") (name "ST_DATA") (class "Default")
      (node (ref "B12") (pin "A1") (pinfunction "IN1_A1") (pintype "input"))
      (node (ref "C13") (pin "H2") (pinfunction "IN_H2") (pintype "input"))
      (node (ref "C16") (pin "J2") (pinfunction "OUT_J2") (pintype "output"))
    )
    (net (code "327") (name "ST_FINAL") (class "Default")
      (node (ref "A09") (pin "S2") (pinfunction "IN2_S2") (pintype "input"))
      (node (ref "A26") (pin "N1") (pinfunction "P$2_N1") (pintype "bidirectional"))
      (node (ref "C11") (pin "D1") (pinfunction "IN1_D1") (pintype "input"))
      (node (ref "C13") (pin "L1") (pinfunction "IN_L1") (pintype "input"))
      (node (ref "CD18") (pin "BL2") (pinfunction "BL2_BL2") (pintype "output"))
    )
    (net (code "328") (name "ST_IDLE") (class "Default")
      (node (ref "A26") (pin "R1") (pinfunction "P$2_R1") (pintype "bidirectional"))
      (node (ref "C13") (pin "K2") (pinfunction "IN_K2") (pintype "input"))
      (node (ref "CD18") (pin "BD2") (pinfunction "BD2_BD2") (pintype "input"))
    )
    (net (code "329") (name "ST_REV_CK") (class "Default")
      (node (ref "A26") (pin "L1") (pinfunction "P$2_L1") (pintype "bidirectional"))
      (node (ref "B11") (pin "S1") (pinfunction "IN3_S1") (pintype "input"))
      (node (ref "C11") (pin "A1") (pinfunction "IN1_A1") (pintype "input"))
      (node (ref "C13") (pin "D1") (pinfunction "IN_D1") (pintype "input"))
      (node (ref "CD18") (pin "BS1") (pinfunction "BS1_BS1") (pintype "output"))
      (node (ref "D12") (pin "F2") (pinfunction "IN3_F2") (pintype "input"))
      (node (ref "D12") (pin "H2") (pinfunction "IN4_H2") (pintype "input"))
    )
    (net (code "330") (name "SWTM") (class "Default")
      (node (ref "A26") (pin "V2") (pinfunction "P$2_V2") (pintype "bidirectional"))
      (node (ref "B06") (pin "P2") (pinfunction "IN_P2") (pintype "input"))
      (node (ref "B08") (pin "V1") (pinfunction "P$1_V1") (pintype "passive"))
      (node (ref "B11") (pin "B1") (pinfunction "IN2_B1") (pintype "input"))
      (node (ref "C10") (pin "N2") (pinfunction "IN2B_N2") (pintype "input"))
      (node (ref "C12") (pin "P2") (pinfunction "IN2_P2") (pintype "input"))
      (node (ref "C15") (pin "L1") (pinfunction "IN1_L1") (pintype "input"))
    )
    (net (code "331") (name "SYNC") (class "Default")
      (node (ref "B10") (pin "D2") (pinfunction "IN1_D2") (pintype "input"))
      (node (ref "B10") (pin "E2") (pinfunction "IN2_E2") (pintype "input"))
      (node (ref "CD18") (pin "BN2") (pinfunction "BN2_BN2") (pintype "output"))
    )
    (net (code "332") (name "SYNC_EN") (class "Default")
      (node (ref "B11") (pin "M2") (pinfunction "OUT_M2") (pintype "output"))
      (node (ref "CD18") (pin "BH1") (pinfunction "BH1_BH1") (pintype "input"))
    )
    (net (code "333") (name "T3") (class "Default")
      (node (ref "C17") (pin "S1") (pinfunction "OUT_S1") (pintype "output"))
      (node (ref "D12") (pin "N1") (pinfunction "IN2_N1") (pintype "input"))
      (node (ref "D12") (pin "P1") (pinfunction "IN3_P1") (pintype "input"))
    )
    (net (code "334") (name "TIM") (class "Default")
      (node (ref "A08") (pin "L1") (pinfunction "1_L1") (pintype "output"))
      (node (ref "A25") (pin "U1") (pinfunction "P$2_U1") (pintype "bidirectional"))
    )
    (net (code "335") (name "TM_EN") (class "Default")
      (node (ref "A18") (pin "R2") (pinfunction "R2_R2") (pintype "input"))
      (node (ref "B18") (pin "R2") (pinfunction "R2_R2") (pintype "input"))
      (node (ref "C13") (pin "N1") (pinfunction "IN_N1") (pintype "input"))
      (node (ref "C15") (pin "S1") (pinfunction "OUT_S1") (pintype "output"))
      (node (ref "C16") (pin "M1") (pinfunction "IN1_M1") (pintype "input"))
      (node (ref "C16") (pin "R2") (pinfunction "IN1_R2") (pintype "input"))
    )
    (net (code "336") (name "TP00") (class "Default")
      (node (ref "A08") (pin "B1") (pinfunction "C_B1") (pintype "input"))
      (node (ref "A15") (pin "L1") (pinfunction "OUT_L1") (pintype "output"))
      (node (ref "A16") (pin "M2") (pinfunction "K2_M2") (pintype "input"))
      (node (ref "A16") (pin "N2") (pinfunction "J2_N2") (pintype "input"))
      (node (ref "A16") (pin "P2") (pinfunction "H2_P2") (pintype "input"))
      (node (ref "B10") (pin "F2") (pinfunction "IN3_F2") (pintype "input"))
      (node (ref "B10") (pin "H2") (pinfunction "IN4_H2") (pintype "input"))
      (node (ref "B10") (pin "N1") (pinfunction "IN2_N1") (pintype "input"))
      (node (ref "B13") (pin "B1") (pinfunction "C_B1") (pintype "input"))
      (node (ref "B13") (pin "D2") (pinfunction "C_D2") (pintype "input"))
      (node (ref "B13") (pin "H1") (pinfunction "C_H1") (pintype "input"))
      (node (ref "B15") (pin "J1") (pinfunction "IN2_J1") (pintype "input"))
      (node (ref "C15") (pin "E1") (pinfunction "IN2_E1") (pintype "input"))
    )
    (net (code "337") (name "TP00_A") (class "Default")
      (node (ref "A15") (pin "S1") (pinfunction "OUT_S1") (pintype "output"))
      (node (ref "B10") (pin "H1") (pinfunction "IN2_H1") (pintype "input"))
      (node (ref "C12") (pin "E2") (pinfunction "IN2_E2") (pintype "input"))
    )
    (net (code "338") (name "TP01") (class "Default")
      (node (ref "A12") (pin "J2") (pinfunction "IN2_J2") (pintype "input"))
      (node (ref "A15") (pin "P2") (pinfunction "OUT_P2") (pintype "output"))
      (node (ref "B16") (pin "M2") (pinfunction "K2_M2") (pintype "input"))
      (node (ref "B16") (pin "N2") (pinfunction "J2_N2") (pintype "input"))
      (node (ref "B16") (pin "P2") (pinfunction "H2_P2") (pintype "input"))
      (node (ref "C11") (pin "J2") (pinfunction "IN2_J2") (pintype "input"))
      (node (ref "C15") (pin "B1") (pinfunction "IN2_B1") (pintype "input"))
      (node (ref "CD18") (pin "BF1") (pinfunction "BF1_BF1") (pintype "input"))
    )
    (net (code "339") (name "TP01_A") (class "Default")
      (node (ref "A15") (pin "V2") (pinfunction "OUT_V2") (pintype "output"))
      (node (ref "B12") (pin "T2") (pinfunction "IN3_T2") (pintype "input"))
      (node (ref "C15") (pin "M2") (pinfunction "IN2_M2") (pintype "input"))
    )
    (net (code "340") (name "T_TRK") (class "Default")
      (node (ref "A18") (pin "U2") (pinfunction "U2_U2") (pintype "output"))
      (node (ref "B15") (pin "E2") (pinfunction "IN2_E2") (pintype "input"))
      (node (ref "C15") (pin "R2") (pinfunction "IN2_R2") (pintype "input"))
      (node (ref "D14") (pin "S1") (pinfunction "S1_S1") (pintype "input"))
      (node (ref "D14") (pin "U1") (pinfunction "U1_U1") (pintype "input"))
    )
    (net (code "341") (name "U+M_DY") (class "Default")
      (node (ref "D14") (pin "K1") (pinfunction "H2_K1") (pintype "output"))
    )
    (net (code "342") (name "USR_00") (class "Default")
      (node (ref "A07") (pin "V2") (pinfunction "IN2_V2") (pintype "input"))
      (node (ref "A25") (pin "A1") (pinfunction "P$2_A1") (pintype "bidirectional"))
      (node (ref "B07") (pin "E1") (pinfunction "E1_E1") (pintype "output"))
    )
    (net (code "343") (name "USR_01") (class "Default")
      (node (ref "A07") (pin "U2") (pinfunction "IN1_U2") (pintype "input"))
      (node (ref "A25") (pin "B1") (pinfunction "P$2_B1") (pintype "bidirectional"))
      (node (ref "B07") (pin "H2") (pinfunction "H2_H2") (pintype "output"))
    )
    (net (code "344") (name "USR_02") (class "Default")
      (node (ref "A07") (pin "V1") (pinfunction "IN0_V1") (pintype "input"))
      (node (ref "A25") (pin "C1") (pinfunction "P$2_C1") (pintype "bidirectional"))
      (node (ref "B07") (pin "L1") (pinfunction "L1_L1") (pintype "output"))
    )
    (net (code "345") (name "UTS") (class "Default")
      (node (ref "A10") (pin "E1") (pinfunction "IN2_E1") (pintype "input"))
      (node (ref "A26") (pin "J1") (pinfunction "P$2_J1") (pintype "bidirectional"))
      (node (ref "B15") (pin "P1") (pinfunction "IN1_P1") (pintype "input"))
      (node (ref "C14") (pin "R2") (pinfunction "0_R2") (pintype "output"))
    )
    (net (code "346") (name "VCC") (class "Default")
      (node (ref "AB01") (pin "AA2") (pinfunction "VCC_AA2") (pintype "power_in"))
      (node (ref "AB01") (pin "AB1") (pinfunction "VCC_AB1") (pintype "power_in"))
      (node (ref "AB01") (pin "AC1") (pinfunction "VCC_AC1") (pintype "power_in"))
      (node (ref "AB01") (pin "AD1") (pinfunction "VCC_AD1") (pintype "power_in"))
      (node (ref "AB01") (pin "AE1") (pinfunction "VCC_AE1") (pintype "power_in"))
      (node (ref "AB01") (pin "AF1") (pinfunction "VCC_AF1") (pintype "power_in"))
      (node (ref "AB01") (pin "AH1") (pinfunction "VCC_AH1") (pintype "power_in"))
      (node (ref "AB01") (pin "AJ1") (pinfunction "VCC_AJ1") (pintype "power_in"))
      (node (ref "AB01") (pin "AK1") (pinfunction "VCC_AK1") (pintype "power_in"))
      (node (ref "AB01") (pin "AL1") (pinfunction "VCC_AL1") (pintype "power_in"))
      (node (ref "AB01") (pin "BA2") (pinfunction "VCC_BA2") (pintype "power_in"))
      (node (ref "AB01") (pin "BB1") (pinfunction "VCC_BB1") (pintype "power_in"))
      (node (ref "AB01") (pin "BC1") (pinfunction "VCC_BC1") (pintype "power_in"))
      (node (ref "AB01") (pin "BD1") (pinfunction "VCC_BD1") (pintype "power_in"))
      (node (ref "AB01") (pin "BE1") (pinfunction "VCC_BE1") (pintype "power_in"))
    )
    (net (code "347") (name "W+UTS") (class "Default")
      (node (ref "A15") (pin "A1") (pinfunction "IN1_A1") (pintype "input"))
      (node (ref "A15") (pin "H2") (pinfunction "IN4_H2") (pintype "input"))
      (node (ref "C12") (pin "M2") (pinfunction "OUT_M2") (pintype "output"))
    )
    (net (code "348") (name "W-INH") (class "Default")
      (node (ref "A08") (pin "V1") (pinfunction "0_V1") (pintype "output"))
    )
    (net (code "349") (name "W01") (class "Default")
      (node (ref "A26") (pin "J2") (pinfunction "P$2_J2") (pintype "bidirectional"))
      (node (ref "CD18") (pin "BJ2") (pinfunction "BJ2_BJ2") (pintype "output"))
    )
    (net (code "350") (name "W01-W05") (class "Default")
      (node (ref "CD18") (pin "AK1") (pinfunction "AK1_AK1") (pintype "output"))
    )
    (net (code "351") (name "W02") (class "Default")
      (node (ref "A26") (pin "K2") (pinfunction "P$2_K2") (pintype "bidirectional"))
      (node (ref "CD18") (pin "BV2") (pinfunction "BV2_BV2") (pintype "output"))
    )
    (net (code "352") (name "W03") (class "Default")
      (node (ref "A26") (pin "L2") (pinfunction "P$2_L2") (pintype "bidirectional"))
      (node (ref "CD18") (pin "BE2") (pinfunction "BE2_BE2") (pintype "output"))
    )
    (net (code "353") (name "W04") (class "Default")
      (node (ref "A26") (pin "M2") (pinfunction "P$2_M2") (pintype "bidirectional"))
      (node (ref "CD18") (pin "AT2") (pinfunction "AT2_AT2") (pintype "output"))
    )
    (net (code "354") (name "W05") (class "Default")
      (node (ref "A26") (pin "N2") (pinfunction "P$2_N2") (pintype "bidirectional"))
      (node (ref "CD18") (pin "BU2") (pinfunction "BU2_BU2") (pintype "output"))
    )
    (net (code "355") (name "W06") (class "Default")
      (node (ref "A26") (pin "P2") (pinfunction "P$2_P2") (pintype "bidirectional"))
      (node (ref "CD18") (pin "AM2") (pinfunction "AM2_AM2") (pintype "output"))
    )
    (net (code "356") (name "W07") (class "Default")
      (node (ref "A26") (pin "R2") (pinfunction "P$2_R2") (pintype "bidirectional"))
      (node (ref "CD18") (pin "AK2") (pinfunction "AK2_AK2") (pintype "output"))
    )
    (net (code "357") (name "W08") (class "Default")
      (node (ref "A26") (pin "S2") (pinfunction "P$2_S2") (pintype "bidirectional"))
      (node (ref "CD18") (pin "AL1") (pinfunction "AL1_AL1") (pintype "output"))
    )
    (net (code "358") (name "W09") (class "Default")
      (node (ref "A26") (pin "T2") (pinfunction "P$2_T2") (pintype "bidirectional"))
      (node (ref "CD18") (pin "BF2") (pinfunction "BF2_BF2") (pintype "output"))
    )
    (net (code "359") (name "WB00") (class "Default")
      (node (ref "A21") (pin "N2") (pinfunction "N2_N2") (pintype "input"))
      (node (ref "A25") (pin "P2") (pinfunction "P$2_P2") (pintype "bidirectional"))
      (node (ref "B18") (pin "N2") (pinfunction "N2_N2") (pintype "input"))
      (node (ref "C14") (pin "F1") (pinfunction "0_F1") (pintype "output"))
      (node (ref "D09") (pin "A1") (pinfunction "IN1A_A1") (pintype "input"))
    )
    (net (code "360") (name "WB01") (class "Default")
      (node (ref "A25") (pin "R2") (pinfunction "P$2_R2") (pintype "bidirectional"))
      (node (ref "B20") (pin "N2") (pinfunction "N2_N2") (pintype "input"))
      (node (ref "C14") (pin "J2") (pinfunction "0_J2") (pintype "output"))
      (node (ref "D09") (pin "F1") (pinfunction "IN1A_F1") (pintype "input"))
    )
    (net (code "361") (name "WB02") (class "Default")
      (node (ref "A20") (pin "N2") (pinfunction "N2_N2") (pintype "input"))
      (node (ref "A25") (pin "S2") (pinfunction "P$2_S2") (pintype "bidirectional"))
      (node (ref "C14") (pin "M1") (pinfunction "0_M1") (pintype "output"))
      (node (ref "D09") (pin "M1") (pinfunction "IN1A_M1") (pintype "input"))
    )
    (net (code "362") (name "WC") (class "Default")
      (node (ref "A26") (pin "H1") (pinfunction "P$2_H1") (pintype "bidirectional"))
      (node (ref "B10") (pin "M1") (pinfunction "IN1_M1") (pintype "input"))
      (node (ref "B11") (pin "K1") (pinfunction "IN1_K1") (pintype "input"))
      (node (ref "D11") (pin "S1") (pinfunction "1_S1") (pintype "output"))
    )
    (net (code "363") (name "WC0") (class "Default")
      (node (ref "C01") (pin "H1") (pinfunction "OUT_H1") (pintype "output"))
      (node (ref "C06") (pin "M2") (pinfunction "IN_M2") (pintype "input"))
    )
    (net (code "364") (name "WRITE_ALL") (class "Default")
      (node (ref "A08") (pin "S2") (pinfunction "C_S2") (pintype "input"))
      (node (ref "B11") (pin "M1") (pinfunction "IN3_M1") (pintype "input"))
      (node (ref "B12") (pin "F1") (pinfunction "IN1_F1") (pintype "input"))
      (node (ref "D07") (pin "M2") (pinfunction "O5_M2") (pintype "output"))
    )
    (net (code "365") (name "WRITE_DATA") (class "Default")
      (node (ref "A09") (pin "R2") (pinfunction "IN1_R2") (pintype "input"))
      (node (ref "B11") (pin "R1") (pinfunction "IN2_R1") (pintype "input"))
      (node (ref "B12") (pin "B1") (pinfunction "IN2_B1") (pintype "input"))
      (node (ref "B12") (pin "P1") (pinfunction "IN3_P1") (pintype "input"))
      (node (ref "D07") (pin "F2") (pinfunction "O4_F2") (pintype "output"))
    )
    (net (code "366") (name "WRITE_OK") (class "Default")
      (node (ref "A22") (pin "D2") (pinfunction "D2_D2") (pintype "output"))
      (node (ref "B11") (pin "C1") (pinfunction "IN3_C1") (pintype "input"))
      (node (ref "B15") (pin "R1") (pinfunction "IN2_R1") (pintype "input"))
      (node (ref "C17") (pin "H2") (pinfunction "IN_H2") (pintype "input"))
    )
    (net (code "367") (name "WRITE_OK+UTS") (class "Default")
      (node (ref "B12") (pin "D1") (pinfunction "IN4_D1") (pintype "input"))
      (node (ref "B12") (pin "K1") (pinfunction "IN4_K1") (pintype "input"))
      (node (ref "C17") (pin "M1") (pinfunction "OUT_M1") (pintype "output"))
    )
    (net (code "368") (name "WRTM") (class "Default")
      (node (ref "B11") (pin "A1") (pinfunction "IN1_A1") (pintype "input"))
      (node (ref "C10") (pin "K2") (pinfunction "IN1A_K2") (pintype "input"))
      (node (ref "C12") (pin "N2") (pinfunction "IN1_N2") (pintype "input"))
      (node (ref "D07") (pin "H2") (pinfunction "O6_H2") (pintype "output"))
    )
    (net (code "369") (name "WRTM+FR03") (class "Default")
      (node (ref "B08") (pin "K2") (pinfunction "OUT_K2") (pintype "output"))
      (node (ref "C12") (pin "M1") (pinfunction "IN3_M1") (pintype "input"))
      (node (ref "C12") (pin "V2") (pinfunction "IN3_V2") (pintype "input"))
    )
    (net (code "370") (name "WR_EN") (class "Default")
      (node (ref "A20") (pin "R2") (pinfunction "R2_R2") (pintype "input"))
      (node (ref "A21") (pin "R2") (pinfunction "R2_R2") (pintype "input"))
      (node (ref "A26") (pin "F1") (pinfunction "P$2_F1") (pintype "bidirectional"))
      (node (ref "B20") (pin "R2") (pinfunction "R2_R2") (pintype "input"))
      (node (ref "C10") (pin "H2") (pinfunction "IN2B_H2") (pintype "input"))
      (node (ref "C10") (pin "U2") (pinfunction "IN2B_U2") (pintype "input"))
      (node (ref "C12") (pin "D2") (pinfunction "IN1_D2") (pintype "input"))
      (node (ref "C14") (pin "U1") (pinfunction "0_U1") (pintype "output"))
      (node (ref "C15") (pin "A1") (pinfunction "IN1_A1") (pintype "input"))
      (node (ref "C15") (pin "M1") (pinfunction "IN2_M1") (pintype "input"))
      (node (ref "D09") (pin "B1") (pinfunction "IN1B_B1") (pintype "input"))
      (node (ref "D09") (pin "E2") (pinfunction "IN1B_E2") (pintype "input"))
      (node (ref "D09") (pin "H1") (pinfunction "IN1B_H1") (pintype "input"))
      (node (ref "D09") (pin "L2") (pinfunction "IN1B_L2") (pintype "input"))
      (node (ref "D09") (pin "N1") (pinfunction "IN1B_N1") (pintype "input"))
      (node (ref "D09") (pin "S2") (pinfunction "IN1B_S2") (pintype "input"))
    )
    (net (code "371") (name "XOR_TO_LPB") (class "Default")
      (node (ref "C10") (pin "E2") (pinfunction "IN1B_E2") (pintype "input"))
      (node (ref "C10") (pin "F2") (pinfunction "IN2A_F2") (pintype "input"))
      (node (ref "C10") (pin "S2") (pinfunction "IN1B_S2") (pintype "input"))
      (node (ref "C10") (pin "T2") (pinfunction "IN2A_T2") (pintype "input"))
      (node (ref "D12") (pin "P2") (pinfunction "OUT_P2") (pintype "output"))
    )
    (net (code "372") (name "XSAD") (class "Default")
      (node (ref "A09") (pin "R1") (pinfunction "IN4_R1") (pintype "input"))
      (node (ref "A11") (pin "L2") (pinfunction "OUT_L2") (pintype "output"))
    )
    (net (code "373") (name "XSA_DY") (class "Default")
      (node (ref "A08") (pin "D2") (pinfunction "C_D2") (pintype "input"))
      (node (ref "B14") (pin "B1") (pinfunction "C_B1") (pintype "input"))
      (node (ref "B14") (pin "L2") (pinfunction "C_L2") (pintype "input"))
      (node (ref "C17") (pin "T2") (pinfunction "OUT_T2") (pintype "output"))
    )
    (net (code "374") (name "XSTA") (class "Default")
      (node (ref "B07") (pin "B1") (pinfunction "B1_B1") (pintype "input"))
      (node (ref "B07") (pin "D2") (pinfunction "D2_D2") (pintype "input"))
      (node (ref "B07") (pin "H1") (pinfunction "H1_H1") (pintype "input"))
      (node (ref "B07") (pin "L2") (pinfunction "L2_L2") (pintype "input"))
      (node (ref "B07") (pin "N1") (pinfunction "N1_N1") (pintype "input"))
      (node (ref "B07") (pin "S2") (pinfunction "S2_S2") (pintype "input"))
      (node (ref "C04") (pin "E1") (pinfunction "E1_E1") (pintype "output"))
      (node (ref "C07") (pin "B1") (pinfunction "B1_B1") (pintype "input"))
      (node (ref "C07") (pin "D2") (pinfunction "D2_D2") (pintype "input"))
      (node (ref "C07") (pin "H1") (pinfunction "H1_H1") (pintype "input"))
      (node (ref "C07") (pin "L2") (pinfunction "L2_L2") (pintype "input"))
      (node (ref "D11") (pin "N1") (pinfunction "C_N1") (pintype "input"))
      (node (ref "D13") (pin "M2") (pinfunction "K2_M2") (pintype "input"))
      (node (ref "D13") (pin "N2") (pinfunction "J2_N2") (pintype "input"))
      (node (ref "D13") (pin "P2") (pinfunction "H2_P2") (pintype "input"))
    )
    (net (code "375") (name "unconnected-(A07A-O8-PadP2)") (class "Default")
      (node (ref "A07") (pin "P2") (pinfunction "O8_P2") (pintype "output"))
    )
    (net (code "376") (name "unconnected-(A07A-O9-PadR2)") (class "Default")
      (node (ref "A07") (pin "R2") (pinfunction "O9_R2") (pintype "output"))
    )
    (net (code "377") (name "unconnected-(A07A-~{O8}-PadP1)") (class "Default")
      (node (ref "A07") (pin "P1") (pinfunction "~{O8}_P1") (pintype "output"))
    )
    (net (code "378") (name "unconnected-(A07A-~{O9}-PadR1)") (class "Default")
      (node (ref "A07") (pin "R1") (pinfunction "~{O9}_R1") (pintype "output"))
    )
    (net (code "379") (name "unconnected-(A14-PadD1)") (class "Default")
      (node (ref "A14") (pin "D1") (pinfunction "D1_D1") (pintype "passive"))
    )
    (net (code "380") (name "unconnected-(A14-PadE1)") (class "Default")
      (node (ref "A14") (pin "E1") (pinfunction "E1_E1") (pintype "passive"))
    )
    (net (code "381") (name "unconnected-(A14-PadF1)") (class "Default")
      (node (ref "A14") (pin "F1") (pinfunction "F1_F1") (pintype "passive"))
    )
    (net (code "382") (name "unconnected-(A14-PadJ1)") (class "Default")
      (node (ref "A14") (pin "J1") (pinfunction "J1_J1") (pintype "passive"))
    )
    (net (code "383") (name "unconnected-(A14D-D1-PadN1)") (class "Default")
      (node (ref "A14") (pin "N1") (pinfunction "D1_N1") (pintype "passive"))
    )
    (net (code "384") (name "unconnected-(A14D-E1-PadP1)") (class "Default")
      (node (ref "A14") (pin "P1") (pinfunction "E1_P1") (pintype "passive"))
    )
    (net (code "385") (name "unconnected-(A14D-F1-PadR1)") (class "Default")
      (node (ref "A14") (pin "R1") (pinfunction "F1_R1") (pintype "passive"))
    )
    (net (code "386") (name "unconnected-(A14D-J1-PadU1)") (class "Default")
      (node (ref "A14") (pin "U1") (pinfunction "J1_U1") (pintype "passive"))
    )
    (net (code "387") (name "unconnected-(A18-PadH2)") (class "Default")
      (node (ref "A18") (pin "H2") (pinfunction "H2_H2") (pintype "input"))
    )
    (net (code "388") (name "unconnected-(A18-PadL2)") (class "Default")
      (node (ref "A18") (pin "L2") (pinfunction "L2_L2") (pintype "input"))
    )
    (net (code "389") (name "unconnected-(A18-PadM2)") (class "Default")
      (node (ref "A18") (pin "M2") (pinfunction "M2_M2") (pintype "input"))
    )
    (net (code "390") (name "unconnected-(A20-PadH2)") (class "Default")
      (node (ref "A20") (pin "H2") (pinfunction "H2_H2") (pintype "input"))
    )
    (net (code "391") (name "unconnected-(A20-PadL2)") (class "Default")
      (node (ref "A20") (pin "L2") (pinfunction "L2_L2") (pintype "input"))
    )
    (net (code "392") (name "unconnected-(A20-PadM2)") (class "Default")
      (node (ref "A20") (pin "M2") (pinfunction "M2_M2") (pintype "input"))
    )
    (net (code "393") (name "unconnected-(A21-PadH2)") (class "Default")
      (node (ref "A21") (pin "H2") (pinfunction "H2_H2") (pintype "input"))
    )
    (net (code "394") (name "unconnected-(A21-PadL2)") (class "Default")
      (node (ref "A21") (pin "L2") (pinfunction "L2_L2") (pintype "input"))
    )
    (net (code "395") (name "unconnected-(A21-PadM2)") (class "Default")
      (node (ref "A21") (pin "M2") (pinfunction "M2_M2") (pintype "input"))
    )
    (net (code "396") (name "unconnected-(A22-PadE2)") (class "Default")
      (node (ref "A22") (pin "E2") (pinfunction "E2_E2") (pintype "passive"))
    )
    (net (code "397") (name "unconnected-(AB01-PadBM1)") (class "Default")
      (node (ref "AB01") (pin "BM1") (pinfunction "BM1_BM1") (pintype "output"))
    )
    (net (code "398") (name "unconnected-(AB01-PadBN1)") (class "Default")
      (node (ref "AB01") (pin "BN1") (pinfunction "BN1_BN1") (pintype "input"))
    )
    (net (code "399") (name "unconnected-(AB01-PadBP1)") (class "Default")
      (node (ref "AB01") (pin "BP1") (pinfunction "BP1_BP1") (pintype "input"))
    )
    (net (code "400") (name "unconnected-(AB01-PadBR1)") (class "Default")
      (node (ref "AB01") (pin "BR1") (pinfunction "BR1_BR1") (pintype "output"))
    )
    (net (code "401") (name "unconnected-(B05H-B-PadL2)") (class "Default")
      (node (ref "B05") (pin "L2") (pinfunction "B_L2") (pintype "input"))
    )
    (net (code "402") (name "unconnected-(B05H-E-PadP2)") (class "Default")
      (node (ref "B05") (pin "P2") (pinfunction "E_P2") (pintype "open_collector"))
    )
    (net (code "403") (name "unconnected-(B18-PadH2)") (class "Default")
      (node (ref "B18") (pin "H2") (pinfunction "H2_H2") (pintype "input"))
    )
    (net (code "404") (name "unconnected-(B18-PadL2)") (class "Default")
      (node (ref "B18") (pin "L2") (pinfunction "L2_L2") (pintype "input"))
    )
    (net (code "405") (name "unconnected-(B18-PadM2)") (class "Default")
      (node (ref "B18") (pin "M2") (pinfunction "M2_M2") (pintype "input"))
    )
    (net (code "406") (name "unconnected-(B20-PadH2)") (class "Default")
      (node (ref "B20") (pin "H2") (pinfunction "H2_H2") (pintype "input"))
    )
    (net (code "407") (name "unconnected-(B20-PadL2)") (class "Default")
      (node (ref "B20") (pin "L2") (pinfunction "L2_L2") (pintype "input"))
    )
    (net (code "408") (name "unconnected-(B20-PadM2)") (class "Default")
      (node (ref "B20") (pin "M2") (pinfunction "M2_M2") (pintype "input"))
    )
    (net (code "409") (name "unconnected-(B22K-A-PadR2)") (class "Default")
      (node (ref "B22") (pin "R2") (pinfunction "A_R2") (pintype "input"))
    )
    (net (code "410") (name "unconnected-(B22K-D-PadU2)") (class "Default")
      (node (ref "B22") (pin "U2") (pinfunction "D_U2") (pintype "output"))
    )
    (net (code "411") (name "unconnected-(C02A-IN13-PadP2)") (class "Default")
      (node (ref "C02") (pin "P2") (pinfunction "IN13_P2") (pintype "input"))
    )
    (net (code "412") (name "unconnected-(C02A-IN14-PadS2)") (class "Default")
      (node (ref "C02") (pin "S2") (pinfunction "IN14_S2") (pintype "input"))
    )
    (net (code "413") (name "unconnected-(C02A-O13-PadR2)") (class "Default")
      (node (ref "C02") (pin "R2") (pinfunction "O13_R2") (pintype "output"))
    )
    (net (code "414") (name "unconnected-(C02A-O14-PadT2)") (class "Default")
      (node (ref "C02") (pin "T2") (pinfunction "O14_T2") (pintype "output"))
    )
    (net (code "415") (name "unconnected-(C03A-IN13-PadP2)") (class "Default")
      (node (ref "C03") (pin "P2") (pinfunction "IN13_P2") (pintype "input"))
    )
    (net (code "416") (name "unconnected-(C03A-IN14-PadS2)") (class "Default")
      (node (ref "C03") (pin "S2") (pinfunction "IN14_S2") (pintype "input"))
    )
    (net (code "417") (name "unconnected-(C03A-IN15-PadU2)") (class "Default")
      (node (ref "C03") (pin "U2") (pinfunction "IN15_U2") (pintype "input"))
    )
    (net (code "418") (name "unconnected-(C03A-O13-PadR2)") (class "Default")
      (node (ref "C03") (pin "R2") (pinfunction "O13_R2") (pintype "output"))
    )
    (net (code "419") (name "unconnected-(C03A-O14-PadT2)") (class "Default")
      (node (ref "C03") (pin "T2") (pinfunction "O14_T2") (pintype "output"))
    )
    (net (code "420") (name "unconnected-(C03A-O15-PadV2)") (class "Default")
      (node (ref "C03") (pin "V2") (pinfunction "O15_V2") (pintype "output"))
    )
    (net (code "421") (name "unconnected-(C07-PadN1)") (class "Default")
      (node (ref "C07") (pin "N1") (pinfunction "N1_N1") (pintype "input"))
    )
    (net (code "422") (name "unconnected-(C07-PadP1)") (class "Default")
      (node (ref "C07") (pin "P1") (pinfunction "P1_P1") (pintype "input"))
    )
    (net (code "423") (name "unconnected-(C07-PadR1)") (class "Default")
      (node (ref "C07") (pin "R1") (pinfunction "R1_R1") (pintype "input"))
    )
    (net (code "424") (name "unconnected-(C07-PadS1)") (class "Default")
      (node (ref "C07") (pin "S1") (pinfunction "S1_S1") (pintype "output"))
    )
    (net (code "425") (name "unconnected-(C07-PadS2)") (class "Default")
      (node (ref "C07") (pin "S2") (pinfunction "S2_S2") (pintype "input"))
    )
    (net (code "426") (name "unconnected-(C07-PadT2)") (class "Default")
      (node (ref "C07") (pin "T2") (pinfunction "T2_T2") (pintype "input"))
    )
    (net (code "427") (name "unconnected-(C07-PadU1)") (class "Default")
      (node (ref "C07") (pin "U1") (pinfunction "U1_U1") (pintype "output"))
    )
    (net (code "428") (name "unconnected-(C07-PadU2)") (class "Default")
      (node (ref "C07") (pin "U2") (pinfunction "U2_U2") (pintype "input"))
    )
    (net (code "429") (name "unconnected-(C07-PadV1)") (class "Default")
      (node (ref "C07") (pin "V1") (pinfunction "V1_V1") (pintype "output"))
    )
    (net (code "430") (name "unconnected-(C07-PadV2)") (class "Default")
      (node (ref "C07") (pin "V2") (pinfunction "V2_V2") (pintype "output"))
    )
    (net (code "431") (name "unconnected-(CD18-PadAN2)") (class "Default")
      (node (ref "CD18") (pin "AN2") (pinfunction "AN2_AN2") (pintype "output"))
    )
    (net (code "432") (name "unconnected-(CD18-PadAU1)") (class "Default")
      (node (ref "CD18") (pin "AU1") (pinfunction "AU1_AU1") (pintype "output"))
    )
    (net (code "433") (name "unconnected-(D07A-O8-PadP2)") (class "Default")
      (node (ref "D07") (pin "P2") (pinfunction "O8_P2") (pintype "output"))
    )
    (net (code "434") (name "unconnected-(D07A-O9-PadR2)") (class "Default")
      (node (ref "D07") (pin "R2") (pinfunction "O9_R2") (pintype "output"))
    )
    (net (code "435") (name "unconnected-(D07A-~{O8}-PadP1)") (class "Default")
      (node (ref "D07") (pin "P1") (pinfunction "~{O8}_P1") (pintype "output"))
    )
    (net (code "436") (name "unconnected-(D07A-~{O9}-PadR1)") (class "Default")
      (node (ref "D07") (pin "R1") (pinfunction "~{O9}_R1") (pintype "output"))
    )
    (net (code "437") (name "unconnected-(D13-PadD2)") (class "Default")
      (node (ref "D13") (pin "D2") (pinfunction "D2_D2") (pintype "passive"))
    )
    (net (code "438") (name "unconnected-(D13-PadE2)") (class "Default")
      (node (ref "D13") (pin "E2") (pinfunction "E2_E2") (pintype "passive"))
    )
    (net (code "439") (name "unconnected-(D14-PadN2)") (class "Default")
      (node (ref "D14") (pin "N2") (pinfunction "N2_N2") (pintype "passive"))
    )
    (net (code "440") (name "unconnected-(D14-PadP2)") (class "Default")
      (node (ref "D14") (pin "P2") (pinfunction "P2_P2") (pintype "passive"))
    )
    (net (code "441") (name "unconnected-(D14-PadR2)") (class "Default")
      (node (ref "D14") (pin "R2") (pinfunction "R2_R2") (pintype "passive"))
    )
    (net (code "442") (name "unconnected-(D14-PadS2)") (class "Default")
      (node (ref "D14") (pin "S2") (pinfunction "S2_S2") (pintype "passive"))
    )
    (net (code "443") (name "unconnected-(D14-PadU2)") (class "Default")
      (node (ref "D14") (pin "U2") (pinfunction "U2_U2") (pintype "passive"))
    )
    (net (code "444") (name "unconnected-(D14E-N2-PadJ1)") (class "Default")
      (node (ref "D14") (pin "J1") (pinfunction "N2_J1") (pintype "passive"))
    )
    (net (code "445") (name "unconnected-(D14E-R2-PadF1)") (class "Default")
      (node (ref "D14") (pin "F1") (pinfunction "R2_F1") (pintype "passive"))
    )
    (net (code "446") (name "unconnected-(D14E-S2-PadE1)") (class "Default")
      (node (ref "D14") (pin "E1") (pinfunction "S2_E1") (pintype "passive"))
    )
    (net (code "447") (name "unconnected-(D14E-U2-PadD1)") (class "Default")
      (node (ref "D14") (pin "D1") (pinfunction "U2_D1") (pintype "passive"))
    )
    (net (code "448") (name "unconnected-(D14E-V2-PadB1)") (class "Default")
      (node (ref "D14") (pin "B1") (pinfunction "V2_B1") (pintype "passive"))
    )
    (net (code "449") (name "unconnected-(D15-PadE2)") (class "Default")
      (node (ref "D15") (pin "E2") (pinfunction "E2_E2") (pintype "output"))
    )
    (net (code "450") (name "unconnected-(D15-PadM2)") (class "Default")
      (node (ref "D15") (pin "M2") (pinfunction "M2_M2") (pintype "passive"))
    )
    (net (code "451") (name "unconnected-(D15-PadP2)") (class "Default")
      (node (ref "D15") (pin "P2") (pinfunction "P2_P2") (pintype "passive"))
    )
    (net (code "452") (name "unconnected-(D15-PadR2)") (class "Default")
      (node (ref "D15") (pin "R2") (pinfunction "R2_R2") (pintype "passive"))
    )
    (net (code "453") (name "unconnected-(D15-PadT2)") (class "Default")
      (node (ref "D15") (pin "T2") (pinfunction "T2_T2") (pintype "passive"))
    )
    (net (code "454") (name "unconnected-(D16D-D1-PadN1)") (class "Default")
      (node (ref "D16") (pin "N1") (pinfunction "D1_N1") (pintype "passive"))
    )
    (net (code "455") (name "unconnected-(D16D-E1-PadP1)") (class "Default")
      (node (ref "D16") (pin "P1") (pinfunction "E1_P1") (pintype "passive"))
    )
    (net (code "456") (name "unconnected-(D16D-F1-PadR1)") (class "Default")
      (node (ref "D16") (pin "R1") (pinfunction "F1_R1") (pintype "passive"))
    )
    (net (code "457") (name "unconnected-(D16D-J1-PadU1)") (class "Default")
      (node (ref "D16") (pin "U1") (pinfunction "J1_U1") (pintype "passive"))
    )
    (net (code "458") (name "~{0_TO_AC}") (class "Default")
      (node (ref "B05") (pin "H1") (pinfunction "B_H1") (pintype "input"))
      (node (ref "B06") (pin "T2") (pinfunction "OUT_T2") (pintype "output"))
    )
    (net (code "459") (name "~{0_TO_DTB}") (class "Default")
      (node (ref "A11") (pin "L1") (pinfunction "IN_L1") (pintype "input"))
      (node (ref "B09") (pin "A1") (pinfunction "R_A1") (pintype "input"))
      (node (ref "B09") (pin "K2") (pinfunction "R_K2") (pintype "input"))
      (node (ref "B10") (pin "L1") (pinfunction "OUT_L1") (pintype "output"))
      (node (ref "C09") (pin "A1") (pinfunction "R_A1") (pintype "input"))
      (node (ref "C09") (pin "K2") (pinfunction "R_K2") (pintype "input"))
    )
    (net (code "460") (name "~{0_TO_EF}") (class "Default")
      (node (ref "A08") (pin "A1") (pinfunction "R_A1") (pintype "input"))
      (node (ref "A08") (pin "N2") (pinfunction "S_N2") (pintype "input"))
      (node (ref "A08") (pin "R1") (pinfunction "S_R1") (pintype "input"))
      (node (ref "A11") (pin "F2") (pinfunction "OUT_F2") (pintype "output"))
    )
    (net (code "461") (name "~{0_TO_LPB}") (class "Default")
      (node (ref "D08") (pin "A1") (pinfunction "A1_A1") (pintype "input"))
      (node (ref "D08") (pin "K2") (pinfunction "K2_K2") (pintype "input"))
      (node (ref "D12") (pin "J2") (pinfunction "OUT_J2") (pintype "output"))
    )
    (net (code "462") (name "~{0_TO_STATE}") (class "Default")
      (node (ref "C16") (pin "L1") (pinfunction "OUT_L1") (pintype "output"))
      (node (ref "CD18") (pin "AV2") (pinfunction "AV2_AV2") (pintype "input"))
    )
    (net (code "463") (name "~{0_TO_STA}") (class "Default")
      (node (ref "A11") (pin "P1") (pinfunction "OUT_P1") (pintype "output"))
      (node (ref "B07") (pin "A1") (pinfunction "A1_A1") (pintype "input"))
      (node (ref "B07") (pin "K2") (pinfunction "K2_K2") (pintype "input"))
      (node (ref "B11") (pin "P2") (pinfunction "IN2_P2") (pintype "input"))
      (node (ref "C07") (pin "A1") (pinfunction "A1_A1") (pintype "input"))
    )
    (net (code "464") (name "~{0_TO_W}") (class "Default")
      (node (ref "C16") (pin "E1") (pinfunction "OUT_E1") (pintype "output"))
      (node (ref "CD18") (pin "BH2") (pinfunction "BH2_BH2") (pintype "input"))
    )
    (net (code "465") (name "~{00}") (class "Default")
      (node (ref "A07") (pin "D1") (pinfunction "~{O0}_D1") (pintype "output"))
      (node (ref "B22") (pin "S2") (pinfunction "B_S2") (pintype "input"))
    )
    (net (code "466") (name "~{01}") (class "Default")
      (node (ref "A07") (pin "E1") (pinfunction "~{O1}_E1") (pintype "output"))
      (node (ref "A23") (pin "N1") (pinfunction "B_N1") (pintype "input"))
    )
    (net (code "467") (name "~{02}") (class "Default")
      (node (ref "A07") (pin "J1") (pinfunction "~{O2}_J1") (pintype "output"))
      (node (ref "A23") (pin "D2") (pinfunction "A_D2") (pintype "input"))
    )
    (net (code "468") (name "~{03}") (class "Default")
      (node (ref "A07") (pin "N1") (pinfunction "~{O3}_N1") (pintype "output"))
      (node (ref "A23") (pin "E2") (pinfunction "B_E2") (pintype "input"))
    )
    (net (code "469") (name "~{04}") (class "Default")
      (node (ref "A07") (pin "F1") (pinfunction "~{O4}_F1") (pintype "output"))
      (node (ref "A23") (pin "K2") (pinfunction "A_K2") (pintype "input"))
    )
    (net (code "470") (name "~{05}") (class "Default")
      (node (ref "A07") (pin "M1") (pinfunction "~{O5}_M1") (pintype "output"))
      (node (ref "A23") (pin "L2") (pinfunction "B_L2") (pintype "input"))
    )
    (net (code "471") (name "~{06}") (class "Default")
      (node (ref "A07") (pin "H1") (pinfunction "~{O6}_H1") (pintype "output"))
      (node (ref "A23") (pin "R2") (pinfunction "A_R2") (pintype "input"))
    )
    (net (code "472") (name "~{07}") (class "Default")
      (node (ref "A07") (pin "L1") (pinfunction "~{O7}_L1") (pintype "output"))
      (node (ref "A23") (pin "S2") (pinfunction "B_S2") (pintype "input"))
    )
    (net (code "473") (name "~{76}") (class "Default")
      (node (ref "C06") (pin "T2") (pinfunction "OUT_T2") (pintype "output"))
      (node (ref "D12") (pin "R2") (pinfunction "IN1_R2") (pintype "input"))
      (node (ref "D12") (pin "S2") (pinfunction "IN2_S2") (pintype "input"))
    )
    (net (code "474") (name "~{77}") (class "Default")
      (node (ref "C06") (pin "V2") (pinfunction "OUT_V2") (pintype "output"))
      (node (ref "D12") (pin "T2") (pinfunction "IN3_T2") (pintype "input"))
      (node (ref "D12") (pin "U2") (pinfunction "IN4_U2") (pintype "input"))
    )
    (net (code "475") (name "~{ADDR_ACC}") (class "Default")
      (node (ref "B08") (pin "T2") (pinfunction "IN1_T2") (pintype "input"))
      (node (ref "C17") (pin "P1") (pinfunction "OUT_P1") (pintype "output"))
    )
    (net (code "476") (name "~{B-BRK}") (class "Default")
      (node (ref "B02") (pin "C1") (pinfunction "C_C1") (pintype "input"))
      (node (ref "B02") (pin "F2") (pinfunction "C_F2") (pintype "input"))
      (node (ref "B02") (pin "J1") (pinfunction "C_J1") (pintype "input"))
      (node (ref "B02") (pin "M2") (pinfunction "C_M2") (pintype "input"))
      (node (ref "B02") (pin "P1") (pinfunction "C_P1") (pintype "input"))
      (node (ref "B02") (pin "T2") (pinfunction "C_T2") (pintype "input"))
      (node (ref "B10") (pin "V2") (pinfunction "OUT_V2") (pintype "output"))
    )
    (net (code "477") (name "~{BAC_00}") (class "Default")
      (node (ref "B06") (pin "A1") (pinfunction "IN_A1") (pintype "input"))
      (node (ref "C03") (pin "B1") (pinfunction "O1_B1") (pintype "output"))
      (node (ref "D10") (pin "F1") (pinfunction "IN1_F1") (pintype "input"))
    )
    (net (code "478") (name "~{BAC_01}") (class "Default")
      (node (ref "B06") (pin "D1") (pinfunction "IN_D1") (pintype "input"))
      (node (ref "C03") (pin "E1") (pinfunction "O2_E1") (pintype "output"))
      (node (ref "D10") (pin "H1") (pinfunction "IN2_H1") (pintype "input"))
    )
    (net (code "479") (name "~{BAC_02}") (class "Default")
      (node (ref "B06") (pin "F1") (pinfunction "IN_F1") (pintype "input"))
      (node (ref "C03") (pin "H1") (pinfunction "O3_H1") (pintype "output"))
      (node (ref "D10") (pin "J1") (pinfunction "IN3_J1") (pintype "input"))
    )
    (net (code "480") (name "~{BAC_03}") (class "Default")
      (node (ref "B06") (pin "J1") (pinfunction "IN_J1") (pintype "input"))
      (node (ref "C03") (pin "K1") (pinfunction "O4_K1") (pintype "output"))
      (node (ref "D10") (pin "K1") (pinfunction "IN4_K1") (pintype "input"))
    )
    (net (code "481") (name "~{BAC_04}") (class "Default")
      (node (ref "B06") (pin "L1") (pinfunction "IN_L1") (pintype "input"))
      (node (ref "C03") (pin "M1") (pinfunction "O5_M1") (pintype "output"))
      (node (ref "D10") (pin "K2") (pinfunction "IN5_K2") (pintype "input"))
    )
    (net (code "482") (name "~{BAC_05}") (class "Default")
      (node (ref "B06") (pin "N1") (pinfunction "IN_N1") (pintype "input"))
      (node (ref "C03") (pin "P1") (pinfunction "O6_P1") (pintype "output"))
    )
    (net (code "483") (name "~{BAC_06}") (class "Default")
      (node (ref "B06") (pin "R1") (pinfunction "IN_R1") (pintype "input"))
      (node (ref "C03") (pin "S1") (pinfunction "O7_S1") (pintype "output"))
    )
    (net (code "484") (name "~{BAC_07}") (class "Default")
      (node (ref "B06") (pin "V1") (pinfunction "IN_V1") (pintype "input"))
      (node (ref "C03") (pin "U1") (pinfunction "O8_U1") (pintype "output"))
    )
    (net (code "485") (name "~{BAC_08}") (class "Default")
      (node (ref "B06") (pin "C1") (pinfunction "IN_C1") (pintype "input"))
      (node (ref "C03") (pin "F2") (pinfunction "O9_F2") (pintype "output"))
    )
    (net (code "486") (name "~{BAC_09}") (class "Default")
      (node (ref "B06") (pin "E2") (pinfunction "IN_E2") (pintype "input"))
      (node (ref "C03") (pin "J2") (pinfunction "O10_J2") (pintype "output"))
    )
    (net (code "487") (name "~{BAC_10}") (class "Default")
      (node (ref "A10") (pin "D2") (pinfunction "IN1_D2") (pintype "input"))
      (node (ref "B06") (pin "H2") (pinfunction "IN_H2") (pintype "input"))
      (node (ref "C03") (pin "L2") (pinfunction "O11_L2") (pintype "output"))
    )
    (net (code "488") (name "~{BAC_11}") (class "Default")
      (node (ref "B06") (pin "K2") (pinfunction "IN_K2") (pintype "input"))
      (node (ref "C03") (pin "N2") (pinfunction "O12_N2") (pintype "output"))
      (node (ref "C11") (pin "R2") (pinfunction "IN2_R2") (pintype "input"))
    )
    (net (code "489") (name "~{BLK_IN_SYNC}") (class "Default")
      (node (ref "A10") (pin "A1") (pinfunction "IN1_A1") (pintype "input"))
      (node (ref "C13") (pin "R1") (pinfunction "IN_R1") (pintype "input"))
      (node (ref "D10") (pin "J2") (pinfunction "OUT_J2") (pintype "output"))
    )
    (net (code "490") (name "~{BMB_00}") (class "Default")
      (node (ref "C02") (pin "B1") (pinfunction "O1_B1") (pintype "output"))
      (node (ref "C06") (pin "A1") (pinfunction "IN_A1") (pintype "input"))
    )
    (net (code "491") (name "~{BMB_01}") (class "Default")
      (node (ref "C02") (pin "E1") (pinfunction "O2_E1") (pintype "output"))
      (node (ref "C06") (pin "D1") (pinfunction "IN_D1") (pintype "input"))
    )
    (net (code "492") (name "~{BMB_02}") (class "Default")
      (node (ref "C02") (pin "H1") (pinfunction "O3_H1") (pintype "output"))
      (node (ref "C06") (pin "F1") (pinfunction "IN_F1") (pintype "input"))
    )
    (net (code "493") (name "~{BMB_03}") (class "Default")
      (node (ref "C02") (pin "K1") (pinfunction "O4_K1") (pintype "output"))
      (node (ref "C06") (pin "J1") (pinfunction "IN_J1") (pintype "input"))
    )
    (net (code "494") (name "~{BMB_04}") (class "Default")
      (node (ref "C02") (pin "M1") (pinfunction "O5_M1") (pintype "output"))
      (node (ref "C06") (pin "L1") (pinfunction "IN_L1") (pintype "input"))
    )
    (net (code "495") (name "~{BMB_05}") (class "Default")
      (node (ref "C02") (pin "P1") (pinfunction "O6_P1") (pintype "output"))
      (node (ref "C06") (pin "N1") (pinfunction "IN_N1") (pintype "input"))
    )
    (net (code "496") (name "~{BMB_06}") (class "Default")
      (node (ref "C02") (pin "S1") (pinfunction "O7_S1") (pintype "output"))
      (node (ref "C06") (pin "R1") (pinfunction "IN_R1") (pintype "input"))
    )
    (net (code "497") (name "~{BMB_07}") (class "Default")
      (node (ref "C02") (pin "U1") (pinfunction "O8_U1") (pintype "output"))
      (node (ref "C06") (pin "V1") (pinfunction "IN_V1") (pintype "input"))
    )
    (net (code "498") (name "~{BMB_08}") (class "Default")
      (node (ref "C02") (pin "F2") (pinfunction "O9_F2") (pintype "output"))
      (node (ref "C06") (pin "C1") (pinfunction "IN_C1") (pintype "input"))
    )
    (net (code "499") (name "~{BMB_09}") (class "Default")
      (node (ref "C02") (pin "J2") (pinfunction "O10_J2") (pintype "output"))
      (node (ref "C06") (pin "E2") (pinfunction "IN_E2") (pintype "input"))
    )
    (net (code "500") (name "~{BMB_10}") (class "Default")
      (node (ref "C02") (pin "L2") (pinfunction "O11_L2") (pintype "output"))
      (node (ref "C06") (pin "H2") (pinfunction "IN_H2") (pintype "input"))
    )
    (net (code "501") (name "~{BMB_11}") (class "Default")
      (node (ref "C02") (pin "N2") (pinfunction "O12_N2") (pintype "output"))
      (node (ref "C06") (pin "K2") (pinfunction "IN_K2") (pintype "input"))
    )
    (net (code "502") (name "~{BMR00}") (class "Default")
      (node (ref "A23") (pin "H1") (pinfunction "B_H1") (pintype "input"))
      (node (ref "B14") (pin "R2") (pinfunction "0_R2") (pintype "output"))
    )
    (net (code "503") (name "~{BMR01}") (class "Default")
      (node (ref "A23") (pin "A1") (pinfunction "A_A1") (pintype "input"))
      (node (ref "B14") (pin "E1") (pinfunction "1_E1") (pintype "output"))
    )
    (net (code "504") (name "~{C00}") (class "Default")
      (node (ref "A12") (pin "P2") (pinfunction "IN1_P2") (pintype "input"))
      (node (ref "B13") (pin "P1") (pinfunction "D_P1") (pintype "input"))
      (node (ref "B13") (pin "S2") (pinfunction "C_S2") (pintype "input"))
      (node (ref "B13") (pin "U1") (pinfunction "0_U1") (pintype "output"))
      (node (ref "B15") (pin "H1") (pinfunction "IN1_H1") (pintype "input"))
      (node (ref "C15") (pin "J2") (pinfunction "IN2_J2") (pintype "input"))
    )
    (net (code "505") (name "~{C01}") (class "Default")
      (node (ref "A12") (pin "R2") (pinfunction "IN2_R2") (pintype "input"))
      (node (ref "B10") (pin "P1") (pinfunction "IN3_P1") (pintype "input"))
      (node (ref "B13") (pin "M2") (pinfunction "D_M2") (pintype "input"))
      (node (ref "B13") (pin "R2") (pinfunction "0_R2") (pintype "output"))
      (node (ref "C12") (pin "F2") (pinfunction "IN3_F2") (pintype "input"))
      (node (ref "D10") (pin "D1") (pinfunction "IN4_D1") (pintype "input"))
    )
    (net (code "506") (name "~{CK00}") (class "Default")
      (node (ref "A18") (pin "N2") (pinfunction "N2_N2") (pintype "input"))
      (node (ref "B14") (pin "T2") (pinfunction "D_T2") (pintype "input"))
      (node (ref "B14") (pin "U1") (pinfunction "0_U1") (pintype "output"))
    )
    (net (code "507") (name "~{CK01}") (class "Default")
      (node (ref "B14") (pin "V1") (pinfunction "0_V1") (pintype "output"))
      (node (ref "C16") (pin "S2") (pinfunction "IN2_S2") (pintype "input"))
      (node (ref "C16") (pin "T2") (pinfunction "IN3_T2") (pintype "input"))
      (node (ref "C16") (pin "U2") (pinfunction "IN4_U2") (pintype "input"))
    )
    (net (code "508") (name "~{CLR_DF}") (class "Default")
      (node (ref "A11") (pin "U1") (pinfunction "OUT_U1") (pintype "output"))
      (node (ref "D11") (pin "N2") (pinfunction "S_N2") (pintype "input"))
    )
    (net (code "509") (name "~{CLR_DTF}") (class "Default")
      (node (ref "C13") (pin "U1") (pinfunction "OUT_U1") (pintype "output"))
      (node (ref "D11") (pin "U2") (pinfunction "S_U2") (pintype "input"))
    )
    (net (code "510") (name "~{CSTA}") (class "Default")
      (node (ref "A10") (pin "L2") (pinfunction "IN1_L2") (pintype "input"))
      (node (ref "C04") (pin "D1") (pinfunction "D1_D1") (pintype "output"))
    )
    (net (code "511") (name "~{DATA}") (class "Default")
      (node (ref "B12") (pin "N1") (pinfunction "IN2_N1") (pintype "input"))
      (node (ref "C11") (pin "L2") (pinfunction "IN1_L2") (pintype "input"))
      (node (ref "C13") (pin "H1") (pinfunction "OUT_H1") (pintype "output"))
      (node (ref "C16") (pin "D2") (pinfunction "IN1_D2") (pintype "input"))
    )
    (net (code "512") (name "~{DB_00}") (class "Default")
      (node (ref "A06") (pin "B1") (pinfunction "P$2_B1") (pintype "bidirectional"))
      (node (ref "B02") (pin "D1") (pinfunction "D_D1") (pintype "open_collector"))
      (node (ref "D06") (pin "B1") (pinfunction "P$2_B1") (pintype "bidirectional"))
    )
    (net (code "513") (name "~{DB_01}") (class "Default")
      (node (ref "A06") (pin "D1") (pinfunction "P$2_D1") (pintype "bidirectional"))
      (node (ref "B02") (pin "E1") (pinfunction "E_E1") (pintype "open_collector"))
      (node (ref "D06") (pin "D1") (pinfunction "P$2_D1") (pintype "bidirectional"))
    )
    (net (code "514") (name "~{DB_02}") (class "Default")
      (node (ref "A06") (pin "E1") (pinfunction "P$2_E1") (pintype "bidirectional"))
      (node (ref "B02") (pin "K1") (pinfunction "D_K1") (pintype "open_collector"))
      (node (ref "D06") (pin "E1") (pinfunction "P$2_E1") (pintype "bidirectional"))
    )
    (net (code "515") (name "~{DB_03}") (class "Default")
      (node (ref "A06") (pin "H1") (pinfunction "P$2_H1") (pintype "bidirectional"))
      (node (ref "B02") (pin "L1") (pinfunction "E_L1") (pintype "open_collector"))
      (node (ref "D06") (pin "H1") (pinfunction "P$2_H1") (pintype "bidirectional"))
    )
    (net (code "516") (name "~{DB_04}") (class "Default")
      (node (ref "A06") (pin "J1") (pinfunction "P$2_J1") (pintype "bidirectional"))
      (node (ref "B02") (pin "R1") (pinfunction "D_R1") (pintype "open_collector"))
      (node (ref "D06") (pin "J1") (pinfunction "P$2_J1") (pintype "bidirectional"))
    )
    (net (code "517") (name "~{DB_05}") (class "Default")
      (node (ref "A06") (pin "L1") (pinfunction "P$2_L1") (pintype "bidirectional"))
      (node (ref "B02") (pin "S1") (pinfunction "E_S1") (pintype "open_collector"))
      (node (ref "D06") (pin "L1") (pinfunction "P$2_L1") (pintype "bidirectional"))
    )
    (net (code "518") (name "~{DB_06}") (class "Default")
      (node (ref "A06") (pin "M1") (pinfunction "P$2_M1") (pintype "bidirectional"))
      (node (ref "B02") (pin "H2") (pinfunction "D_H2") (pintype "open_collector"))
      (node (ref "D06") (pin "M1") (pinfunction "P$2_M1") (pintype "bidirectional"))
    )
    (net (code "519") (name "~{DB_07}") (class "Default")
      (node (ref "A06") (pin "P1") (pinfunction "P$2_P1") (pintype "bidirectional"))
      (node (ref "B02") (pin "J2") (pinfunction "E_J2") (pintype "open_collector"))
      (node (ref "D06") (pin "P1") (pinfunction "P$2_P1") (pintype "bidirectional"))
    )
    (net (code "520") (name "~{DB_08}") (class "Default")
      (node (ref "A06") (pin "S1") (pinfunction "P$2_S1") (pintype "bidirectional"))
      (node (ref "B02") (pin "N2") (pinfunction "D_N2") (pintype "open_collector"))
      (node (ref "D06") (pin "S1") (pinfunction "P$2_S1") (pintype "bidirectional"))
    )
    (net (code "521") (name "~{DB_09}") (class "Default")
      (node (ref "A06") (pin "D2") (pinfunction "P$2_D2") (pintype "bidirectional"))
      (node (ref "B02") (pin "P2") (pinfunction "E_P2") (pintype "open_collector"))
      (node (ref "D06") (pin "D2") (pinfunction "P$2_D2") (pintype "bidirectional"))
    )
    (net (code "522") (name "~{DB_10}") (class "Default")
      (node (ref "A06") (pin "E2") (pinfunction "P$2_E2") (pintype "bidirectional"))
      (node (ref "B02") (pin "U2") (pinfunction "D_U2") (pintype "open_collector"))
      (node (ref "D06") (pin "E2") (pinfunction "P$2_E2") (pintype "bidirectional"))
    )
    (net (code "523") (name "~{DB_11}") (class "Default")
      (node (ref "A06") (pin "H2") (pinfunction "P$2_H2") (pintype "bidirectional"))
      (node (ref "B02") (pin "V2") (pinfunction "E_V2") (pintype "open_collector"))
      (node (ref "D06") (pin "H2") (pinfunction "P$2_H2") (pintype "bidirectional"))
    )
    (net (code "524") (name "~{DF}") (class "Default")
      (node (ref "B05") (pin "A1") (pinfunction "A_A1") (pintype "input"))
      (node (ref "B12") (pin "J1") (pinfunction "IN3_J1") (pintype "input"))
      (node (ref "D11") (pin "P2") (pinfunction "1_P2") (pintype "output"))
    )
    (net (code "525") (name "~{DTB_00}") (class "Default")
      (node (ref "B02") (pin "A1") (pinfunction "A_A1") (pintype "input"))
      (node (ref "C09") (pin "F1") (pinfunction "0_F1") (pintype "output"))
    )
    (net (code "526") (name "~{DTB_01}") (class "Default")
      (node (ref "B02") (pin "B1") (pinfunction "B_B1") (pintype "input"))
      (node (ref "C09") (pin "J2") (pinfunction "0_J2") (pintype "output"))
    )
    (net (code "527") (name "~{DTB_02}") (class "Default")
      (node (ref "B02") (pin "F1") (pinfunction "A_F1") (pintype "input"))
      (node (ref "C09") (pin "M1") (pinfunction "0_M1") (pintype "output"))
    )
    (net (code "528") (name "~{DTB_03}") (class "Default")
      (node (ref "B02") (pin "H1") (pinfunction "B_H1") (pintype "input"))
      (node (ref "C09") (pin "R2") (pinfunction "0_R2") (pintype "output"))
    )
    (net (code "529") (name "~{DTB_04}") (class "Default")
      (node (ref "B02") (pin "M1") (pinfunction "A_M1") (pintype "input"))
      (node (ref "C09") (pin "U1") (pinfunction "0_U1") (pintype "output"))
    )
    (net (code "530") (name "~{DTB_05}") (class "Default")
      (node (ref "B02") (pin "N1") (pinfunction "B_N1") (pintype "input"))
      (node (ref "C09") (pin "V1") (pinfunction "0_V1") (pintype "output"))
    )
    (net (code "531") (name "~{DTB_06}") (class "Default")
      (node (ref "B02") (pin "D2") (pinfunction "A_D2") (pintype "input"))
      (node (ref "B09") (pin "F1") (pinfunction "0_F1") (pintype "output"))
    )
    (net (code "532") (name "~{DTB_07}") (class "Default")
      (node (ref "B02") (pin "E2") (pinfunction "B_E2") (pintype "input"))
      (node (ref "B09") (pin "V1") (pinfunction "0_V1") (pintype "output"))
    )
    (net (code "533") (name "~{DTB_08}") (class "Default")
      (node (ref "B02") (pin "K2") (pinfunction "A_K2") (pintype "input"))
      (node (ref "B09") (pin "M1") (pinfunction "0_M1") (pintype "output"))
    )
    (net (code "534") (name "~{DTB_09}") (class "Default")
      (node (ref "B02") (pin "L2") (pinfunction "B_L2") (pintype "input"))
      (node (ref "B09") (pin "R2") (pinfunction "0_R2") (pintype "output"))
    )
    (net (code "535") (name "~{DTB_10}") (class "Default")
      (node (ref "B02") (pin "R2") (pinfunction "A_R2") (pintype "input"))
      (node (ref "B09") (pin "U1") (pinfunction "0_U1") (pintype "output"))
    )
    (net (code "536") (name "~{DTB_11}") (class "Default")
      (node (ref "B02") (pin "S2") (pinfunction "B_S2") (pintype "input"))
      (node (ref "B09") (pin "J2") (pinfunction "0_J2") (pintype "output"))
    )
    (net (code "537") (name "~{DTF}") (class "Default")
      (node (ref "B04") (pin "L2") (pinfunction "B_L2") (pintype "input"))
      (node (ref "B12") (pin "C1") (pinfunction "IN3_C1") (pintype "input"))
      (node (ref "D11") (pin "V2") (pinfunction "1_V2") (pintype "output"))
    )
    (net (code "538") (name "~{DTSF}") (class "Default")
      (node (ref "C05") (pin "B1") (pinfunction "B1_B1") (pintype "output"))
    )
    (net (code "539") (name "~{EA_00}") (class "Default")
      (node (ref "A06") (pin "V2") (pinfunction "P$2_V2") (pintype "bidirectional"))
      (node (ref "B05") (pin "R1") (pinfunction "D_R1") (pintype "open_collector"))
      (node (ref "D06") (pin "V2") (pinfunction "P$2_V2") (pintype "bidirectional"))
    )
    (net (code "540") (name "~{EA_01}") (class "Default")
      (node (ref "A06") (pin "T2") (pinfunction "P$2_T2") (pintype "bidirectional"))
      (node (ref "B05") (pin "S1") (pinfunction "E_S1") (pintype "open_collector"))
      (node (ref "D06") (pin "T2") (pinfunction "P$2_T2") (pintype "bidirectional"))
    )
    (net (code "541") (name "~{EA_02}") (class "Default")
      (node (ref "A06") (pin "S2") (pinfunction "P$2_S2") (pintype "bidirectional"))
      (node (ref "B05") (pin "H2") (pinfunction "D_H2") (pintype "open_collector"))
      (node (ref "D06") (pin "S2") (pinfunction "P$2_S2") (pintype "bidirectional"))
    )
    (net (code "542") (name "~{EF}") (class "Default")
      (node (ref "A11") (pin "K1") (pinfunction "OUT_K1") (pintype "output"))
      (node (ref "B04") (pin "A1") (pinfunction "A_A1") (pintype "input"))
    )
    (net (code "543") (name "~{END}") (class "Default")
      (node (ref "A08") (pin "F1") (pinfunction "0_F1") (pintype "output"))
      (node (ref "A09") (pin "M2") (pinfunction "IN3_M2") (pintype "input"))
      (node (ref "B04") (pin "F1") (pinfunction "A_F1") (pintype "input"))
    )
    (net (code "544") (name "~{ENI}") (class "Default")
      (node (ref "B03") (pin "L2") (pinfunction "B_L2") (pintype "input"))
      (node (ref "C07") (pin "M1") (pinfunction "M1_M1") (pintype "output"))
    )
    (net (code "545") (name "~{FR_00}") (class "Default")
      (node (ref "B03") (pin "N1") (pinfunction "B_N1") (pintype "input"))
      (node (ref "B07") (pin "U1") (pinfunction "U1_U1") (pintype "output"))
      (node (ref "C12") (pin "K1") (pinfunction "IN1_K1") (pintype "input"))
      (node (ref "C12") (pin "P1") (pinfunction "IN1_P1") (pintype "input"))
    )
    (net (code "546") (name "~{FR_01}") (class "Default")
      (node (ref "A12") (pin "H2") (pinfunction "IN1_H2") (pintype "input"))
      (node (ref "B03") (pin "D2") (pinfunction "A_D2") (pintype "input"))
      (node (ref "B05") (pin "E2") (pinfunction "B_E2") (pintype "input"))
      (node (ref "B07") (pin "V1") (pinfunction "V1_V1") (pintype "output"))
    )
    (net (code "547") (name "~{FR_02}") (class "Default")
      (node (ref "B03") (pin "E2") (pinfunction "B_E2") (pintype "input"))
      (node (ref "C07") (pin "F1") (pinfunction "F1_F1") (pintype "output"))
    )
    (net (code "548") (name "~{FR_03}") (class "Default")
      (node (ref "B03") (pin "K2") (pinfunction "A_K2") (pintype "input"))
      (node (ref "B08") (pin "J2") (pinfunction "IN2_J2") (pintype "input"))
      (node (ref "C07") (pin "J2") (pinfunction "J2_J2") (pintype "output"))
    )
    (net (code "549") (name "~{IM_00}") (class "Default")
      (node (ref "A04") (pin "B1") (pinfunction "P$2_B1") (pintype "bidirectional"))
      (node (ref "B03") (pin "D1") (pinfunction "D_D1") (pintype "open_collector"))
      (node (ref "B04") (pin "D1") (pinfunction "D_D1") (pintype "open_collector"))
      (node (ref "D04") (pin "B1") (pinfunction "P$2_B1") (pintype "bidirectional"))
    )
    (net (code "550") (name "~{IM_01}") (class "Default")
      (node (ref "A04") (pin "D1") (pinfunction "P$2_D1") (pintype "bidirectional"))
      (node (ref "B03") (pin "E1") (pinfunction "E_E1") (pintype "open_collector"))
      (node (ref "B04") (pin "E1") (pinfunction "E_E1") (pintype "open_collector"))
      (node (ref "D04") (pin "D1") (pinfunction "P$2_D1") (pintype "bidirectional"))
    )
    (net (code "551") (name "~{IM_02}") (class "Default")
      (node (ref "A04") (pin "E1") (pinfunction "P$2_E1") (pintype "bidirectional"))
      (node (ref "B03") (pin "K1") (pinfunction "D_K1") (pintype "open_collector"))
      (node (ref "B04") (pin "K1") (pinfunction "D_K1") (pintype "open_collector"))
      (node (ref "D04") (pin "E1") (pinfunction "P$2_E1") (pintype "bidirectional"))
    )
    (net (code "552") (name "~{IM_03}") (class "Default")
      (node (ref "A04") (pin "H1") (pinfunction "P$2_H1") (pintype "bidirectional"))
      (node (ref "B03") (pin "L1") (pinfunction "E_L1") (pintype "open_collector"))
      (node (ref "B04") (pin "L1") (pinfunction "E_L1") (pintype "open_collector"))
      (node (ref "D04") (pin "H1") (pinfunction "P$2_H1") (pintype "bidirectional"))
    )
    (net (code "553") (name "~{IM_04}") (class "Default")
      (node (ref "A04") (pin "J1") (pinfunction "P$2_J1") (pintype "bidirectional"))
      (node (ref "B03") (pin "R1") (pinfunction "D_R1") (pintype "open_collector"))
      (node (ref "B04") (pin "R1") (pinfunction "D_R1") (pintype "open_collector"))
      (node (ref "D04") (pin "J1") (pinfunction "P$2_J1") (pintype "bidirectional"))
    )
    (net (code "554") (name "~{IM_05}") (class "Default")
      (node (ref "A04") (pin "L1") (pinfunction "P$2_L1") (pintype "bidirectional"))
      (node (ref "B03") (pin "S1") (pinfunction "E_S1") (pintype "open_collector"))
      (node (ref "B04") (pin "S1") (pinfunction "E_S1") (pintype "open_collector"))
      (node (ref "D04") (pin "L1") (pinfunction "P$2_L1") (pintype "bidirectional"))
    )
    (net (code "555") (name "~{IM_06}") (class "Default")
      (node (ref "A04") (pin "M1") (pinfunction "P$2_M1") (pintype "bidirectional"))
      (node (ref "B03") (pin "H2") (pinfunction "D_H2") (pintype "open_collector"))
      (node (ref "B04") (pin "H2") (pinfunction "D_H2") (pintype "open_collector"))
      (node (ref "D04") (pin "M1") (pinfunction "P$2_M1") (pintype "bidirectional"))
    )
    (net (code "556") (name "~{IM_07}") (class "Default")
      (node (ref "A04") (pin "P1") (pinfunction "P$2_P1") (pintype "bidirectional"))
      (node (ref "B03") (pin "J2") (pinfunction "E_J2") (pintype "open_collector"))
      (node (ref "B04") (pin "J2") (pinfunction "E_J2") (pintype "open_collector"))
      (node (ref "D04") (pin "P1") (pinfunction "P$2_P1") (pintype "bidirectional"))
    )
    (net (code "557") (name "~{IM_08}") (class "Default")
      (node (ref "A04") (pin "S1") (pinfunction "P$2_S1") (pintype "bidirectional"))
      (node (ref "B03") (pin "N2") (pinfunction "D_N2") (pintype "open_collector"))
      (node (ref "B04") (pin "N2") (pinfunction "D_N2") (pintype "open_collector"))
      (node (ref "D04") (pin "S1") (pinfunction "P$2_S1") (pintype "bidirectional"))
    )
    (net (code "558") (name "~{IM_09}") (class "Default")
      (node (ref "A04") (pin "D2") (pinfunction "P$2_D2") (pintype "bidirectional"))
      (node (ref "B03") (pin "P2") (pinfunction "E_P2") (pintype "open_collector"))
      (node (ref "D04") (pin "D2") (pinfunction "P$2_D2") (pintype "bidirectional"))
    )
    (net (code "559") (name "~{IM_10}") (class "Default")
      (node (ref "A04") (pin "E2") (pinfunction "P$2_E2") (pintype "bidirectional"))
      (node (ref "D04") (pin "E2") (pinfunction "P$2_E2") (pintype "bidirectional"))
    )
    (net (code "560") (name "~{IM_11}") (class "Default")
      (node (ref "A04") (pin "H2") (pinfunction "P$2_H2") (pintype "bidirectional"))
      (node (ref "B04") (pin "P2") (pinfunction "E_P2") (pintype "open_collector"))
      (node (ref "D04") (pin "H2") (pinfunction "P$2_H2") (pintype "bidirectional"))
    )
    (net (code "561") (name "~{INT_RQ}") (class "Default")
      (node (ref "A12") (pin "K1") (pinfunction "OUT_K1") (pintype "output"))
      (node (ref "B05") (pin "B1") (pinfunction "B_B1") (pintype "input"))
    )
    (net (code "562") (name "~{LDMF}") (class "Default")
      (node (ref "B08") (pin "P2") (pinfunction "IN1_P2") (pintype "input"))
      (node (ref "C05") (pin "F1") (pinfunction "F1_F1") (pintype "output"))
    )
    (net (code "563") (name "~{LPB_00}") (class "Default")
      (node (ref "D08") (pin "F1") (pinfunction "F1_F1") (pintype "output"))
      (node (ref "D10") (pin "M1") (pinfunction "IN1_M1") (pintype "input"))
    )
    (net (code "564") (name "~{LPB_01}") (class "Default")
      (node (ref "D08") (pin "M1") (pinfunction "M1_M1") (pintype "output"))
      (node (ref "D10") (pin "N1") (pinfunction "IN2_N1") (pintype "input"))
    )
    (net (code "565") (name "~{LPB_02}") (class "Default")
      (node (ref "D08") (pin "U1") (pinfunction "U1_U1") (pintype "output"))
      (node (ref "D10") (pin "P1") (pinfunction "IN3_P1") (pintype "input"))
    )
    (net (code "566") (name "~{LPB_03}") (class "Default")
      (node (ref "D08") (pin "J2") (pinfunction "J2_J2") (pintype "output"))
      (node (ref "D10") (pin "R1") (pinfunction "IN4_R1") (pintype "input"))
    )
    (net (code "567") (name "~{LPB_04}") (class "Default")
      (node (ref "D08") (pin "R2") (pinfunction "R2_R2") (pintype "output"))
      (node (ref "D10") (pin "R2") (pinfunction "IN5_R2") (pintype "input"))
    )
    (net (code "568") (name "~{LPB_05}") (class "Default")
      (node (ref "D08") (pin "V1") (pinfunction "V1_V1") (pintype "output"))
      (node (ref "D10") (pin "S2") (pinfunction "IN6_S2") (pintype "input"))
      (node (ref "D10") (pin "T2") (pinfunction "IN7_T2") (pintype "input"))
      (node (ref "D10") (pin "U2") (pinfunction "IN8_U2") (pintype "input"))
    )
    (net (code "569") (name "~{M-STOP}") (class "Default")
      (node (ref "A11") (pin "S1") (pinfunction "OUT_S1") (pintype "output"))
      (node (ref "B14") (pin "D1") (pinfunction "S_D1") (pintype "input"))
      (node (ref "C07") (pin "K2") (pinfunction "K2_K2") (pintype "input"))
      (node (ref "D14") (pin "L1") (pinfunction "M1_L1") (pintype "input"))
    )
    (net (code "570") (name "~{MB_TO_DTB}") (class "Default")
      (node (ref "D12") (pin "F1") (pinfunction "IN1_F1") (pintype "input"))
      (node (ref "D12") (pin "H1") (pinfunction "IN2_H1") (pintype "input"))
      (node (ref "D12") (pin "J1") (pinfunction "IN3_J1") (pintype "input"))
      (node (ref "D12") (pin "K1") (pinfunction "IN4_K1") (pintype "input"))
      (node (ref "D12") (pin "S1") (pinfunction "OUT_S1") (pintype "output"))
    )
    (net (code "571") (name "~{MC00}") (class "Default")
      (node (ref "A10") (pin "R1") (pinfunction "IN2_R1") (pintype "input"))
      (node (ref "B11") (pin "T2") (pinfunction "IN1_T2") (pintype "input"))
      (node (ref "B13") (pin "F1") (pinfunction "0_F1") (pintype "output"))
    )
    (net (code "572") (name "~{MC01}") (class "Default")
      (node (ref "B11") (pin "P1") (pinfunction "IN1_P1") (pintype "input"))
      (node (ref "B13") (pin "J2") (pinfunction "0_J2") (pintype "output"))
      (node (ref "C11") (pin "B1") (pinfunction "IN2_B1") (pintype "input"))
      (node (ref "D10") (pin "E2") (pinfunction "IN6_E2") (pintype "input"))
    )
    (net (code "573") (name "~{MC02}") (class "Default")
      (node (ref "B13") (pin "C1") (pinfunction "D_C1") (pintype "input"))
      (node (ref "B13") (pin "M1") (pinfunction "0_M1") (pintype "output"))
      (node (ref "D10") (pin "F2") (pinfunction "IN7_F2") (pintype "input"))
    )
    (net (code "574") (name "~{MF00}") (class "Default")
      (node (ref "B04") (pin "D2") (pinfunction "A_D2") (pintype "input"))
      (node (ref "B05") (pin "M1") (pinfunction "A_M1") (pintype "input"))
      (node (ref "D11") (pin "F1") (pinfunction "0_F1") (pintype "output"))
    )
    (net (code "575") (name "~{MF01}") (class "Default")
      (node (ref "B04") (pin "E2") (pinfunction "B_E2") (pintype "input"))
      (node (ref "B05") (pin "N1") (pinfunction "B_N1") (pintype "input"))
      (node (ref "D11") (pin "J2") (pinfunction "0_J2") (pintype "output"))
    )
    (net (code "576") (name "~{MF02}") (class "Default")
      (node (ref "B04") (pin "K2") (pinfunction "A_K2") (pintype "input"))
      (node (ref "B05") (pin "D2") (pinfunction "A_D2") (pintype "input"))
      (node (ref "D11") (pin "M1") (pinfunction "0_M1") (pintype "output"))
    )
    (net (code "577") (name "~{MKTK}") (class "Default")
      (node (ref "A08") (pin "P2") (pinfunction "1_P2") (pintype "output"))
      (node (ref "A09") (pin "K2") (pinfunction "IN1_K2") (pintype "input"))
      (node (ref "B04") (pin "B1") (pinfunction "B_B1") (pintype "input"))
    )
    (net (code "578") (name "~{MKT}") (class "Default")
      (node (ref "B10") (pin "R1") (pinfunction "IN4_R1") (pintype "input"))
      (node (ref "B13") (pin "T2") (pinfunction "D_T2") (pintype "input"))
      (node (ref "B13") (pin "V1") (pinfunction "0_V1") (pintype "output"))
      (node (ref "C14") (pin "N1") (pinfunction "C_N1") (pintype "input"))
      (node (ref "D10") (pin "H2") (pinfunction "IN8_H2") (pintype "input"))
    )
    (net (code "579") (name "~{MK_BLK_END}") (class "Default")
      (node (ref "A09") (pin "C1") (pinfunction "IN3_C1") (pintype "input"))
      (node (ref "CD18") (pin "BV1") (pinfunction "BV1_BV1") (pintype "output"))
    )
    (net (code "580") (name "~{MK_BLK_MK}") (class "Default")
      (node (ref "CD18") (pin "AD2") (pinfunction "AD2_AD2") (pintype "output"))
    )
    (net (code "581") (name "~{MK_BLK_START}") (class "Default")
      (node (ref "A09") (pin "A1") (pinfunction "IN1_A1") (pintype "input"))
      (node (ref "CD18") (pin "AF1") (pinfunction "AF1_AF1") (pintype "output"))
    )
    (net (code "582") (name "~{MK_BLK_SYNC}") (class "Default")
      (node (ref "CD18") (pin "BT2") (pinfunction "BT2_BT2") (pintype "output"))
    )
    (net (code "583") (name "~{MK_DATA_SYNC}") (class "Default")
      (node (ref "CD18") (pin "AJ1") (pinfunction "AJ1_AJ1") (pintype "output"))
    )
    (net (code "584") (name "~{MK_DATA}") (class "Default")
      (node (ref "A09") (pin "B1") (pinfunction "IN2_B1") (pintype "input"))
      (node (ref "CD18") (pin "AU2") (pinfunction "AU2_AU2") (pintype "output"))
    )
    (net (code "585") (name "~{MK_END}") (class "Default")
      (node (ref "A09") (pin "D1") (pinfunction "IN4_D1") (pintype "input"))
      (node (ref "CD18") (pin "AH2") (pinfunction "AH2_AH2") (pintype "output"))
    )
    (net (code "586") (name "~{MOVE}") (class "Default")
      (node (ref "A09") (pin "F2") (pinfunction "IN3_F2") (pintype "input"))
      (node (ref "D07") (pin "D1") (pinfunction "~{O0}_D1") (pintype "output"))
    )
    (net (code "587") (name "~{MR00}") (class "Default")
      (node (ref "B03") (pin "H1") (pinfunction "B_H1") (pintype "input"))
      (node (ref "B07") (pin "R2") (pinfunction "R2_R2") (pintype "output"))
    )
    (net (code "588") (name "~{MR01}") (class "Default")
      (node (ref "B03") (pin "M1") (pinfunction "A_M1") (pintype "input"))
      (node (ref "B14") (pin "C1") (pinfunction "D_C1") (pintype "input"))
      (node (ref "C07") (pin "R2") (pinfunction "R2_R2") (pintype "output"))
    )
    (net (code "589") (name "~{PAR}") (class "Default")
      (node (ref "A08") (pin "S1") (pinfunction "1_S1") (pintype "output"))
      (node (ref "A12") (pin "E1") (pinfunction "IN2_E1") (pintype "input"))
      (node (ref "B04") (pin "M1") (pinfunction "A_M1") (pintype "input"))
    )
    (net (code "590") (name "~{PC+ES}") (class "Default")
      (node (ref "A11") (pin "J2") (pinfunction "OUT_J2") (pintype "output"))
      (node (ref "B11") (pin "R2") (pinfunction "IN3_R2") (pintype "input"))
    )
    (net (code "591") (name "~{PWR_CLR}") (class "Default")
      (node (ref "A10") (pin "H2") (pinfunction "IN1_H2") (pintype "input"))
      (node (ref "A10") (pin "M2") (pinfunction "IN2_M2") (pintype "input"))
      (node (ref "A12") (pin "A1") (pinfunction "IN1_A1") (pintype "input"))
      (node (ref "A23") (pin "M1") (pinfunction "A_M1") (pintype "input"))
      (node (ref "B08") (pin "U2") (pinfunction "IN2_U2") (pintype "input"))
      (node (ref "C05") (pin "K1") (pinfunction "OUT_K1") (pintype "output"))
      (node (ref "C06") (pin "P2") (pinfunction "IN_P2") (pintype "input"))
      (node (ref "C11") (pin "U2") (pinfunction "IN2_U2") (pintype "input"))
      (node (ref "C14") (pin "R1") (pinfunction "S_R1") (pintype "input"))
      (node (ref "D11") (pin "A1") (pinfunction "R_A1") (pintype "input"))
    )
    (net (code "592") (name "~{RDD_00}") (class "Default")
      (node (ref "A21") (pin "V2") (pinfunction "V2_V2") (pintype "output"))
    )
    (net (code "593") (name "~{RDD_01}") (class "Default")
      (node (ref "B20") (pin "V2") (pinfunction "V2_V2") (pintype "output"))
    )
    (net (code "594") (name "~{RDD_02}") (class "Default")
      (node (ref "A20") (pin "V2") (pinfunction "V2_V2") (pintype "output"))
    )
    (net (code "595") (name "~{RDMK}") (class "Default")
      (node (ref "B18") (pin "V2") (pinfunction "V2_V2") (pintype "output"))
    )
    (net (code "596") (name "~{READ_ALL}") (class "Default")
      (node (ref "C11") (pin "M1") (pinfunction "IN2_M1") (pintype "input"))
      (node (ref "D07") (pin "N1") (pinfunction "~{O3}_N1") (pintype "output"))
    )
    (net (code "597") (name "~{READ_DATA}") (class "Default")
      (node (ref "B08") (pin "L2") (pinfunction "IN1_L2") (pintype "input"))
      (node (ref "B11") (pin "J2") (pinfunction "IN1_J2") (pintype "input"))
      (node (ref "D07") (pin "J1") (pinfunction "~{O2}_J1") (pintype "output"))
    )
    (net (code "598") (name "~{RSTA}") (class "Default")
      (node (ref "B03") (pin "C1") (pinfunction "C_C1") (pintype "input"))
      (node (ref "B03") (pin "F2") (pinfunction "C_F2") (pintype "input"))
      (node (ref "B03") (pin "J1") (pinfunction "C_J1") (pintype "input"))
      (node (ref "B03") (pin "M2") (pinfunction "C_M2") (pintype "input"))
      (node (ref "B03") (pin "P1") (pinfunction "C_P1") (pintype "input"))
      (node (ref "C04") (pin "B1") (pinfunction "B1_B1") (pintype "output"))
    )
    (net (code "599") (name "~{RSTB}") (class "Default")
      (node (ref "B04") (pin "C1") (pinfunction "C_C1") (pintype "input"))
      (node (ref "B04") (pin "F2") (pinfunction "C_F2") (pintype "input"))
      (node (ref "B04") (pin "J1") (pinfunction "C_J1") (pintype "input"))
      (node (ref "B04") (pin "M2") (pinfunction "C_M2") (pintype "input"))
      (node (ref "B04") (pin "P1") (pinfunction "C_P1") (pintype "input"))
      (node (ref "C05") (pin "D1") (pinfunction "D1_D1") (pintype "output"))
    )
    (net (code "600") (name "~{SEARCH}") (class "Default")
      (node (ref "B05") (pin "K2") (pinfunction "A_K2") (pintype "input"))
      (node (ref "B11") (pin "K2") (pinfunction "IN2_K2") (pintype "input"))
      (node (ref "D07") (pin "E1") (pinfunction "~{O1}_E1") (pintype "output"))
    )
    (net (code "601") (name "~{SEL}") (class "Default")
      (node (ref "A08") (pin "J2") (pinfunction "0_J2") (pintype "output"))
      (node (ref "A09") (pin "N2") (pinfunction "IN4_N2") (pintype "input"))
      (node (ref "B04") (pin "H1") (pinfunction "B_H1") (pintype "input"))
    )
    (net (code "602") (name "~{SE}") (class "Default")
      (node (ref "A09") (pin "H1") (pinfunction "IN2_H1") (pintype "input"))
      (node (ref "D07") (pin "L1") (pinfunction "~{O7}_L1") (pintype "output"))
    )
    (net (code "603") (name "~{SH_EN}") (class "Default")
      (node (ref "A11") (pin "M2") (pinfunction "IN_M2") (pintype "input"))
      (node (ref "A12") (pin "V2") (pinfunction "OUT_V2") (pintype "output"))
      (node (ref "C10") (pin "C1") (pinfunction "IN2A_C1") (pintype "input"))
      (node (ref "C10") (pin "J1") (pinfunction "IN2A_J1") (pintype "input"))
      (node (ref "C10") (pin "P1") (pinfunction "IN2A_P1") (pintype "input"))
    )
    (net (code "604") (name "~{SKP_RQ}") (class "Default")
      (node (ref "A12") (pin "S1") (pinfunction "OUT_S1") (pintype "output"))
      (node (ref "B05") (pin "F1") (pinfunction "A_F1") (pintype "input"))
    )
    (net (code "605") (name "~{SP_DY}") (class "Default")
      (node (ref "C14") (pin "M2") (pinfunction "D_M2") (pintype "input"))
      (node (ref "D14") (pin "F2") (pinfunction "F2_F2") (pintype "output"))
    )
    (net (code "606") (name "~{ST_BLK_MK}") (class "Default")
      (node (ref "A09") (pin "D2") (pinfunction "IN1_D2") (pintype "input"))
      (node (ref "A09") (pin "M1") (pinfunction "IN1_M1") (pintype "input"))
      (node (ref "C13") (pin "F2") (pinfunction "OUT_F2") (pintype "output"))
    )
    (net (code "607") (name "~{ST_CK_0P}") (class "Default")
      (node (ref "C13") (pin "A1") (pinfunction "IN_A1") (pintype "input"))
      (node (ref "D17") (pin "L2") (pinfunction "F2_L2") (pintype "output"))
    )
    (net (code "608") (name "~{ST_CK}") (class "Default")
      (node (ref "C13") (pin "K1") (pinfunction "OUT_K1") (pintype "output"))
      (node (ref "C16") (pin "E2") (pinfunction "IN2_E2") (pintype "input"))
    )
    (net (code "609") (name "~{ST_DATA}") (class "Default")
      (node (ref "C13") (pin "J2") (pinfunction "OUT_J2") (pintype "output"))
    )
    (net (code "610") (name "~{ST_FINAL}") (class "Default")
      (node (ref "C11") (pin "M2") (pinfunction "IN2_M2") (pintype "input"))
      (node (ref "C13") (pin "M1") (pinfunction "OUT_M1") (pintype "output"))
      (node (ref "C16") (pin "F2") (pinfunction "IN3_F2") (pintype "input"))
    )
    (net (code "611") (name "~{ST_IDLE}") (class "Default")
      (node (ref "A09") (pin "E2") (pinfunction "IN2_E2") (pintype "input"))
      (node (ref "A09") (pin "N1") (pinfunction "IN2_N1") (pintype "input"))
      (node (ref "C13") (pin "L2") (pinfunction "OUT_L2") (pintype "output"))
    )
    (net (code "612") (name "~{ST_REV_CK}") (class "Default")
      (node (ref "C13") (pin "E1") (pinfunction "OUT_E1") (pintype "output"))
    )
    (net (code "613") (name "~{SWTM}") (class "Default")
      (node (ref "B06") (pin "R2") (pinfunction "OUT_R2") (pintype "output"))
      (node (ref "C10") (pin "L2") (pinfunction "IN1B_L2") (pintype "input"))
    )
    (net (code "614") (name "~{SYNC-P}") (class "Default")
      (node (ref "B10") (pin "J2") (pinfunction "OUT_J2") (pintype "output"))
      (node (ref "B13") (pin "A1") (pinfunction "R_A1") (pintype "input"))
      (node (ref "B13") (pin "K2") (pinfunction "R_K2") (pintype "input"))
    )
    (net (code "615") (name "~{SYNC}") (class "Default")
      (node (ref "CD18") (pin "BM2") (pinfunction "BM2_BM2") (pintype "output"))
    )
    (net (code "616") (name "~{TIM}") (class "Default")
      (node (ref "A08") (pin "M1") (pinfunction "0_M1") (pintype "output"))
      (node (ref "A09") (pin "L2") (pinfunction "IN2_L2") (pintype "input"))
      (node (ref "B04") (pin "N1") (pinfunction "B_N1") (pintype "input"))
    )
    (net (code "617") (name "~{TM_EN}") (class "Default")
      (node (ref "B15") (pin "D1") (pinfunction "IN1_D1") (pintype "input"))
      (node (ref "B15") (pin "D2") (pinfunction "IN1_D2") (pintype "input"))
      (node (ref "C12") (pin "C1") (pinfunction "IN3_C1") (pintype "input"))
      (node (ref "C12") (pin "K2") (pinfunction "IN2_K2") (pintype "input"))
      (node (ref "C13") (pin "P1") (pinfunction "OUT_P1") (pintype "output"))
      (node (ref "D15") (pin "J2") (pinfunction "J2_J2") (pintype "input"))
      (node (ref "D15") (pin "K2") (pinfunction "K2_K2") (pintype "input"))
    )
    (net (code "618") (name "~{TP00_A}") (class "Default")
      (node (ref "A15") (pin "M1") (pinfunction "IN1_M1") (pintype "input"))
      (node (ref "A15") (pin "N1") (pinfunction "IN2_N1") (pintype "input"))
      (node (ref "A15") (pin "P1") (pinfunction "IN3_P1") (pintype "input"))
      (node (ref "A15") (pin "R1") (pinfunction "IN4_R1") (pintype "input"))
      (node (ref "A16") (pin "L2") (pinfunction "F2_L2") (pintype "output"))
    )
    (net (code "619") (name "~{TP0_XTLK_DY}") (class "Default")
      (node (ref "A11") (pin "R2") (pinfunction "OUT_R2") (pintype "output"))
      (node (ref "A15") (pin "F2") (pinfunction "IN3_F2") (pintype "input"))
      (node (ref "A16") (pin "J2") (pinfunction "J2_J2") (pintype "input"))
      (node (ref "A16") (pin "K2") (pinfunction "K2_K2") (pintype "input"))
    )
    (net (code "620") (name "~{TP00}") (class "Default")
      (node (ref "A15") (pin "E1") (pinfunction "OUT_E1") (pintype "output"))
      (node (ref "A15") (pin "F1") (pinfunction "IN1_F1") (pintype "input"))
      (node (ref "A15") (pin "H1") (pinfunction "IN2_H1") (pintype "input"))
      (node (ref "A15") (pin "J1") (pinfunction "IN3_J1") (pintype "input"))
      (node (ref "A15") (pin "K1") (pinfunction "IN4_K1") (pintype "input"))
      (node (ref "B13") (pin "N1") (pinfunction "C_N1") (pintype "input"))
      (node (ref "CD18") (pin "AN1") (pinfunction "AN1_AN1") (pintype "input"))
    )
    (net (code "621") (name "~{TP01_A}") (class "Default")
      (node (ref "A15") (pin "R2") (pinfunction "IN1_R2") (pintype "input"))
      (node (ref "A15") (pin "S2") (pinfunction "IN2_S2") (pintype "input"))
      (node (ref "A15") (pin "T2") (pinfunction "IN3_T2") (pintype "input"))
      (node (ref "A15") (pin "U2") (pinfunction "IN4_U2") (pintype "input"))
      (node (ref "B16") (pin "L2") (pinfunction "F2_L2") (pintype "output"))
    )
    (net (code "622") (name "~{TP1_XTLK_DY}") (class "Default")
      (node (ref "A11") (pin "V2") (pinfunction "OUT_V2") (pintype "output"))
      (node (ref "A15") (pin "B1") (pinfunction "IN2_B1") (pintype "input"))
      (node (ref "B16") (pin "H2") (pinfunction "H2_H2") (pintype "input"))
      (node (ref "B16") (pin "J2") (pinfunction "J2_J2") (pintype "input"))
    )
    (net (code "623") (name "~{TP01}") (class "Default")
      (node (ref "A15") (pin "J2") (pinfunction "OUT_J2") (pintype "output"))
      (node (ref "A15") (pin "K2") (pinfunction "IN1_K2") (pintype "input"))
      (node (ref "A15") (pin "L2") (pinfunction "IN2_L2") (pintype "input"))
      (node (ref "A15") (pin "M2") (pinfunction "IN3_M2") (pintype "input"))
      (node (ref "A15") (pin "N2") (pinfunction "IN4_N2") (pintype "input"))
      (node (ref "B13") (pin "L2") (pinfunction "C_L2") (pintype "input"))
    )
    (net (code "624") (name "~{TS03}") (class "Default")
      (node (ref "C04") (pin "K1") (pinfunction "OUT_K1") (pintype "output"))
      (node (ref "D17") (pin "H2") (pinfunction "H2_H2") (pintype "input"))
      (node (ref "D17") (pin "J2") (pinfunction "J2_J2") (pintype "input"))
      (node (ref "D17") (pin "K2") (pinfunction "K2_K2") (pintype "input"))
    )
    (net (code "625") (name "~{T_00}") (class "Default")
      (node (ref "A24") (pin "V2") (pinfunction "P$2_V2") (pintype "bidirectional"))
      (node (ref "B22") (pin "V2") (pinfunction "E_V2") (pintype "output"))
      (node (ref "B23") (pin "V2") (pinfunction "P$1_V2") (pintype "passive"))
    )
    (net (code "626") (name "~{T_01}") (class "Default")
      (node (ref "A23") (pin "S1") (pinfunction "E_S1") (pintype "output"))
      (node (ref "A24") (pin "M2") (pinfunction "P$2_M2") (pintype "bidirectional"))
      (node (ref "B23") (pin "M2") (pinfunction "P$1_M2") (pintype "passive"))
    )
    (net (code "627") (name "~{T_02}") (class "Default")
      (node (ref "A23") (pin "H2") (pinfunction "D_H2") (pintype "output"))
      (node (ref "A24") (pin "N2") (pinfunction "P$2_N2") (pintype "bidirectional"))
      (node (ref "B23") (pin "N2") (pinfunction "P$1_N2") (pintype "passive"))
    )
    (net (code "628") (name "~{T_03}") (class "Default")
      (node (ref "A23") (pin "J2") (pinfunction "E_J2") (pintype "output"))
      (node (ref "A24") (pin "P2") (pinfunction "P$2_P2") (pintype "bidirectional"))
      (node (ref "B23") (pin "P2") (pinfunction "P$1_P2") (pintype "passive"))
    )
    (net (code "629") (name "~{T_04}") (class "Default")
      (node (ref "A23") (pin "N2") (pinfunction "D_N2") (pintype "output"))
      (node (ref "A24") (pin "R2") (pinfunction "P$2_R2") (pintype "bidirectional"))
      (node (ref "B23") (pin "R2") (pinfunction "P$1_R2") (pintype "passive"))
    )
    (net (code "630") (name "~{T_05}") (class "Default")
      (node (ref "A23") (pin "P2") (pinfunction "E_P2") (pintype "output"))
      (node (ref "A24") (pin "S2") (pinfunction "P$2_S2") (pintype "bidirectional"))
      (node (ref "B23") (pin "S2") (pinfunction "P$1_S2") (pintype "passive"))
    )
    (net (code "631") (name "~{T_06}") (class "Default")
      (node (ref "A23") (pin "U2") (pinfunction "D_U2") (pintype "output"))
      (node (ref "A24") (pin "T2") (pinfunction "P$2_T2") (pintype "bidirectional"))
      (node (ref "B23") (pin "T2") (pinfunction "P$1_T2") (pintype "passive"))
    )
    (net (code "632") (name "~{T_07}") (class "Default")
      (node (ref "A23") (pin "V2") (pinfunction "E_V2") (pintype "output"))
      (node (ref "A24") (pin "U2") (pinfunction "P$2_U2") (pintype "bidirectional"))
      (node (ref "B23") (pin "U2") (pinfunction "P$1_U2") (pintype "passive"))
    )
    (net (code "633") (name "~{T_FWD}") (class "Default")
      (node (ref "A23") (pin "K1") (pinfunction "D_K1") (pintype "output"))
      (node (ref "A24") (pin "E2") (pinfunction "P$2_E2") (pintype "bidirectional"))
      (node (ref "B23") (pin "H2") (pinfunction "P$1_H2") (pintype "passive"))
    )
    (net (code "634") (name "~{T_GO}") (class "Default")
      (node (ref "A23") (pin "D1") (pinfunction "D_D1") (pintype "output"))
      (node (ref "A24") (pin "C2") (pinfunction "P$2_C2") (pintype "bidirectional"))
      (node (ref "B23") (pin "D2") (pinfunction "P$1_D2") (pintype "passive"))
    )
    (net (code "635") (name "~{T_PWR_CLR}") (class "Default")
      (node (ref "A23") (pin "R1") (pinfunction "D_R1") (pintype "output"))
      (node (ref "A24") (pin "H2") (pinfunction "P$2_H2") (pintype "bidirectional"))
      (node (ref "B23") (pin "K2") (pinfunction "P$1_K2") (pintype "passive"))
    )
    (net (code "636") (name "~{T_REV}") (class "Default")
      (node (ref "A23") (pin "L1") (pinfunction "E_L1") (pintype "output"))
      (node (ref "A24") (pin "F2") (pinfunction "P$2_F2") (pintype "bidirectional"))
      (node (ref "B23") (pin "J2") (pinfunction "P$1_J2") (pintype "passive"))
    )
    (net (code "637") (name "~{T_SINGLE_UNIT}") (class "Default")
      (node (ref "A24") (pin "K2") (pinfunction "P$2_K2") (pintype "bidirectional"))
      (node (ref "B21") (pin "T2") (pinfunction "IN_T2") (pintype "input"))
    )
    (net (code "638") (name "~{T_STOP}") (class "Default")
      (node (ref "A23") (pin "E1") (pinfunction "E_E1") (pintype "output"))
      (node (ref "A24") (pin "D2") (pinfunction "P$2_D2") (pintype "bidirectional"))
      (node (ref "B23") (pin "E2") (pinfunction "P$1_E2") (pintype "passive"))
    )
    (net (code "639") (name "~{T_TRK}") (class "Default")
      (node (ref "A18") (pin "V2") (pinfunction "V2_V2") (pintype "output"))
      (node (ref "B15") (pin "E1") (pinfunction "IN2_E1") (pintype "input"))
    )
    (net (code "640") (name "~{T_WRITE_OK}") (class "Default")
      (node (ref "A22") (pin "H2") (pinfunction "H2_H2") (pintype "input"))
      (node (ref "A24") (pin "L2") (pinfunction "P$2_L2") (pintype "bidirectional"))
      (node (ref "B23") (pin "L2") (pinfunction "P$1_L2") (pintype "passive"))
    )
    (net (code "641") (name "~{U+M_DY}") (class "Default")
      (node (ref "C12") (pin "A1") (pinfunction "IN1_A1") (pintype "input"))
      (node (ref "C12") (pin "R2") (pinfunction "IN3_R2") (pintype "input"))
      (node (ref "D14") (pin "E2") (pinfunction "F2_E2") (pintype "output"))
      (node (ref "D14") (pin "N1") (pinfunction "N1_N1") (pintype "input"))
    )
    (net (code "642") (name "~{USR_00}") (class "Default")
      (node (ref "B03") (pin "A1") (pinfunction "A_A1") (pintype "input"))
      (node (ref "B07") (pin "F1") (pinfunction "F1_F1") (pintype "output"))
    )
    (net (code "643") (name "~{USR_01}") (class "Default")
      (node (ref "B03") (pin "B1") (pinfunction "B_B1") (pintype "input"))
      (node (ref "B07") (pin "J2") (pinfunction "J2_J2") (pintype "output"))
    )
    (net (code "644") (name "~{USR_02}") (class "Default")
      (node (ref "B03") (pin "F1") (pinfunction "A_F1") (pintype "input"))
      (node (ref "B07") (pin "M1") (pinfunction "M1_M1") (pintype "output"))
    )
    (net (code "645") (name "~{UTS}") (class "Default")
      (node (ref "C12") (pin "L2") (pinfunction "IN3_L2") (pintype "input"))
      (node (ref "C14") (pin "P2") (pinfunction "1_P2") (pintype "output"))
      (node (ref "C15") (pin "P2") (pinfunction "IN1_P2") (pintype "input"))
      (node (ref "C16") (pin "A1") (pinfunction "IN1_A1") (pintype "input"))
      (node (ref "C16") (pin "B1") (pinfunction "IN2_B1") (pintype "input"))
      (node (ref "C16") (pin "C1") (pinfunction "IN3_C1") (pintype "input"))
      (node (ref "C16") (pin "D1") (pinfunction "IN4_D1") (pintype "input"))
      (node (ref "C16") (pin "F1") (pinfunction "IN1_F1") (pintype "input"))
      (node (ref "C16") (pin "H1") (pinfunction "IN2_H1") (pintype "input"))
      (node (ref "C16") (pin "J1") (pinfunction "IN3_J1") (pintype "input"))
      (node (ref "C16") (pin "K1") (pinfunction "IN4_K1") (pintype "input"))
    )
    (net (code "646") (name "~{W-INH}") (class "Default")
      (node (ref "A08") (pin "V2") (pinfunction "1_V2") (pintype "output"))
      (node (ref "B11") (pin "L1") (pinfunction "IN2_L1") (pintype "input"))
      (node (ref "B12") (pin "H1") (pinfunction "IN2_H1") (pintype "input"))
    )
    (net (code "647") (name "~{WB00}") (class "Default")
      (node (ref "A21") (pin "P2") (pinfunction "P2_P2") (pintype "input"))
      (node (ref "B18") (pin "P2") (pinfunction "P2_P2") (pintype "input"))
      (node (ref "C10") (pin "D1") (pinfunction "IN2B_D1") (pintype "input"))
      (node (ref "C14") (pin "E1") (pinfunction "1_E1") (pintype "output"))
    )
    (net (code "648") (name "~{WB01}") (class "Default")
      (node (ref "B20") (pin "P2") (pinfunction "P2_P2") (pintype "input"))
      (node (ref "C10") (pin "K1") (pinfunction "IN2B_K1") (pintype "input"))
      (node (ref "C14") (pin "H2") (pinfunction "1_H2") (pintype "output"))
    )
    (net (code "649") (name "~{WB02}") (class "Default")
      (node (ref "A20") (pin "P2") (pinfunction "P2_P2") (pintype "input"))
      (node (ref "C10") (pin "R1") (pinfunction "IN2B_R1") (pintype "input"))
      (node (ref "C14") (pin "L1") (pinfunction "1_L1") (pintype "output"))
    )
    (net (code "650") (name "~{WC0}") (class "Default")
      (node (ref "C06") (pin "N2") (pinfunction "OUT_N2") (pintype "output"))
      (node (ref "D11") (pin "R1") (pinfunction "S_R1") (pintype "input"))
    )
    (net (code "651") (name "~{WC}") (class "Default")
      (node (ref "B12") (pin "F2") (pinfunction "IN3_F2") (pintype "input"))
      (node (ref "C12") (pin "T2") (pinfunction "IN1_T2") (pintype "input"))
      (node (ref "D11") (pin "M2") (pinfunction "D_M2") (pintype "input"))
      (node (ref "D11") (pin "U1") (pinfunction "0_U1") (pintype "output"))
    )
    (net (code "652") (name "~{WRITE_ALL}") (class "Default")
      (node (ref "D07") (pin "M1") (pinfunction "~{O5}_M1") (pintype "output"))
    )
    (net (code "653") (name "~{WRITE_DATA}") (class "Default")
      (node (ref "B08") (pin "M2") (pinfunction "IN2_M2") (pintype "input"))
      (node (ref "D07") (pin "F1") (pinfunction "~{O4}_F1") (pintype "output"))
    )
    (net (code "654") (name "~{WRITE_OK}") (class "Default")
      (node (ref "A10") (pin "J1") (pinfunction "IN2_J1") (pintype "input"))
      (node (ref "C17") (pin "J2") (pinfunction "OUT_J2") (pintype "output"))
    )
    (net (code "655") (name "~{WRTM}") (class "Default")
      (node (ref "B08") (pin "H2") (pinfunction "IN1_H2") (pintype "input"))
      (node (ref "C10") (pin "M2") (pinfunction "IN2A_M2") (pintype "input"))
      (node (ref "D07") (pin "H1") (pinfunction "~{O6}_H1") (pintype "output"))
    )
    (net (code "656") (name "~{WR_EN}") (class "Default")
      (node (ref "B11") (pin "F1") (pinfunction "IN2_F1") (pintype "input"))
      (node (ref "C11") (pin "H2") (pinfunction "IN1_H2") (pintype "input"))
      (node (ref "C12") (pin "J2") (pinfunction "IN1_J2") (pintype "input"))
      (node (ref "C14") (pin "S1") (pinfunction "1_S1") (pintype "output"))
      (node (ref "C15") (pin "D2") (pinfunction "IN1_D2") (pintype "input"))
      (node (ref "C15") (pin "H2") (pinfunction "IN1_H2") (pintype "input"))
    )
    (net (code "657") (name "~{XSAD}") (class "Default")
      (node (ref "A11") (pin "K2") (pinfunction "IN_K2") (pintype "input"))
      (node (ref "D13") (pin "L2") (pinfunction "F2_L2") (pintype "output"))
    )
    (net (code "658") (name "~{XSTA}") (class "Default")
      (node (ref "B08") (pin "R2") (pinfunction "IN2_R2") (pintype "input"))
      (node (ref "C04") (pin "F1") (pinfunction "F1_F1") (pintype "output"))
      (node (ref "D13") (pin "H2") (pinfunction "H2_H2") (pintype "input"))
      (node (ref "D13") (pin "J2") (pinfunction "J2_J2") (pintype "input"))
      (node (ref "D13") (pin "K2") (pinfunction "K2_K2") (pintype "input"))
      (node (ref "D14") (pin "K2") (pinfunction "U1_K2") (pintype "input"))
      (node (ref "D14") (pin "L2") (pinfunction "S1_L2") (pintype "input"))
      (node (ref "D16") (pin "M2") (pinfunction "H2_M2") (pintype "input"))
      (node (ref "D16") (pin "N2") (pinfunction "J2_N2") (pintype "input"))
    )
  )
)
